# schematic.net
KiCad netlist of a schematic drawn in EAGLE
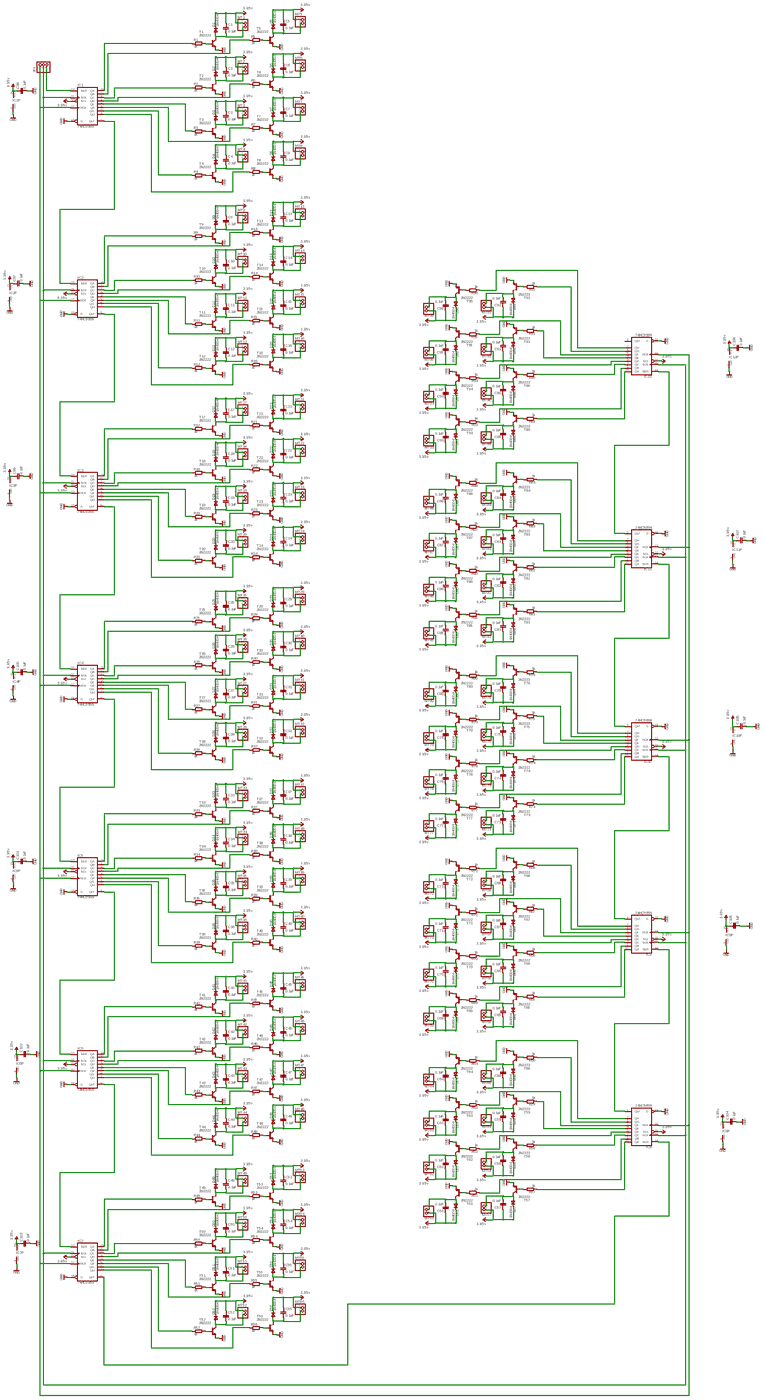
[diagram p0: schematic, sheet 1, overview]
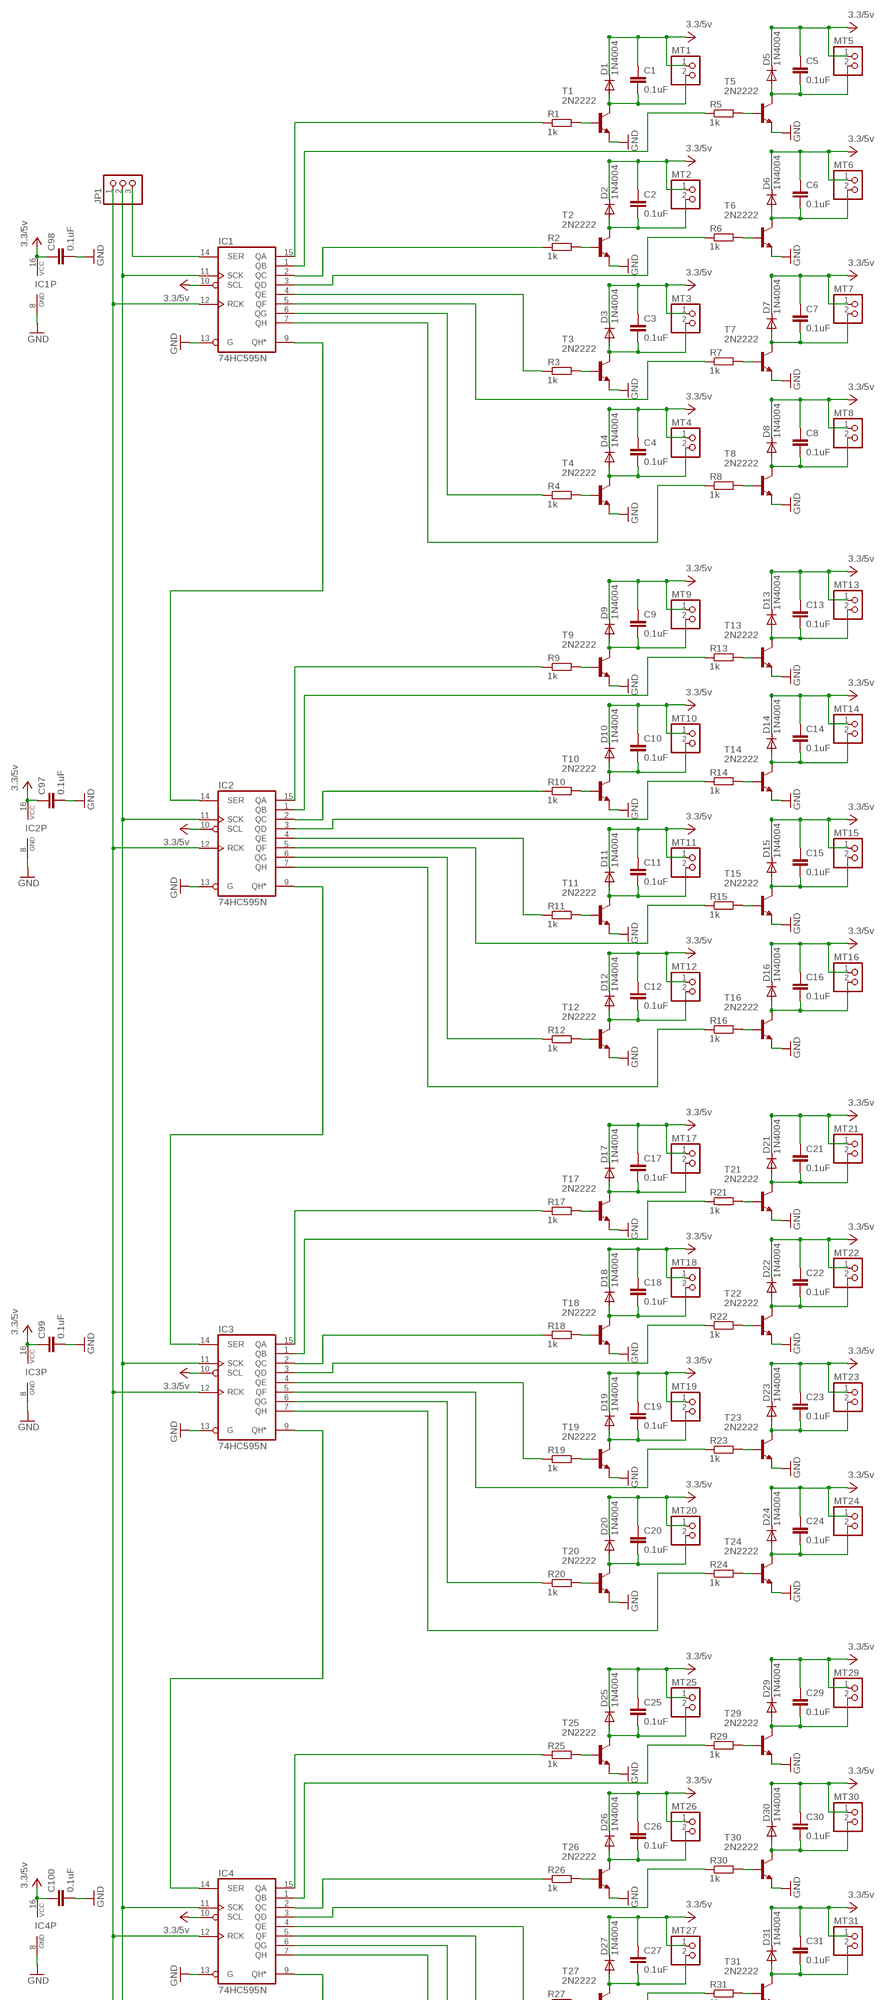
[diagram p1: schematic, sheet 1, part 1 of 4]
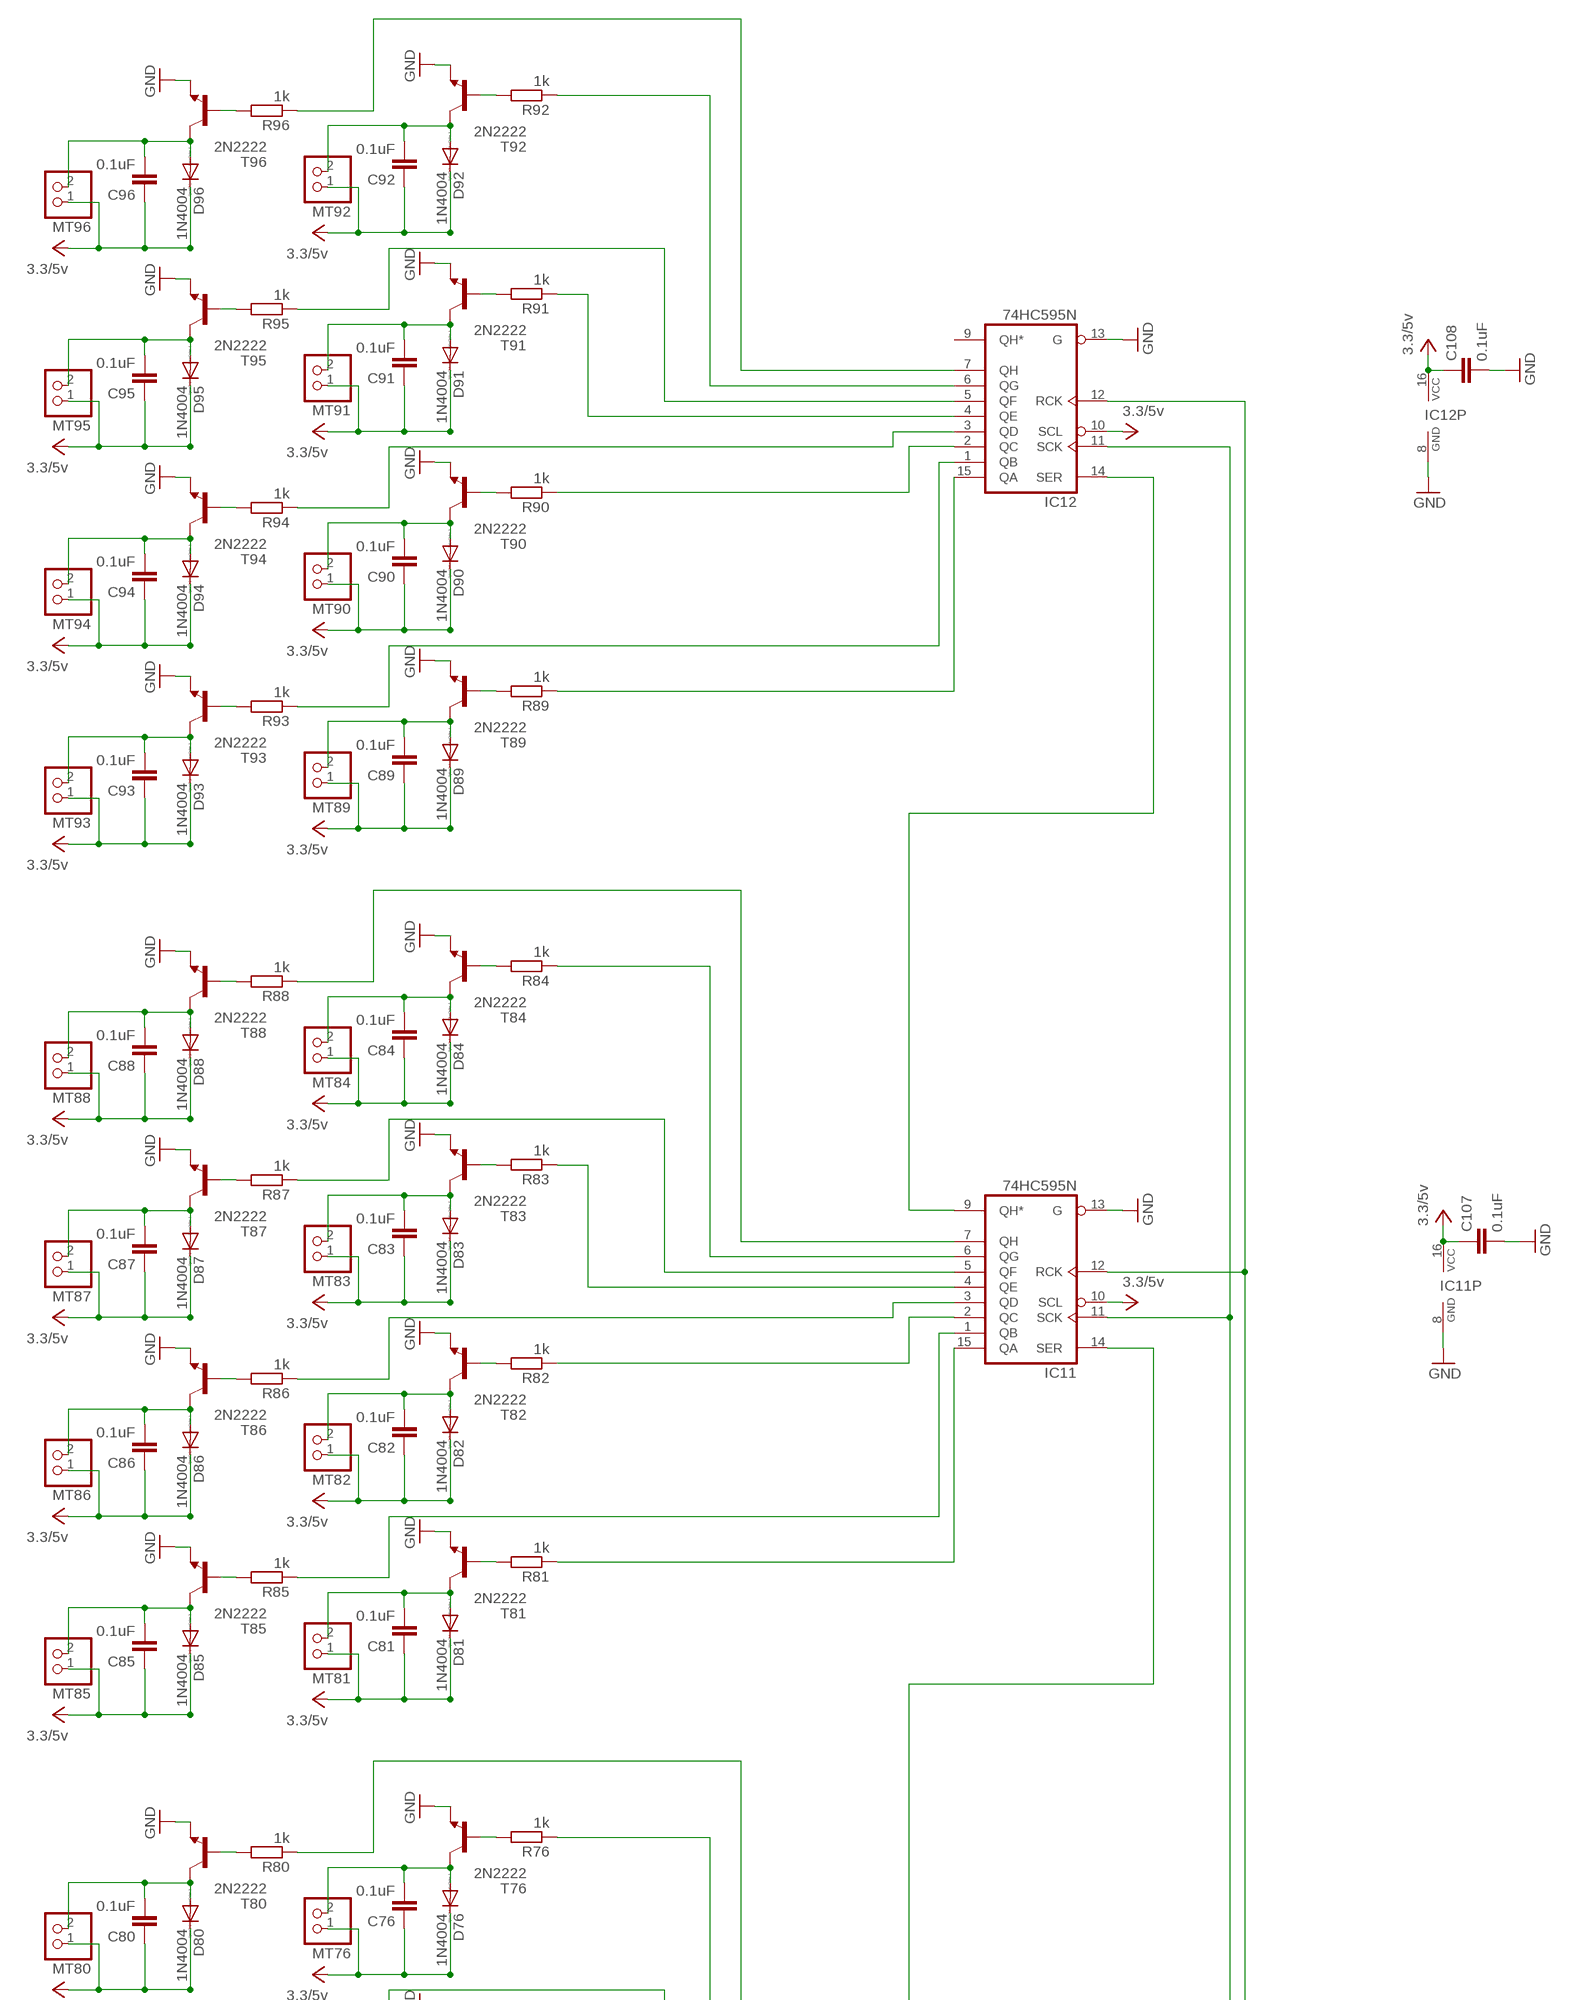
[diagram p2: schematic, sheet 1, part 2 of 4]
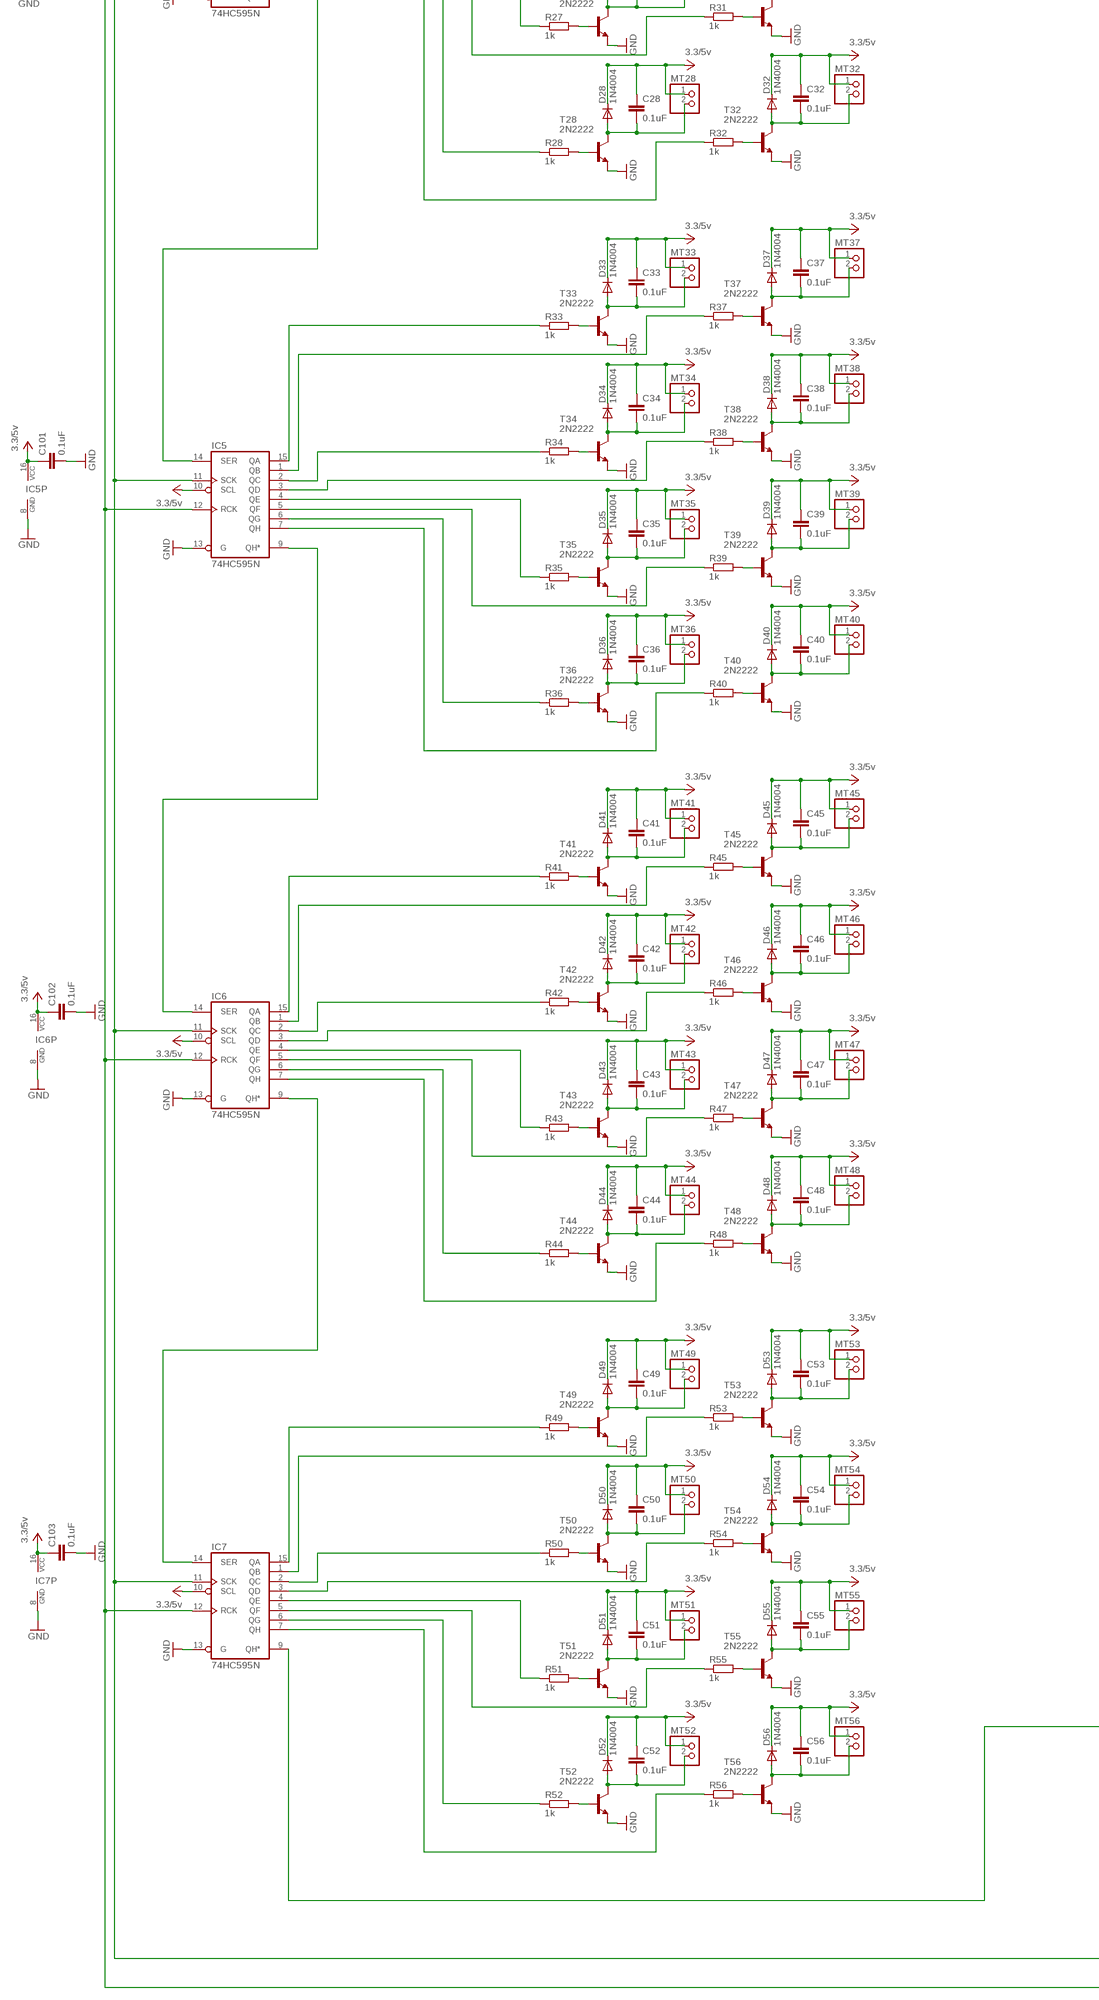
[diagram p3: schematic, sheet 1, part 3 of 4]
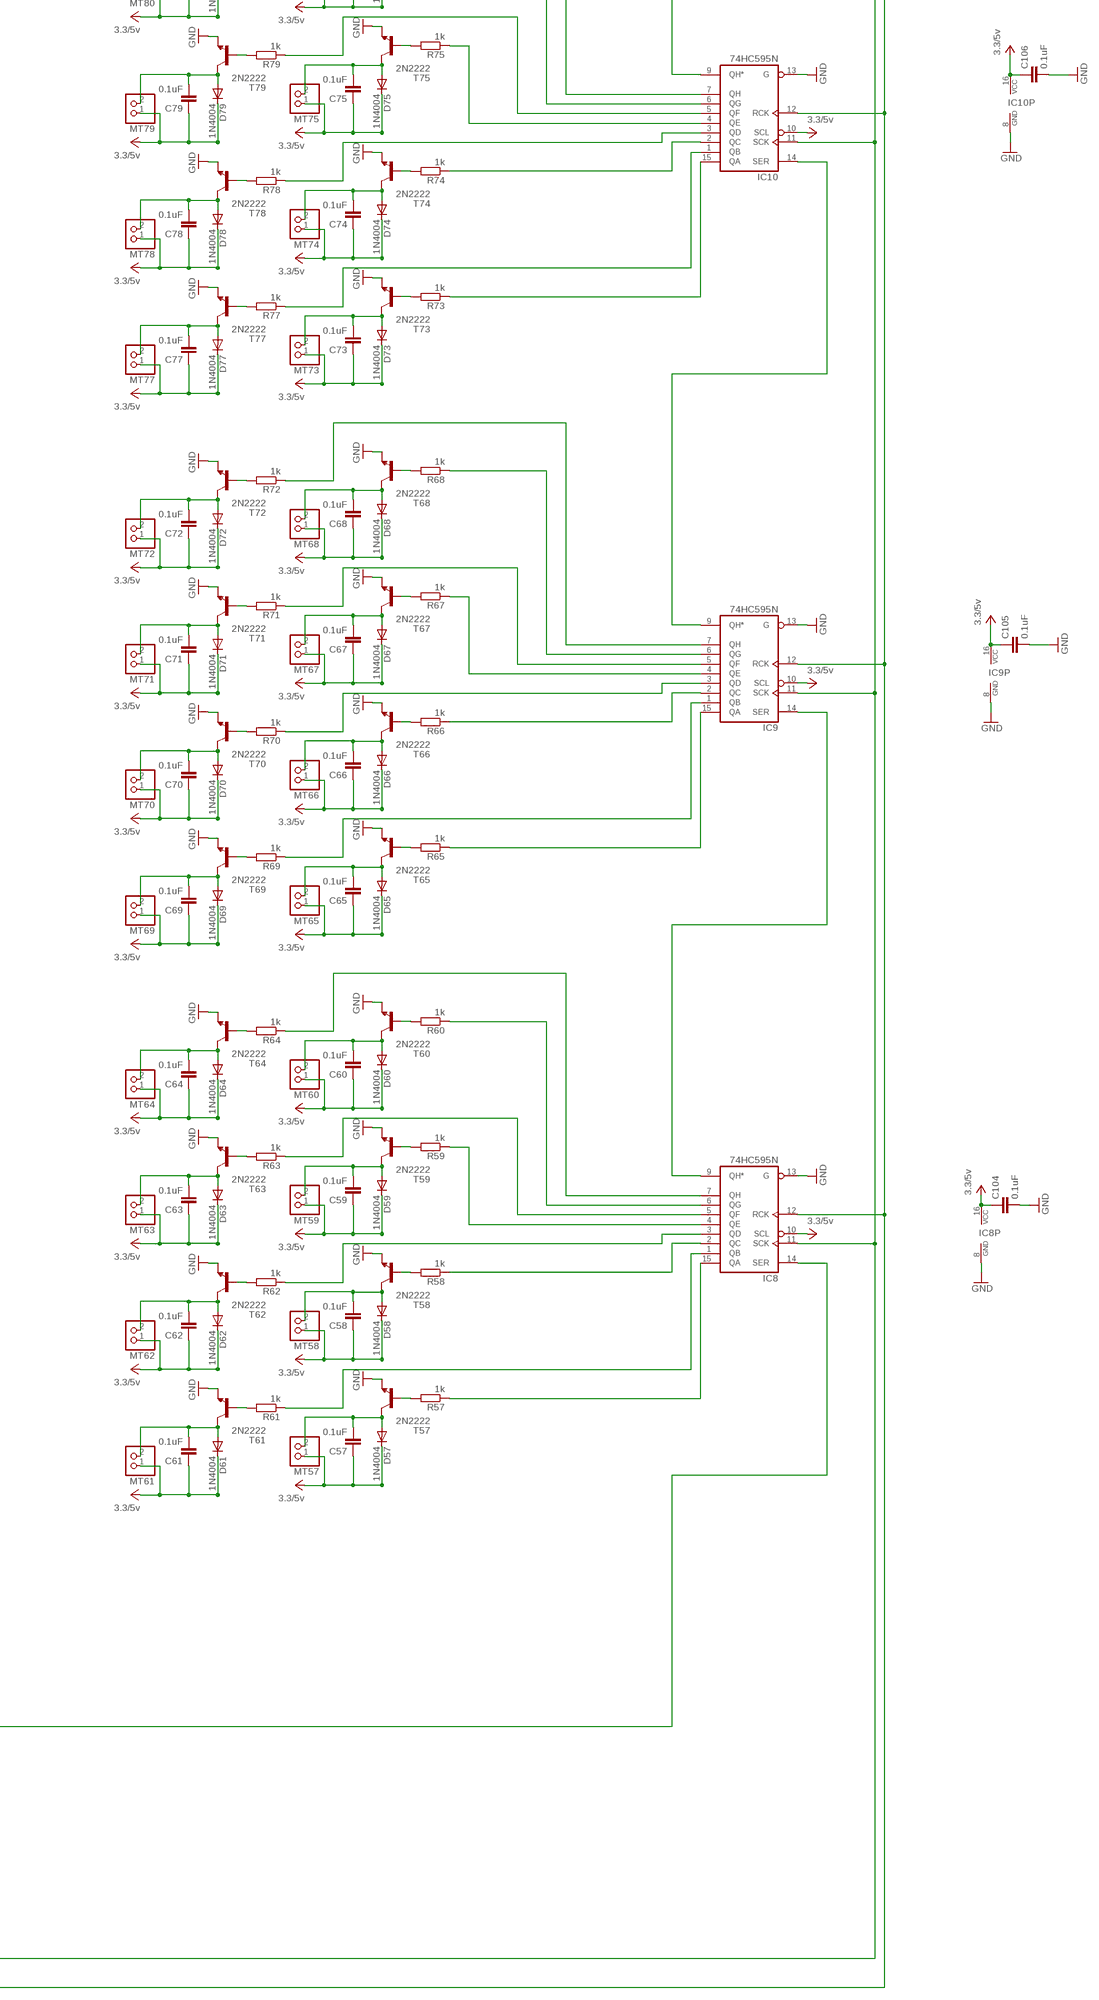
[diagram p4: schematic, sheet 1, part 4 of 4]

(export (version "E")
  (design (tool "Eeschema 10.0.6"))
  (components
    (comp (ref "C1")
      (value "0.1uF")
      (footprint "eagle-import:C025-024X044")
      (libsource (lib "eagle-import") (part "C-EU025-024X044"))
    )
    (comp (ref "C2")
      (value "0.1uF")
      (footprint "eagle-import:C025-024X044")
      (libsource (lib "eagle-import") (part "C-EU025-024X044"))
    )
    (comp (ref "C3")
      (value "0.1uF")
      (footprint "eagle-import:C025-024X044")
      (libsource (lib "eagle-import") (part "C-EU025-024X044"))
    )
    (comp (ref "C4")
      (value "0.1uF")
      (footprint "eagle-import:C025-024X044")
      (libsource (lib "eagle-import") (part "C-EU025-024X044"))
    )
    (comp (ref "C5")
      (value "0.1uF")
      (footprint "eagle-import:C025-024X044")
      (libsource (lib "eagle-import") (part "C-EU025-024X044"))
    )
    (comp (ref "C6")
      (value "0.1uF")
      (footprint "eagle-import:C025-024X044")
      (libsource (lib "eagle-import") (part "C-EU025-024X044"))
    )
    (comp (ref "C7")
      (value "0.1uF")
      (footprint "eagle-import:C025-024X044")
      (libsource (lib "eagle-import") (part "C-EU025-024X044"))
    )
    (comp (ref "C8")
      (value "0.1uF")
      (footprint "eagle-import:C025-024X044")
      (libsource (lib "eagle-import") (part "C-EU025-024X044"))
    )
    (comp (ref "C9")
      (value "0.1uF")
      (footprint "eagle-import:C025-024X044")
      (libsource (lib "eagle-import") (part "C-EU025-024X044"))
    )
    (comp (ref "C10")
      (value "0.1uF")
      (footprint "eagle-import:C025-024X044")
      (libsource (lib "eagle-import") (part "C-EU025-024X044"))
    )
    (comp (ref "C11")
      (value "0.1uF")
      (footprint "eagle-import:C025-024X044")
      (libsource (lib "eagle-import") (part "C-EU025-024X044"))
    )
    (comp (ref "C12")
      (value "0.1uF")
      (footprint "eagle-import:C025-024X044")
      (libsource (lib "eagle-import") (part "C-EU025-024X044"))
    )
    (comp (ref "C13")
      (value "0.1uF")
      (footprint "eagle-import:C025-024X044")
      (libsource (lib "eagle-import") (part "C-EU025-024X044"))
    )
    (comp (ref "C14")
      (value "0.1uF")
      (footprint "eagle-import:C025-024X044")
      (libsource (lib "eagle-import") (part "C-EU025-024X044"))
    )
    (comp (ref "C15")
      (value "0.1uF")
      (footprint "eagle-import:C025-024X044")
      (libsource (lib "eagle-import") (part "C-EU025-024X044"))
    )
    (comp (ref "C16")
      (value "0.1uF")
      (footprint "eagle-import:C025-024X044")
      (libsource (lib "eagle-import") (part "C-EU025-024X044"))
    )
    (comp (ref "C17")
      (value "0.1uF")
      (footprint "eagle-import:C025-024X044")
      (libsource (lib "eagle-import") (part "C-EU025-024X044"))
    )
    (comp (ref "C18")
      (value "0.1uF")
      (footprint "eagle-import:C025-024X044")
      (libsource (lib "eagle-import") (part "C-EU025-024X044"))
    )
    (comp (ref "C19")
      (value "0.1uF")
      (footprint "eagle-import:C025-024X044")
      (libsource (lib "eagle-import") (part "C-EU025-024X044"))
    )
    (comp (ref "C20")
      (value "0.1uF")
      (footprint "eagle-import:C025-024X044")
      (libsource (lib "eagle-import") (part "C-EU025-024X044"))
    )
    (comp (ref "C21")
      (value "0.1uF")
      (footprint "eagle-import:C025-024X044")
      (libsource (lib "eagle-import") (part "C-EU025-024X044"))
    )
    (comp (ref "C22")
      (value "0.1uF")
      (footprint "eagle-import:C025-024X044")
      (libsource (lib "eagle-import") (part "C-EU025-024X044"))
    )
    (comp (ref "C23")
      (value "0.1uF")
      (footprint "eagle-import:C025-024X044")
      (libsource (lib "eagle-import") (part "C-EU025-024X044"))
    )
    (comp (ref "C24")
      (value "0.1uF")
      (footprint "eagle-import:C025-024X044")
      (libsource (lib "eagle-import") (part "C-EU025-024X044"))
    )
    (comp (ref "C25")
      (value "0.1uF")
      (footprint "eagle-import:C025-024X044")
      (libsource (lib "eagle-import") (part "C-EU025-024X044"))
    )
    (comp (ref "C26")
      (value "0.1uF")
      (footprint "eagle-import:C025-024X044")
      (libsource (lib "eagle-import") (part "C-EU025-024X044"))
    )
    (comp (ref "C27")
      (value "0.1uF")
      (footprint "eagle-import:C025-024X044")
      (libsource (lib "eagle-import") (part "C-EU025-024X044"))
    )
    (comp (ref "C28")
      (value "0.1uF")
      (footprint "eagle-import:C025-024X044")
      (libsource (lib "eagle-import") (part "C-EU025-024X044"))
    )
    (comp (ref "C29")
      (value "0.1uF")
      (footprint "eagle-import:C025-024X044")
      (libsource (lib "eagle-import") (part "C-EU025-024X044"))
    )
    (comp (ref "C30")
      (value "0.1uF")
      (footprint "eagle-import:C025-024X044")
      (libsource (lib "eagle-import") (part "C-EU025-024X044"))
    )
    (comp (ref "C31")
      (value "0.1uF")
      (footprint "eagle-import:C025-024X044")
      (libsource (lib "eagle-import") (part "C-EU025-024X044"))
    )
    (comp (ref "C32")
      (value "0.1uF")
      (footprint "eagle-import:C025-024X044")
      (libsource (lib "eagle-import") (part "C-EU025-024X044"))
    )
    (comp (ref "C33")
      (value "0.1uF")
      (footprint "eagle-import:C025-024X044")
      (libsource (lib "eagle-import") (part "C-EU025-024X044"))
    )
    (comp (ref "C34")
      (value "0.1uF")
      (footprint "eagle-import:C025-024X044")
      (libsource (lib "eagle-import") (part "C-EU025-024X044"))
    )
    (comp (ref "C35")
      (value "0.1uF")
      (footprint "eagle-import:C025-024X044")
      (libsource (lib "eagle-import") (part "C-EU025-024X044"))
    )
    (comp (ref "C36")
      (value "0.1uF")
      (footprint "eagle-import:C025-024X044")
      (libsource (lib "eagle-import") (part "C-EU025-024X044"))
    )
    (comp (ref "C37")
      (value "0.1uF")
      (footprint "eagle-import:C025-024X044")
      (libsource (lib "eagle-import") (part "C-EU025-024X044"))
    )
    (comp (ref "C38")
      (value "0.1uF")
      (footprint "eagle-import:C025-024X044")
      (libsource (lib "eagle-import") (part "C-EU025-024X044"))
    )
    (comp (ref "C39")
      (value "0.1uF")
      (footprint "eagle-import:C025-024X044")
      (libsource (lib "eagle-import") (part "C-EU025-024X044"))
    )
    (comp (ref "C40")
      (value "0.1uF")
      (footprint "eagle-import:C025-024X044")
      (libsource (lib "eagle-import") (part "C-EU025-024X044"))
    )
    (comp (ref "C41")
      (value "0.1uF")
      (footprint "eagle-import:C025-024X044")
      (libsource (lib "eagle-import") (part "C-EU025-024X044"))
    )
    (comp (ref "C42")
      (value "0.1uF")
      (footprint "eagle-import:C025-024X044")
      (libsource (lib "eagle-import") (part "C-EU025-024X044"))
    )
    (comp (ref "C43")
      (value "0.1uF")
      (footprint "eagle-import:C025-024X044")
      (libsource (lib "eagle-import") (part "C-EU025-024X044"))
    )
    (comp (ref "C44")
      (value "0.1uF")
      (footprint "eagle-import:C025-024X044")
      (libsource (lib "eagle-import") (part "C-EU025-024X044"))
    )
    (comp (ref "C45")
      (value "0.1uF")
      (footprint "eagle-import:C025-024X044")
      (libsource (lib "eagle-import") (part "C-EU025-024X044"))
    )
    (comp (ref "C46")
      (value "0.1uF")
      (footprint "eagle-import:C025-024X044")
      (libsource (lib "eagle-import") (part "C-EU025-024X044"))
    )
    (comp (ref "C47")
      (value "0.1uF")
      (footprint "eagle-import:C025-024X044")
      (libsource (lib "eagle-import") (part "C-EU025-024X044"))
    )
    (comp (ref "C48")
      (value "0.1uF")
      (footprint "eagle-import:C025-024X044")
      (libsource (lib "eagle-import") (part "C-EU025-024X044"))
    )
    (comp (ref "C49")
      (value "0.1uF")
      (footprint "eagle-import:C025-024X044")
      (libsource (lib "eagle-import") (part "C-EU025-024X044"))
    )
    (comp (ref "C50")
      (value "0.1uF")
      (footprint "eagle-import:C025-024X044")
      (libsource (lib "eagle-import") (part "C-EU025-024X044"))
    )
    (comp (ref "C51")
      (value "0.1uF")
      (footprint "eagle-import:C025-024X044")
      (libsource (lib "eagle-import") (part "C-EU025-024X044"))
    )
    (comp (ref "C52")
      (value "0.1uF")
      (footprint "eagle-import:C025-024X044")
      (libsource (lib "eagle-import") (part "C-EU025-024X044"))
    )
    (comp (ref "C53")
      (value "0.1uF")
      (footprint "eagle-import:C025-024X044")
      (libsource (lib "eagle-import") (part "C-EU025-024X044"))
    )
    (comp (ref "C54")
      (value "0.1uF")
      (footprint "eagle-import:C025-024X044")
      (libsource (lib "eagle-import") (part "C-EU025-024X044"))
    )
    (comp (ref "C55")
      (value "0.1uF")
      (footprint "eagle-import:C025-024X044")
      (libsource (lib "eagle-import") (part "C-EU025-024X044"))
    )
    (comp (ref "C56")
      (value "0.1uF")
      (footprint "eagle-import:C025-024X044")
      (libsource (lib "eagle-import") (part "C-EU025-024X044"))
    )
    (comp (ref "C57")
      (value "0.1uF")
      (footprint "eagle-import:C025-024X044")
      (libsource (lib "eagle-import") (part "C-EU025-024X044"))
    )
    (comp (ref "C58")
      (value "0.1uF")
      (footprint "eagle-import:C025-024X044")
      (libsource (lib "eagle-import") (part "C-EU025-024X044"))
    )
    (comp (ref "C59")
      (value "0.1uF")
      (footprint "eagle-import:C025-024X044")
      (libsource (lib "eagle-import") (part "C-EU025-024X044"))
    )
    (comp (ref "C60")
      (value "0.1uF")
      (footprint "eagle-import:C025-024X044")
      (libsource (lib "eagle-import") (part "C-EU025-024X044"))
    )
    (comp (ref "C61")
      (value "0.1uF")
      (footprint "eagle-import:C025-024X044")
      (libsource (lib "eagle-import") (part "C-EU025-024X044"))
    )
    (comp (ref "C62")
      (value "0.1uF")
      (footprint "eagle-import:C025-024X044")
      (libsource (lib "eagle-import") (part "C-EU025-024X044"))
    )
    (comp (ref "C63")
      (value "0.1uF")
      (footprint "eagle-import:C025-024X044")
      (libsource (lib "eagle-import") (part "C-EU025-024X044"))
    )
    (comp (ref "C64")
      (value "0.1uF")
      (footprint "eagle-import:C025-024X044")
      (libsource (lib "eagle-import") (part "C-EU025-024X044"))
    )
    (comp (ref "C65")
      (value "0.1uF")
      (footprint "eagle-import:C025-024X044")
      (libsource (lib "eagle-import") (part "C-EU025-024X044"))
    )
    (comp (ref "C66")
      (value "0.1uF")
      (footprint "eagle-import:C025-024X044")
      (libsource (lib "eagle-import") (part "C-EU025-024X044"))
    )
    (comp (ref "C67")
      (value "0.1uF")
      (footprint "eagle-import:C025-024X044")
      (libsource (lib "eagle-import") (part "C-EU025-024X044"))
    )
    (comp (ref "C68")
      (value "0.1uF")
      (footprint "eagle-import:C025-024X044")
      (libsource (lib "eagle-import") (part "C-EU025-024X044"))
    )
    (comp (ref "C69")
      (value "0.1uF")
      (footprint "eagle-import:C025-024X044")
      (libsource (lib "eagle-import") (part "C-EU025-024X044"))
    )
    (comp (ref "C70")
      (value "0.1uF")
      (footprint "eagle-import:C025-024X044")
      (libsource (lib "eagle-import") (part "C-EU025-024X044"))
    )
    (comp (ref "C71")
      (value "0.1uF")
      (footprint "eagle-import:C025-024X044")
      (libsource (lib "eagle-import") (part "C-EU025-024X044"))
    )
    (comp (ref "C72")
      (value "0.1uF")
      (footprint "eagle-import:C025-024X044")
      (libsource (lib "eagle-import") (part "C-EU025-024X044"))
    )
    (comp (ref "C73")
      (value "0.1uF")
      (footprint "eagle-import:C025-024X044")
      (libsource (lib "eagle-import") (part "C-EU025-024X044"))
    )
    (comp (ref "C74")
      (value "0.1uF")
      (footprint "eagle-import:C025-024X044")
      (libsource (lib "eagle-import") (part "C-EU025-024X044"))
    )
    (comp (ref "C75")
      (value "0.1uF")
      (footprint "eagle-import:C025-024X044")
      (libsource (lib "eagle-import") (part "C-EU025-024X044"))
    )
    (comp (ref "C76")
      (value "0.1uF")
      (footprint "eagle-import:C025-024X044")
      (libsource (lib "eagle-import") (part "C-EU025-024X044"))
    )
    (comp (ref "C77")
      (value "0.1uF")
      (footprint "eagle-import:C025-024X044")
      (libsource (lib "eagle-import") (part "C-EU025-024X044"))
    )
    (comp (ref "C78")
      (value "0.1uF")
      (footprint "eagle-import:C025-024X044")
      (libsource (lib "eagle-import") (part "C-EU025-024X044"))
    )
    (comp (ref "C79")
      (value "0.1uF")
      (footprint "eagle-import:C025-024X044")
      (libsource (lib "eagle-import") (part "C-EU025-024X044"))
    )
    (comp (ref "C80")
      (value "0.1uF")
      (footprint "eagle-import:C025-024X044")
      (libsource (lib "eagle-import") (part "C-EU025-024X044"))
    )
    (comp (ref "C81")
      (value "0.1uF")
      (footprint "eagle-import:C025-024X044")
      (libsource (lib "eagle-import") (part "C-EU025-024X044"))
    )
    (comp (ref "C82")
      (value "0.1uF")
      (footprint "eagle-import:C025-024X044")
      (libsource (lib "eagle-import") (part "C-EU025-024X044"))
    )
    (comp (ref "C83")
      (value "0.1uF")
      (footprint "eagle-import:C025-024X044")
      (libsource (lib "eagle-import") (part "C-EU025-024X044"))
    )
    (comp (ref "C84")
      (value "0.1uF")
      (footprint "eagle-import:C025-024X044")
      (libsource (lib "eagle-import") (part "C-EU025-024X044"))
    )
    (comp (ref "C85")
      (value "0.1uF")
      (footprint "eagle-import:C025-024X044")
      (libsource (lib "eagle-import") (part "C-EU025-024X044"))
    )
    (comp (ref "C86")
      (value "0.1uF")
      (footprint "eagle-import:C025-024X044")
      (libsource (lib "eagle-import") (part "C-EU025-024X044"))
    )
    (comp (ref "C87")
      (value "0.1uF")
      (footprint "eagle-import:C025-024X044")
      (libsource (lib "eagle-import") (part "C-EU025-024X044"))
    )
    (comp (ref "C88")
      (value "0.1uF")
      (footprint "eagle-import:C025-024X044")
      (libsource (lib "eagle-import") (part "C-EU025-024X044"))
    )
    (comp (ref "C89")
      (value "0.1uF")
      (footprint "eagle-import:C025-024X044")
      (libsource (lib "eagle-import") (part "C-EU025-024X044"))
    )
    (comp (ref "C90")
      (value "0.1uF")
      (footprint "eagle-import:C025-024X044")
      (libsource (lib "eagle-import") (part "C-EU025-024X044"))
    )
    (comp (ref "C91")
      (value "0.1uF")
      (footprint "eagle-import:C025-024X044")
      (libsource (lib "eagle-import") (part "C-EU025-024X044"))
    )
    (comp (ref "C92")
      (value "0.1uF")
      (footprint "eagle-import:C025-024X044")
      (libsource (lib "eagle-import") (part "C-EU025-024X044"))
    )
    (comp (ref "C93")
      (value "0.1uF")
      (footprint "eagle-import:C025-024X044")
      (libsource (lib "eagle-import") (part "C-EU025-024X044"))
    )
    (comp (ref "C94")
      (value "0.1uF")
      (footprint "eagle-import:C025-024X044")
      (libsource (lib "eagle-import") (part "C-EU025-024X044"))
    )
    (comp (ref "C95")
      (value "0.1uF")
      (footprint "eagle-import:C025-024X044")
      (libsource (lib "eagle-import") (part "C-EU025-024X044"))
    )
    (comp (ref "C96")
      (value "0.1uF")
      (footprint "eagle-import:C025-024X044")
      (libsource (lib "eagle-import") (part "C-EU025-024X044"))
    )
    (comp (ref "C97")
      (value "0.1uF")
      (footprint "eagle-import:C025-024X044")
      (libsource (lib "eagle-import") (part "C-EU025-024X044"))
    )
    (comp (ref "C98")
      (value "0.1uF")
      (footprint "eagle-import:C025-024X044")
      (libsource (lib "eagle-import") (part "C-EU025-024X044"))
    )
    (comp (ref "C99")
      (value "0.1uF")
      (footprint "eagle-import:C025-024X044")
      (libsource (lib "eagle-import") (part "C-EU025-024X044"))
    )
    (comp (ref "C100")
      (value "0.1uF")
      (footprint "eagle-import:C025-024X044")
      (libsource (lib "eagle-import") (part "C-EU025-024X044"))
    )
    (comp (ref "C101")
      (value "0.1uF")
      (footprint "eagle-import:C025-024X044")
      (libsource (lib "eagle-import") (part "C-EU025-024X044"))
    )
    (comp (ref "C102")
      (value "0.1uF")
      (footprint "eagle-import:C025-024X044")
      (libsource (lib "eagle-import") (part "C-EU025-024X044"))
    )
    (comp (ref "C103")
      (value "0.1uF")
      (footprint "eagle-import:C025-024X044")
      (libsource (lib "eagle-import") (part "C-EU025-024X044"))
    )
    (comp (ref "C104")
      (value "0.1uF")
      (footprint "eagle-import:C025-024X044")
      (libsource (lib "eagle-import") (part "C-EU025-024X044"))
    )
    (comp (ref "C105")
      (value "0.1uF")
      (footprint "eagle-import:C025-024X044")
      (libsource (lib "eagle-import") (part "C-EU025-024X044"))
    )
    (comp (ref "C106")
      (value "0.1uF")
      (footprint "eagle-import:C025-024X044")
      (libsource (lib "eagle-import") (part "C-EU025-024X044"))
    )
    (comp (ref "C107")
      (value "0.1uF")
      (footprint "eagle-import:C025-024X044")
      (libsource (lib "eagle-import") (part "C-EU025-024X044"))
    )
    (comp (ref "C108")
      (value "0.1uF")
      (footprint "eagle-import:C025-024X044")
      (libsource (lib "eagle-import") (part "C-EU025-024X044"))
    )
    (comp (ref "D1")
      (value "1N4004")
      (footprint "eagle-import:DO41-10")
      (libsource (lib "eagle-import") (part "1N4004"))
    )
    (comp (ref "D2")
      (value "1N4004")
      (footprint "eagle-import:DO41-10")
      (libsource (lib "eagle-import") (part "1N4004"))
    )
    (comp (ref "D3")
      (value "1N4004")
      (footprint "eagle-import:DO41-10")
      (libsource (lib "eagle-import") (part "1N4004"))
    )
    (comp (ref "D4")
      (value "1N4004")
      (footprint "eagle-import:DO41-10")
      (libsource (lib "eagle-import") (part "1N4004"))
    )
    (comp (ref "D5")
      (value "1N4004")
      (footprint "eagle-import:DO41-10")
      (libsource (lib "eagle-import") (part "1N4004"))
    )
    (comp (ref "D6")
      (value "1N4004")
      (footprint "eagle-import:DO41-10")
      (libsource (lib "eagle-import") (part "1N4004"))
    )
    (comp (ref "D7")
      (value "1N4004")
      (footprint "eagle-import:DO41-10")
      (libsource (lib "eagle-import") (part "1N4004"))
    )
    (comp (ref "D8")
      (value "1N4004")
      (footprint "eagle-import:DO41-10")
      (libsource (lib "eagle-import") (part "1N4004"))
    )
    (comp (ref "D9")
      (value "1N4004")
      (footprint "eagle-import:DO41-10")
      (libsource (lib "eagle-import") (part "1N4004"))
    )
    (comp (ref "D10")
      (value "1N4004")
      (footprint "eagle-import:DO41-10")
      (libsource (lib "eagle-import") (part "1N4004"))
    )
    (comp (ref "D11")
      (value "1N4004")
      (footprint "eagle-import:DO41-10")
      (libsource (lib "eagle-import") (part "1N4004"))
    )
    (comp (ref "D12")
      (value "1N4004")
      (footprint "eagle-import:DO41-10")
      (libsource (lib "eagle-import") (part "1N4004"))
    )
    (comp (ref "D13")
      (value "1N4004")
      (footprint "eagle-import:DO41-10")
      (libsource (lib "eagle-import") (part "1N4004"))
    )
    (comp (ref "D14")
      (value "1N4004")
      (footprint "eagle-import:DO41-10")
      (libsource (lib "eagle-import") (part "1N4004"))
    )
    (comp (ref "D15")
      (value "1N4004")
      (footprint "eagle-import:DO41-10")
      (libsource (lib "eagle-import") (part "1N4004"))
    )
    (comp (ref "D16")
      (value "1N4004")
      (footprint "eagle-import:DO41-10")
      (libsource (lib "eagle-import") (part "1N4004"))
    )
    (comp (ref "D17")
      (value "1N4004")
      (footprint "eagle-import:DO41-10")
      (libsource (lib "eagle-import") (part "1N4004"))
    )
    (comp (ref "D18")
      (value "1N4004")
      (footprint "eagle-import:DO41-10")
      (libsource (lib "eagle-import") (part "1N4004"))
    )
    (comp (ref "D19")
      (value "1N4004")
      (footprint "eagle-import:DO41-10")
      (libsource (lib "eagle-import") (part "1N4004"))
    )
    (comp (ref "D20")
      (value "1N4004")
      (footprint "eagle-import:DO41-10")
      (libsource (lib "eagle-import") (part "1N4004"))
    )
    (comp (ref "D21")
      (value "1N4004")
      (footprint "eagle-import:DO41-10")
      (libsource (lib "eagle-import") (part "1N4004"))
    )
    (comp (ref "D22")
      (value "1N4004")
      (footprint "eagle-import:DO41-10")
      (libsource (lib "eagle-import") (part "1N4004"))
    )
    (comp (ref "D23")
      (value "1N4004")
      (footprint "eagle-import:DO41-10")
      (libsource (lib "eagle-import") (part "1N4004"))
    )
    (comp (ref "D24")
      (value "1N4004")
      (footprint "eagle-import:DO41-10")
      (libsource (lib "eagle-import") (part "1N4004"))
    )
    (comp (ref "D25")
      (value "1N4004")
      (footprint "eagle-import:DO41-10")
      (libsource (lib "eagle-import") (part "1N4004"))
    )
    (comp (ref "D26")
      (value "1N4004")
      (footprint "eagle-import:DO41-10")
      (libsource (lib "eagle-import") (part "1N4004"))
    )
    (comp (ref "D27")
      (value "1N4004")
      (footprint "eagle-import:DO41-10")
      (libsource (lib "eagle-import") (part "1N4004"))
    )
    (comp (ref "D28")
      (value "1N4004")
      (footprint "eagle-import:DO41-10")
      (libsource (lib "eagle-import") (part "1N4004"))
    )
    (comp (ref "D29")
      (value "1N4004")
      (footprint "eagle-import:DO41-10")
      (libsource (lib "eagle-import") (part "1N4004"))
    )
    (comp (ref "D30")
      (value "1N4004")
      (footprint "eagle-import:DO41-10")
      (libsource (lib "eagle-import") (part "1N4004"))
    )
    (comp (ref "D31")
      (value "1N4004")
      (footprint "eagle-import:DO41-10")
      (libsource (lib "eagle-import") (part "1N4004"))
    )
    (comp (ref "D32")
      (value "1N4004")
      (footprint "eagle-import:DO41-10")
      (libsource (lib "eagle-import") (part "1N4004"))
    )
    (comp (ref "D33")
      (value "1N4004")
      (footprint "eagle-import:DO41-10")
      (libsource (lib "eagle-import") (part "1N4004"))
    )
    (comp (ref "D34")
      (value "1N4004")
      (footprint "eagle-import:DO41-10")
      (libsource (lib "eagle-import") (part "1N4004"))
    )
    (comp (ref "D35")
      (value "1N4004")
      (footprint "eagle-import:DO41-10")
      (libsource (lib "eagle-import") (part "1N4004"))
    )
    (comp (ref "D36")
      (value "1N4004")
      (footprint "eagle-import:DO41-10")
      (libsource (lib "eagle-import") (part "1N4004"))
    )
    (comp (ref "D37")
      (value "1N4004")
      (footprint "eagle-import:DO41-10")
      (libsource (lib "eagle-import") (part "1N4004"))
    )
    (comp (ref "D38")
      (value "1N4004")
      (footprint "eagle-import:DO41-10")
      (libsource (lib "eagle-import") (part "1N4004"))
    )
    (comp (ref "D39")
      (value "1N4004")
      (footprint "eagle-import:DO41-10")
      (libsource (lib "eagle-import") (part "1N4004"))
    )
    (comp (ref "D40")
      (value "1N4004")
      (footprint "eagle-import:DO41-10")
      (libsource (lib "eagle-import") (part "1N4004"))
    )
    (comp (ref "D41")
      (value "1N4004")
      (footprint "eagle-import:DO41-10")
      (libsource (lib "eagle-import") (part "1N4004"))
    )
    (comp (ref "D42")
      (value "1N4004")
      (footprint "eagle-import:DO41-10")
      (libsource (lib "eagle-import") (part "1N4004"))
    )
    (comp (ref "D43")
      (value "1N4004")
      (footprint "eagle-import:DO41-10")
      (libsource (lib "eagle-import") (part "1N4004"))
    )
    (comp (ref "D44")
      (value "1N4004")
      (footprint "eagle-import:DO41-10")
      (libsource (lib "eagle-import") (part "1N4004"))
    )
    (comp (ref "D45")
      (value "1N4004")
      (footprint "eagle-import:DO41-10")
      (libsource (lib "eagle-import") (part "1N4004"))
    )
    (comp (ref "D46")
      (value "1N4004")
      (footprint "eagle-import:DO41-10")
      (libsource (lib "eagle-import") (part "1N4004"))
    )
    (comp (ref "D47")
      (value "1N4004")
      (footprint "eagle-import:DO41-10")
      (libsource (lib "eagle-import") (part "1N4004"))
    )
    (comp (ref "D48")
      (value "1N4004")
      (footprint "eagle-import:DO41-10")
      (libsource (lib "eagle-import") (part "1N4004"))
    )
    (comp (ref "D49")
      (value "1N4004")
      (footprint "eagle-import:DO41-10")
      (libsource (lib "eagle-import") (part "1N4004"))
    )
    (comp (ref "D50")
      (value "1N4004")
      (footprint "eagle-import:DO41-10")
      (libsource (lib "eagle-import") (part "1N4004"))
    )
    (comp (ref "D51")
      (value "1N4004")
      (footprint "eagle-import:DO41-10")
      (libsource (lib "eagle-import") (part "1N4004"))
    )
    (comp (ref "D52")
      (value "1N4004")
      (footprint "eagle-import:DO41-10")
      (libsource (lib "eagle-import") (part "1N4004"))
    )
    (comp (ref "D53")
      (value "1N4004")
      (footprint "eagle-import:DO41-10")
      (libsource (lib "eagle-import") (part "1N4004"))
    )
    (comp (ref "D54")
      (value "1N4004")
      (footprint "eagle-import:DO41-10")
      (libsource (lib "eagle-import") (part "1N4004"))
    )
    (comp (ref "D55")
      (value "1N4004")
      (footprint "eagle-import:DO41-10")
      (libsource (lib "eagle-import") (part "1N4004"))
    )
    (comp (ref "D56")
      (value "1N4004")
      (footprint "eagle-import:DO41-10")
      (libsource (lib "eagle-import") (part "1N4004"))
    )
    (comp (ref "D57")
      (value "1N4004")
      (footprint "eagle-import:DO41-10")
      (libsource (lib "eagle-import") (part "1N4004"))
    )
    (comp (ref "D58")
      (value "1N4004")
      (footprint "eagle-import:DO41-10")
      (libsource (lib "eagle-import") (part "1N4004"))
    )
    (comp (ref "D59")
      (value "1N4004")
      (footprint "eagle-import:DO41-10")
      (libsource (lib "eagle-import") (part "1N4004"))
    )
    (comp (ref "D60")
      (value "1N4004")
      (footprint "eagle-import:DO41-10")
      (libsource (lib "eagle-import") (part "1N4004"))
    )
    (comp (ref "D61")
      (value "1N4004")
      (footprint "eagle-import:DO41-10")
      (libsource (lib "eagle-import") (part "1N4004"))
    )
    (comp (ref "D62")
      (value "1N4004")
      (footprint "eagle-import:DO41-10")
      (libsource (lib "eagle-import") (part "1N4004"))
    )
    (comp (ref "D63")
      (value "1N4004")
      (footprint "eagle-import:DO41-10")
      (libsource (lib "eagle-import") (part "1N4004"))
    )
    (comp (ref "D64")
      (value "1N4004")
      (footprint "eagle-import:DO41-10")
      (libsource (lib "eagle-import") (part "1N4004"))
    )
    (comp (ref "D65")
      (value "1N4004")
      (footprint "eagle-import:DO41-10")
      (libsource (lib "eagle-import") (part "1N4004"))
    )
    (comp (ref "D66")
      (value "1N4004")
      (footprint "eagle-import:DO41-10")
      (libsource (lib "eagle-import") (part "1N4004"))
    )
    (comp (ref "D67")
      (value "1N4004")
      (footprint "eagle-import:DO41-10")
      (libsource (lib "eagle-import") (part "1N4004"))
    )
    (comp (ref "D68")
      (value "1N4004")
      (footprint "eagle-import:DO41-10")
      (libsource (lib "eagle-import") (part "1N4004"))
    )
    (comp (ref "D69")
      (value "1N4004")
      (footprint "eagle-import:DO41-10")
      (libsource (lib "eagle-import") (part "1N4004"))
    )
    (comp (ref "D70")
      (value "1N4004")
      (footprint "eagle-import:DO41-10")
      (libsource (lib "eagle-import") (part "1N4004"))
    )
    (comp (ref "D71")
      (value "1N4004")
      (footprint "eagle-import:DO41-10")
      (libsource (lib "eagle-import") (part "1N4004"))
    )
    (comp (ref "D72")
      (value "1N4004")
      (footprint "eagle-import:DO41-10")
      (libsource (lib "eagle-import") (part "1N4004"))
    )
    (comp (ref "D73")
      (value "1N4004")
      (footprint "eagle-import:DO41-10")
      (libsource (lib "eagle-import") (part "1N4004"))
    )
    (comp (ref "D74")
      (value "1N4004")
      (footprint "eagle-import:DO41-10")
      (libsource (lib "eagle-import") (part "1N4004"))
    )
    (comp (ref "D75")
      (value "1N4004")
      (footprint "eagle-import:DO41-10")
      (libsource (lib "eagle-import") (part "1N4004"))
    )
    (comp (ref "D76")
      (value "1N4004")
      (footprint "eagle-import:DO41-10")
      (libsource (lib "eagle-import") (part "1N4004"))
    )
    (comp (ref "D77")
      (value "1N4004")
      (footprint "eagle-import:DO41-10")
      (libsource (lib "eagle-import") (part "1N4004"))
    )
    (comp (ref "D78")
      (value "1N4004")
      (footprint "eagle-import:DO41-10")
      (libsource (lib "eagle-import") (part "1N4004"))
    )
    (comp (ref "D79")
      (value "1N4004")
      (footprint "eagle-import:DO41-10")
      (libsource (lib "eagle-import") (part "1N4004"))
    )
    (comp (ref "D80")
      (value "1N4004")
      (footprint "eagle-import:DO41-10")
      (libsource (lib "eagle-import") (part "1N4004"))
    )
    (comp (ref "D81")
      (value "1N4004")
      (footprint "eagle-import:DO41-10")
      (libsource (lib "eagle-import") (part "1N4004"))
    )
    (comp (ref "D82")
      (value "1N4004")
      (footprint "eagle-import:DO41-10")
      (libsource (lib "eagle-import") (part "1N4004"))
    )
    (comp (ref "D83")
      (value "1N4004")
      (footprint "eagle-import:DO41-10")
      (libsource (lib "eagle-import") (part "1N4004"))
    )
    (comp (ref "D84")
      (value "1N4004")
      (footprint "eagle-import:DO41-10")
      (libsource (lib "eagle-import") (part "1N4004"))
    )
    (comp (ref "D85")
      (value "1N4004")
      (footprint "eagle-import:DO41-10")
      (libsource (lib "eagle-import") (part "1N4004"))
    )
    (comp (ref "D86")
      (value "1N4004")
      (footprint "eagle-import:DO41-10")
      (libsource (lib "eagle-import") (part "1N4004"))
    )
    (comp (ref "D87")
      (value "1N4004")
      (footprint "eagle-import:DO41-10")
      (libsource (lib "eagle-import") (part "1N4004"))
    )
    (comp (ref "D88")
      (value "1N4004")
      (footprint "eagle-import:DO41-10")
      (libsource (lib "eagle-import") (part "1N4004"))
    )
    (comp (ref "D89")
      (value "1N4004")
      (footprint "eagle-import:DO41-10")
      (libsource (lib "eagle-import") (part "1N4004"))
    )
    (comp (ref "D90")
      (value "1N4004")
      (footprint "eagle-import:DO41-10")
      (libsource (lib "eagle-import") (part "1N4004"))
    )
    (comp (ref "D91")
      (value "1N4004")
      (footprint "eagle-import:DO41-10")
      (libsource (lib "eagle-import") (part "1N4004"))
    )
    (comp (ref "D92")
      (value "1N4004")
      (footprint "eagle-import:DO41-10")
      (libsource (lib "eagle-import") (part "1N4004"))
    )
    (comp (ref "D93")
      (value "1N4004")
      (footprint "eagle-import:DO41-10")
      (libsource (lib "eagle-import") (part "1N4004"))
    )
    (comp (ref "D94")
      (value "1N4004")
      (footprint "eagle-import:DO41-10")
      (libsource (lib "eagle-import") (part "1N4004"))
    )
    (comp (ref "D95")
      (value "1N4004")
      (footprint "eagle-import:DO41-10")
      (libsource (lib "eagle-import") (part "1N4004"))
    )
    (comp (ref "D96")
      (value "1N4004")
      (footprint "eagle-import:DO41-10")
      (libsource (lib "eagle-import") (part "1N4004"))
    )
    (comp (ref "IC1")
      (value "74HC595N")
      (footprint "eagle-import:DIL16")
      (libsource (lib "eagle-import") (part "74595NHC"))
    )
    (comp (ref "IC2")
      (value "74HC595N")
      (footprint "eagle-import:DIL16")
      (libsource (lib "eagle-import") (part "74595NHC"))
    )
    (comp (ref "IC3")
      (value "74HC595N")
      (footprint "eagle-import:DIL16")
      (libsource (lib "eagle-import") (part "74595NHC"))
    )
    (comp (ref "IC4")
      (value "74HC595N")
      (footprint "eagle-import:DIL16")
      (libsource (lib "eagle-import") (part "74595NHC"))
    )
    (comp (ref "IC5")
      (value "74HC595N")
      (footprint "eagle-import:DIL16")
      (libsource (lib "eagle-import") (part "74595NHC"))
    )
    (comp (ref "IC6")
      (value "74HC595N")
      (footprint "eagle-import:DIL16")
      (libsource (lib "eagle-import") (part "74595NHC"))
    )
    (comp (ref "IC7")
      (value "74HC595N")
      (footprint "eagle-import:DIL16")
      (libsource (lib "eagle-import") (part "74595NHC"))
    )
    (comp (ref "IC8")
      (value "74HC595N")
      (footprint "eagle-import:DIL16")
      (libsource (lib "eagle-import") (part "74595NHC"))
    )
    (comp (ref "IC9")
      (value "74HC595N")
      (footprint "eagle-import:DIL16")
      (libsource (lib "eagle-import") (part "74595NHC"))
    )
    (comp (ref "IC10")
      (value "74HC595N")
      (footprint "eagle-import:DIL16")
      (libsource (lib "eagle-import") (part "74595NHC"))
    )
    (comp (ref "IC11")
      (value "74HC595N")
      (footprint "eagle-import:DIL16")
      (libsource (lib "eagle-import") (part "74595NHC"))
    )
    (comp (ref "IC12")
      (value "74HC595N")
      (footprint "eagle-import:DIL16")
      (libsource (lib "eagle-import") (part "74595NHC"))
    )
    (comp (ref "JP1")
      (value "PINHD-1X3")
      (footprint "eagle-import:1X03")
      (libsource (lib "eagle-import") (part "PINHD-1X3"))
    )
    (comp (ref "MT1")
      (value "PINHD-1X2")
      (footprint "eagle-import:1X02")
      (libsource (lib "eagle-import") (part "PINHD-1X2"))
    )
    (comp (ref "MT2")
      (value "PINHD-1X2")
      (footprint "eagle-import:1X02")
      (libsource (lib "eagle-import") (part "PINHD-1X2"))
    )
    (comp (ref "MT3")
      (value "PINHD-1X2")
      (footprint "eagle-import:1X02")
      (libsource (lib "eagle-import") (part "PINHD-1X2"))
    )
    (comp (ref "MT4")
      (value "PINHD-1X2")
      (footprint "eagle-import:1X02")
      (libsource (lib "eagle-import") (part "PINHD-1X2"))
    )
    (comp (ref "MT5")
      (value "PINHD-1X2")
      (footprint "eagle-import:1X02")
      (libsource (lib "eagle-import") (part "PINHD-1X2"))
    )
    (comp (ref "MT6")
      (value "PINHD-1X2")
      (footprint "eagle-import:1X02")
      (libsource (lib "eagle-import") (part "PINHD-1X2"))
    )
    (comp (ref "MT7")
      (value "PINHD-1X2")
      (footprint "eagle-import:1X02")
      (libsource (lib "eagle-import") (part "PINHD-1X2"))
    )
    (comp (ref "MT8")
      (value "PINHD-1X2")
      (footprint "eagle-import:1X02")
      (libsource (lib "eagle-import") (part "PINHD-1X2"))
    )
    (comp (ref "MT9")
      (value "PINHD-1X2")
      (footprint "eagle-import:1X02")
      (libsource (lib "eagle-import") (part "PINHD-1X2"))
    )
    (comp (ref "MT10")
      (value "PINHD-1X2")
      (footprint "eagle-import:1X02")
      (libsource (lib "eagle-import") (part "PINHD-1X2"))
    )
    (comp (ref "MT11")
      (value "PINHD-1X2")
      (footprint "eagle-import:1X02")
      (libsource (lib "eagle-import") (part "PINHD-1X2"))
    )
    (comp (ref "MT12")
      (value "PINHD-1X2")
      (footprint "eagle-import:1X02")
      (libsource (lib "eagle-import") (part "PINHD-1X2"))
    )
    (comp (ref "MT13")
      (value "PINHD-1X2")
      (footprint "eagle-import:1X02")
      (libsource (lib "eagle-import") (part "PINHD-1X2"))
    )
    (comp (ref "MT14")
      (value "PINHD-1X2")
      (footprint "eagle-import:1X02")
      (libsource (lib "eagle-import") (part "PINHD-1X2"))
    )
    (comp (ref "MT15")
      (value "PINHD-1X2")
      (footprint "eagle-import:1X02")
      (libsource (lib "eagle-import") (part "PINHD-1X2"))
    )
    (comp (ref "MT16")
      (value "PINHD-1X2")
      (footprint "eagle-import:1X02")
      (libsource (lib "eagle-import") (part "PINHD-1X2"))
    )
    (comp (ref "MT17")
      (value "PINHD-1X2")
      (footprint "eagle-import:1X02")
      (libsource (lib "eagle-import") (part "PINHD-1X2"))
    )
    (comp (ref "MT18")
      (value "PINHD-1X2")
      (footprint "eagle-import:1X02")
      (libsource (lib "eagle-import") (part "PINHD-1X2"))
    )
    (comp (ref "MT19")
      (value "PINHD-1X2")
      (footprint "eagle-import:1X02")
      (libsource (lib "eagle-import") (part "PINHD-1X2"))
    )
    (comp (ref "MT20")
      (value "PINHD-1X2")
      (footprint "eagle-import:1X02")
      (libsource (lib "eagle-import") (part "PINHD-1X2"))
    )
    (comp (ref "MT21")
      (value "PINHD-1X2")
      (footprint "eagle-import:1X02")
      (libsource (lib "eagle-import") (part "PINHD-1X2"))
    )
    (comp (ref "MT22")
      (value "PINHD-1X2")
      (footprint "eagle-import:1X02")
      (libsource (lib "eagle-import") (part "PINHD-1X2"))
    )
    (comp (ref "MT23")
      (value "PINHD-1X2")
      (footprint "eagle-import:1X02")
      (libsource (lib "eagle-import") (part "PINHD-1X2"))
    )
    (comp (ref "MT24")
      (value "PINHD-1X2")
      (footprint "eagle-import:1X02")
      (libsource (lib "eagle-import") (part "PINHD-1X2"))
    )
    (comp (ref "MT25")
      (value "PINHD-1X2")
      (footprint "eagle-import:1X02")
      (libsource (lib "eagle-import") (part "PINHD-1X2"))
    )
    (comp (ref "MT26")
      (value "PINHD-1X2")
      (footprint "eagle-import:1X02")
      (libsource (lib "eagle-import") (part "PINHD-1X2"))
    )
    (comp (ref "MT27")
      (value "PINHD-1X2")
      (footprint "eagle-import:1X02")
      (libsource (lib "eagle-import") (part "PINHD-1X2"))
    )
    (comp (ref "MT28")
      (value "PINHD-1X2")
      (footprint "eagle-import:1X02")
      (libsource (lib "eagle-import") (part "PINHD-1X2"))
    )
    (comp (ref "MT29")
      (value "PINHD-1X2")
      (footprint "eagle-import:1X02")
      (libsource (lib "eagle-import") (part "PINHD-1X2"))
    )
    (comp (ref "MT30")
      (value "PINHD-1X2")
      (footprint "eagle-import:1X02")
      (libsource (lib "eagle-import") (part "PINHD-1X2"))
    )
    (comp (ref "MT31")
      (value "PINHD-1X2")
      (footprint "eagle-import:1X02")
      (libsource (lib "eagle-import") (part "PINHD-1X2"))
    )
    (comp (ref "MT32")
      (value "PINHD-1X2")
      (footprint "eagle-import:1X02")
      (libsource (lib "eagle-import") (part "PINHD-1X2"))
    )
    (comp (ref "MT33")
      (value "PINHD-1X2")
      (footprint "eagle-import:1X02")
      (libsource (lib "eagle-import") (part "PINHD-1X2"))
    )
    (comp (ref "MT34")
      (value "PINHD-1X2")
      (footprint "eagle-import:1X02")
      (libsource (lib "eagle-import") (part "PINHD-1X2"))
    )
    (comp (ref "MT35")
      (value "PINHD-1X2")
      (footprint "eagle-import:1X02")
      (libsource (lib "eagle-import") (part "PINHD-1X2"))
    )
    (comp (ref "MT36")
      (value "PINHD-1X2")
      (footprint "eagle-import:1X02")
      (libsource (lib "eagle-import") (part "PINHD-1X2"))
    )
    (comp (ref "MT37")
      (value "PINHD-1X2")
      (footprint "eagle-import:1X02")
      (libsource (lib "eagle-import") (part "PINHD-1X2"))
    )
    (comp (ref "MT38")
      (value "PINHD-1X2")
      (footprint "eagle-import:1X02")
      (libsource (lib "eagle-import") (part "PINHD-1X2"))
    )
    (comp (ref "MT39")
      (value "PINHD-1X2")
      (footprint "eagle-import:1X02")
      (libsource (lib "eagle-import") (part "PINHD-1X2"))
    )
    (comp (ref "MT40")
      (value "PINHD-1X2")
      (footprint "eagle-import:1X02")
      (libsource (lib "eagle-import") (part "PINHD-1X2"))
    )
    (comp (ref "MT41")
      (value "PINHD-1X2")
      (footprint "eagle-import:1X02")
      (libsource (lib "eagle-import") (part "PINHD-1X2"))
    )
    (comp (ref "MT42")
      (value "PINHD-1X2")
      (footprint "eagle-import:1X02")
      (libsource (lib "eagle-import") (part "PINHD-1X2"))
    )
    (comp (ref "MT43")
      (value "PINHD-1X2")
      (footprint "eagle-import:1X02")
      (libsource (lib "eagle-import") (part "PINHD-1X2"))
    )
    (comp (ref "MT44")
      (value "PINHD-1X2")
      (footprint "eagle-import:1X02")
      (libsource (lib "eagle-import") (part "PINHD-1X2"))
    )
    (comp (ref "MT45")
      (value "PINHD-1X2")
      (footprint "eagle-import:1X02")
      (libsource (lib "eagle-import") (part "PINHD-1X2"))
    )
    (comp (ref "MT46")
      (value "PINHD-1X2")
      (footprint "eagle-import:1X02")
      (libsource (lib "eagle-import") (part "PINHD-1X2"))
    )
    (comp (ref "MT47")
      (value "PINHD-1X2")
      (footprint "eagle-import:1X02")
      (libsource (lib "eagle-import") (part "PINHD-1X2"))
    )
    (comp (ref "MT48")
      (value "PINHD-1X2")
      (footprint "eagle-import:1X02")
      (libsource (lib "eagle-import") (part "PINHD-1X2"))
    )
    (comp (ref "MT49")
      (value "PINHD-1X2")
      (footprint "eagle-import:1X02")
      (libsource (lib "eagle-import") (part "PINHD-1X2"))
    )
    (comp (ref "MT50")
      (value "PINHD-1X2")
      (footprint "eagle-import:1X02")
      (libsource (lib "eagle-import") (part "PINHD-1X2"))
    )
    (comp (ref "MT51")
      (value "PINHD-1X2")
      (footprint "eagle-import:1X02")
      (libsource (lib "eagle-import") (part "PINHD-1X2"))
    )
    (comp (ref "MT52")
      (value "PINHD-1X2")
      (footprint "eagle-import:1X02")
      (libsource (lib "eagle-import") (part "PINHD-1X2"))
    )
    (comp (ref "MT53")
      (value "PINHD-1X2")
      (footprint "eagle-import:1X02")
      (libsource (lib "eagle-import") (part "PINHD-1X2"))
    )
    (comp (ref "MT54")
      (value "PINHD-1X2")
      (footprint "eagle-import:1X02")
      (libsource (lib "eagle-import") (part "PINHD-1X2"))
    )
    (comp (ref "MT55")
      (value "PINHD-1X2")
      (footprint "eagle-import:1X02")
      (libsource (lib "eagle-import") (part "PINHD-1X2"))
    )
    (comp (ref "MT56")
      (value "PINHD-1X2")
      (footprint "eagle-import:1X02")
      (libsource (lib "eagle-import") (part "PINHD-1X2"))
    )
    (comp (ref "MT57")
      (value "PINHD-1X2")
      (footprint "eagle-import:1X02")
      (libsource (lib "eagle-import") (part "PINHD-1X2"))
    )
    (comp (ref "MT58")
      (value "PINHD-1X2")
      (footprint "eagle-import:1X02")
      (libsource (lib "eagle-import") (part "PINHD-1X2"))
    )
    (comp (ref "MT59")
      (value "PINHD-1X2")
      (footprint "eagle-import:1X02")
      (libsource (lib "eagle-import") (part "PINHD-1X2"))
    )
    (comp (ref "MT60")
      (value "PINHD-1X2")
      (footprint "eagle-import:1X02")
      (libsource (lib "eagle-import") (part "PINHD-1X2"))
    )
    (comp (ref "MT61")
      (value "PINHD-1X2")
      (footprint "eagle-import:1X02")
      (libsource (lib "eagle-import") (part "PINHD-1X2"))
    )
    (comp (ref "MT62")
      (value "PINHD-1X2")
      (footprint "eagle-import:1X02")
      (libsource (lib "eagle-import") (part "PINHD-1X2"))
    )
    (comp (ref "MT63")
      (value "PINHD-1X2")
      (footprint "eagle-import:1X02")
      (libsource (lib "eagle-import") (part "PINHD-1X2"))
    )
    (comp (ref "MT64")
      (value "PINHD-1X2")
      (footprint "eagle-import:1X02")
      (libsource (lib "eagle-import") (part "PINHD-1X2"))
    )
    (comp (ref "MT65")
      (value "PINHD-1X2")
      (footprint "eagle-import:1X02")
      (libsource (lib "eagle-import") (part "PINHD-1X2"))
    )
    (comp (ref "MT66")
      (value "PINHD-1X2")
      (footprint "eagle-import:1X02")
      (libsource (lib "eagle-import") (part "PINHD-1X2"))
    )
    (comp (ref "MT67")
      (value "PINHD-1X2")
      (footprint "eagle-import:1X02")
      (libsource (lib "eagle-import") (part "PINHD-1X2"))
    )
    (comp (ref "MT68")
      (value "PINHD-1X2")
      (footprint "eagle-import:1X02")
      (libsource (lib "eagle-import") (part "PINHD-1X2"))
    )
    (comp (ref "MT69")
      (value "PINHD-1X2")
      (footprint "eagle-import:1X02")
      (libsource (lib "eagle-import") (part "PINHD-1X2"))
    )
    (comp (ref "MT70")
      (value "PINHD-1X2")
      (footprint "eagle-import:1X02")
      (libsource (lib "eagle-import") (part "PINHD-1X2"))
    )
    (comp (ref "MT71")
      (value "PINHD-1X2")
      (footprint "eagle-import:1X02")
      (libsource (lib "eagle-import") (part "PINHD-1X2"))
    )
    (comp (ref "MT72")
      (value "PINHD-1X2")
      (footprint "eagle-import:1X02")
      (libsource (lib "eagle-import") (part "PINHD-1X2"))
    )
    (comp (ref "MT73")
      (value "PINHD-1X2")
      (footprint "eagle-import:1X02")
      (libsource (lib "eagle-import") (part "PINHD-1X2"))
    )
    (comp (ref "MT74")
      (value "PINHD-1X2")
      (footprint "eagle-import:1X02")
      (libsource (lib "eagle-import") (part "PINHD-1X2"))
    )
    (comp (ref "MT75")
      (value "PINHD-1X2")
      (footprint "eagle-import:1X02")
      (libsource (lib "eagle-import") (part "PINHD-1X2"))
    )
    (comp (ref "MT76")
      (value "PINHD-1X2")
      (footprint "eagle-import:1X02")
      (libsource (lib "eagle-import") (part "PINHD-1X2"))
    )
    (comp (ref "MT77")
      (value "PINHD-1X2")
      (footprint "eagle-import:1X02")
      (libsource (lib "eagle-import") (part "PINHD-1X2"))
    )
    (comp (ref "MT78")
      (value "PINHD-1X2")
      (footprint "eagle-import:1X02")
      (libsource (lib "eagle-import") (part "PINHD-1X2"))
    )
    (comp (ref "MT79")
      (value "PINHD-1X2")
      (footprint "eagle-import:1X02")
      (libsource (lib "eagle-import") (part "PINHD-1X2"))
    )
    (comp (ref "MT80")
      (value "PINHD-1X2")
      (footprint "eagle-import:1X02")
      (libsource (lib "eagle-import") (part "PINHD-1X2"))
    )
    (comp (ref "MT81")
      (value "PINHD-1X2")
      (footprint "eagle-import:1X02")
      (libsource (lib "eagle-import") (part "PINHD-1X2"))
    )
    (comp (ref "MT82")
      (value "PINHD-1X2")
      (footprint "eagle-import:1X02")
      (libsource (lib "eagle-import") (part "PINHD-1X2"))
    )
    (comp (ref "MT83")
      (value "PINHD-1X2")
      (footprint "eagle-import:1X02")
      (libsource (lib "eagle-import") (part "PINHD-1X2"))
    )
    (comp (ref "MT84")
      (value "PINHD-1X2")
      (footprint "eagle-import:1X02")
      (libsource (lib "eagle-import") (part "PINHD-1X2"))
    )
    (comp (ref "MT85")
      (value "PINHD-1X2")
      (footprint "eagle-import:1X02")
      (libsource (lib "eagle-import") (part "PINHD-1X2"))
    )
    (comp (ref "MT86")
      (value "PINHD-1X2")
      (footprint "eagle-import:1X02")
      (libsource (lib "eagle-import") (part "PINHD-1X2"))
    )
    (comp (ref "MT87")
      (value "PINHD-1X2")
      (footprint "eagle-import:1X02")
      (libsource (lib "eagle-import") (part "PINHD-1X2"))
    )
    (comp (ref "MT88")
      (value "PINHD-1X2")
      (footprint "eagle-import:1X02")
      (libsource (lib "eagle-import") (part "PINHD-1X2"))
    )
    (comp (ref "MT89")
      (value "PINHD-1X2")
      (footprint "eagle-import:1X02")
      (libsource (lib "eagle-import") (part "PINHD-1X2"))
    )
    (comp (ref "MT90")
      (value "PINHD-1X2")
      (footprint "eagle-import:1X02")
      (libsource (lib "eagle-import") (part "PINHD-1X2"))
    )
    (comp (ref "MT91")
      (value "PINHD-1X2")
      (footprint "eagle-import:1X02")
      (libsource (lib "eagle-import") (part "PINHD-1X2"))
    )
    (comp (ref "MT92")
      (value "PINHD-1X2")
      (footprint "eagle-import:1X02")
      (libsource (lib "eagle-import") (part "PINHD-1X2"))
    )
    (comp (ref "MT93")
      (value "PINHD-1X2")
      (footprint "eagle-import:1X02")
      (libsource (lib "eagle-import") (part "PINHD-1X2"))
    )
    (comp (ref "MT94")
      (value "PINHD-1X2")
      (footprint "eagle-import:1X02")
      (libsource (lib "eagle-import") (part "PINHD-1X2"))
    )
    (comp (ref "MT95")
      (value "PINHD-1X2")
      (footprint "eagle-import:1X02")
      (libsource (lib "eagle-import") (part "PINHD-1X2"))
    )
    (comp (ref "MT96")
      (value "PINHD-1X2")
      (footprint "eagle-import:1X02")
      (libsource (lib "eagle-import") (part "PINHD-1X2"))
    )
    (comp (ref "R1")
      (value "1k")
      (footprint "eagle-import:0411_15")
      (libsource (lib "eagle-import") (part "R-EU_0411/15"))
    )
    (comp (ref "R2")
      (value "1k")
      (footprint "eagle-import:0411_15")
      (libsource (lib "eagle-import") (part "R-EU_0411/15"))
    )
    (comp (ref "R3")
      (value "1k")
      (footprint "eagle-import:0411_15")
      (libsource (lib "eagle-import") (part "R-EU_0411/15"))
    )
    (comp (ref "R4")
      (value "1k")
      (footprint "eagle-import:0411_15")
      (libsource (lib "eagle-import") (part "R-EU_0411/15"))
    )
    (comp (ref "R5")
      (value "1k")
      (footprint "eagle-import:0411_15")
      (libsource (lib "eagle-import") (part "R-EU_0411/15"))
    )
    (comp (ref "R6")
      (value "1k")
      (footprint "eagle-import:0411_15")
      (libsource (lib "eagle-import") (part "R-EU_0411/15"))
    )
    (comp (ref "R7")
      (value "1k")
      (footprint "eagle-import:0411_15")
      (libsource (lib "eagle-import") (part "R-EU_0411/15"))
    )
    (comp (ref "R8")
      (value "1k")
      (footprint "eagle-import:0411_15")
      (libsource (lib "eagle-import") (part "R-EU_0411/15"))
    )
    (comp (ref "R9")
      (value "1k")
      (footprint "eagle-import:0411_15")
      (libsource (lib "eagle-import") (part "R-EU_0411/15"))
    )
    (comp (ref "R10")
      (value "1k")
      (footprint "eagle-import:0411_15")
      (libsource (lib "eagle-import") (part "R-EU_0411/15"))
    )
    (comp (ref "R11")
      (value "1k")
      (footprint "eagle-import:0411_15")
      (libsource (lib "eagle-import") (part "R-EU_0411/15"))
    )
    (comp (ref "R12")
      (value "1k")
      (footprint "eagle-import:0411_15")
      (libsource (lib "eagle-import") (part "R-EU_0411/15"))
    )
    (comp (ref "R13")
      (value "1k")
      (footprint "eagle-import:0411_15")
      (libsource (lib "eagle-import") (part "R-EU_0411/15"))
    )
    (comp (ref "R14")
      (value "1k")
      (footprint "eagle-import:0411_15")
      (libsource (lib "eagle-import") (part "R-EU_0411/15"))
    )
    (comp (ref "R15")
      (value "1k")
      (footprint "eagle-import:0411_15")
      (libsource (lib "eagle-import") (part "R-EU_0411/15"))
    )
    (comp (ref "R16")
      (value "1k")
      (footprint "eagle-import:0411_15")
      (libsource (lib "eagle-import") (part "R-EU_0411/15"))
    )
    (comp (ref "R17")
      (value "1k")
      (footprint "eagle-import:0411_15")
      (libsource (lib "eagle-import") (part "R-EU_0411/15"))
    )
    (comp (ref "R18")
      (value "1k")
      (footprint "eagle-import:0411_15")
      (libsource (lib "eagle-import") (part "R-EU_0411/15"))
    )
    (comp (ref "R19")
      (value "1k")
      (footprint "eagle-import:0411_15")
      (libsource (lib "eagle-import") (part "R-EU_0411/15"))
    )
    (comp (ref "R20")
      (value "1k")
      (footprint "eagle-import:0411_15")
      (libsource (lib "eagle-import") (part "R-EU_0411/15"))
    )
    (comp (ref "R21")
      (value "1k")
      (footprint "eagle-import:0411_15")
      (libsource (lib "eagle-import") (part "R-EU_0411/15"))
    )
    (comp (ref "R22")
      (value "1k")
      (footprint "eagle-import:0411_15")
      (libsource (lib "eagle-import") (part "R-EU_0411/15"))
    )
    (comp (ref "R23")
      (value "1k")
      (footprint "eagle-import:0411_15")
      (libsource (lib "eagle-import") (part "R-EU_0411/15"))
    )
    (comp (ref "R24")
      (value "1k")
      (footprint "eagle-import:0411_15")
      (libsource (lib "eagle-import") (part "R-EU_0411/15"))
    )
    (comp (ref "R25")
      (value "1k")
      (footprint "eagle-import:0411_15")
      (libsource (lib "eagle-import") (part "R-EU_0411/15"))
    )
    (comp (ref "R26")
      (value "1k")
      (footprint "eagle-import:0411_15")
      (libsource (lib "eagle-import") (part "R-EU_0411/15"))
    )
    (comp (ref "R27")
      (value "1k")
      (footprint "eagle-import:0411_15")
      (libsource (lib "eagle-import") (part "R-EU_0411/15"))
    )
    (comp (ref "R28")
      (value "1k")
      (footprint "eagle-import:0411_15")
      (libsource (lib "eagle-import") (part "R-EU_0411/15"))
    )
    (comp (ref "R29")
      (value "1k")
      (footprint "eagle-import:0411_15")
      (libsource (lib "eagle-import") (part "R-EU_0411/15"))
    )
    (comp (ref "R30")
      (value "1k")
      (footprint "eagle-import:0411_15")
      (libsource (lib "eagle-import") (part "R-EU_0411/15"))
    )
    (comp (ref "R31")
      (value "1k")
      (footprint "eagle-import:0411_15")
      (libsource (lib "eagle-import") (part "R-EU_0411/15"))
    )
    (comp (ref "R32")
      (value "1k")
      (footprint "eagle-import:0411_15")
      (libsource (lib "eagle-import") (part "R-EU_0411/15"))
    )
    (comp (ref "R33")
      (value "1k")
      (footprint "eagle-import:0411_15")
      (libsource (lib "eagle-import") (part "R-EU_0411/15"))
    )
    (comp (ref "R34")
      (value "1k")
      (footprint "eagle-import:0411_15")
      (libsource (lib "eagle-import") (part "R-EU_0411/15"))
    )
    (comp (ref "R35")
      (value "1k")
      (footprint "eagle-import:0411_15")
      (libsource (lib "eagle-import") (part "R-EU_0411/15"))
    )
    (comp (ref "R36")
      (value "1k")
      (footprint "eagle-import:0411_15")
      (libsource (lib "eagle-import") (part "R-EU_0411/15"))
    )
    (comp (ref "R37")
      (value "1k")
      (footprint "eagle-import:0411_15")
      (libsource (lib "eagle-import") (part "R-EU_0411/15"))
    )
    (comp (ref "R38")
      (value "1k")
      (footprint "eagle-import:0411_15")
      (libsource (lib "eagle-import") (part "R-EU_0411/15"))
    )
    (comp (ref "R39")
      (value "1k")
      (footprint "eagle-import:0411_15")
      (libsource (lib "eagle-import") (part "R-EU_0411/15"))
    )
    (comp (ref "R40")
      (value "1k")
      (footprint "eagle-import:0411_15")
      (libsource (lib "eagle-import") (part "R-EU_0411/15"))
    )
    (comp (ref "R41")
      (value "1k")
      (footprint "eagle-import:0411_15")
      (libsource (lib "eagle-import") (part "R-EU_0411/15"))
    )
    (comp (ref "R42")
      (value "1k")
      (footprint "eagle-import:0411_15")
      (libsource (lib "eagle-import") (part "R-EU_0411/15"))
    )
    (comp (ref "R43")
      (value "1k")
      (footprint "eagle-import:0411_15")
      (libsource (lib "eagle-import") (part "R-EU_0411/15"))
    )
    (comp (ref "R44")
      (value "1k")
      (footprint "eagle-import:0411_15")
      (libsource (lib "eagle-import") (part "R-EU_0411/15"))
    )
    (comp (ref "R45")
      (value "1k")
      (footprint "eagle-import:0411_15")
      (libsource (lib "eagle-import") (part "R-EU_0411/15"))
    )
    (comp (ref "R46")
      (value "1k")
      (footprint "eagle-import:0411_15")
      (libsource (lib "eagle-import") (part "R-EU_0411/15"))
    )
    (comp (ref "R47")
      (value "1k")
      (footprint "eagle-import:0411_15")
      (libsource (lib "eagle-import") (part "R-EU_0411/15"))
    )
    (comp (ref "R48")
      (value "1k")
      (footprint "eagle-import:0411_15")
      (libsource (lib "eagle-import") (part "R-EU_0411/15"))
    )
    (comp (ref "R49")
      (value "1k")
      (footprint "eagle-import:0411_15")
      (libsource (lib "eagle-import") (part "R-EU_0411/15"))
    )
    (comp (ref "R50")
      (value "1k")
      (footprint "eagle-import:0411_15")
      (libsource (lib "eagle-import") (part "R-EU_0411/15"))
    )
    (comp (ref "R51")
      (value "1k")
      (footprint "eagle-import:0411_15")
      (libsource (lib "eagle-import") (part "R-EU_0411/15"))
    )
    (comp (ref "R52")
      (value "1k")
      (footprint "eagle-import:0411_15")
      (libsource (lib "eagle-import") (part "R-EU_0411/15"))
    )
    (comp (ref "R53")
      (value "1k")
      (footprint "eagle-import:0411_15")
      (libsource (lib "eagle-import") (part "R-EU_0411/15"))
    )
    (comp (ref "R54")
      (value "1k")
      (footprint "eagle-import:0411_15")
      (libsource (lib "eagle-import") (part "R-EU_0411/15"))
    )
    (comp (ref "R55")
      (value "1k")
      (footprint "eagle-import:0411_15")
      (libsource (lib "eagle-import") (part "R-EU_0411/15"))
    )
    (comp (ref "R56")
      (value "1k")
      (footprint "eagle-import:0411_15")
      (libsource (lib "eagle-import") (part "R-EU_0411/15"))
    )
    (comp (ref "R57")
      (value "1k")
      (footprint "eagle-import:0411_15")
      (libsource (lib "eagle-import") (part "R-EU_0411/15"))
    )
    (comp (ref "R58")
      (value "1k")
      (footprint "eagle-import:0411_15")
      (libsource (lib "eagle-import") (part "R-EU_0411/15"))
    )
    (comp (ref "R59")
      (value "1k")
      (footprint "eagle-import:0411_15")
      (libsource (lib "eagle-import") (part "R-EU_0411/15"))
    )
    (comp (ref "R60")
      (value "1k")
      (footprint "eagle-import:0411_15")
      (libsource (lib "eagle-import") (part "R-EU_0411/15"))
    )
    (comp (ref "R61")
      (value "1k")
      (footprint "eagle-import:0411_15")
      (libsource (lib "eagle-import") (part "R-EU_0411/15"))
    )
    (comp (ref "R62")
      (value "1k")
      (footprint "eagle-import:0411_15")
      (libsource (lib "eagle-import") (part "R-EU_0411/15"))
    )
    (comp (ref "R63")
      (value "1k")
      (footprint "eagle-import:0411_15")
      (libsource (lib "eagle-import") (part "R-EU_0411/15"))
    )
    (comp (ref "R64")
      (value "1k")
      (footprint "eagle-import:0411_15")
      (libsource (lib "eagle-import") (part "R-EU_0411/15"))
    )
    (comp (ref "R65")
      (value "1k")
      (footprint "eagle-import:0411_15")
      (libsource (lib "eagle-import") (part "R-EU_0411/15"))
    )
    (comp (ref "R66")
      (value "1k")
      (footprint "eagle-import:0411_15")
      (libsource (lib "eagle-import") (part "R-EU_0411/15"))
    )
    (comp (ref "R67")
      (value "1k")
      (footprint "eagle-import:0411_15")
      (libsource (lib "eagle-import") (part "R-EU_0411/15"))
    )
    (comp (ref "R68")
      (value "1k")
      (footprint "eagle-import:0411_15")
      (libsource (lib "eagle-import") (part "R-EU_0411/15"))
    )
    (comp (ref "R69")
      (value "1k")
      (footprint "eagle-import:0411_15")
      (libsource (lib "eagle-import") (part "R-EU_0411/15"))
    )
    (comp (ref "R70")
      (value "1k")
      (footprint "eagle-import:0411_15")
      (libsource (lib "eagle-import") (part "R-EU_0411/15"))
    )
    (comp (ref "R71")
      (value "1k")
      (footprint "eagle-import:0411_15")
      (libsource (lib "eagle-import") (part "R-EU_0411/15"))
    )
    (comp (ref "R72")
      (value "1k")
      (footprint "eagle-import:0411_15")
      (libsource (lib "eagle-import") (part "R-EU_0411/15"))
    )
    (comp (ref "R73")
      (value "1k")
      (footprint "eagle-import:0411_15")
      (libsource (lib "eagle-import") (part "R-EU_0411/15"))
    )
    (comp (ref "R74")
      (value "1k")
      (footprint "eagle-import:0411_15")
      (libsource (lib "eagle-import") (part "R-EU_0411/15"))
    )
    (comp (ref "R75")
      (value "1k")
      (footprint "eagle-import:0411_15")
      (libsource (lib "eagle-import") (part "R-EU_0411/15"))
    )
    (comp (ref "R76")
      (value "1k")
      (footprint "eagle-import:0411_15")
      (libsource (lib "eagle-import") (part "R-EU_0411/15"))
    )
    (comp (ref "R77")
      (value "1k")
      (footprint "eagle-import:0411_15")
      (libsource (lib "eagle-import") (part "R-EU_0411/15"))
    )
    (comp (ref "R78")
      (value "1k")
      (footprint "eagle-import:0411_15")
      (libsource (lib "eagle-import") (part "R-EU_0411/15"))
    )
    (comp (ref "R79")
      (value "1k")
      (footprint "eagle-import:0411_15")
      (libsource (lib "eagle-import") (part "R-EU_0411/15"))
    )
    (comp (ref "R80")
      (value "1k")
      (footprint "eagle-import:0411_15")
      (libsource (lib "eagle-import") (part "R-EU_0411/15"))
    )
    (comp (ref "R81")
      (value "1k")
      (footprint "eagle-import:0411_15")
      (libsource (lib "eagle-import") (part "R-EU_0411/15"))
    )
    (comp (ref "R82")
      (value "1k")
      (footprint "eagle-import:0411_15")
      (libsource (lib "eagle-import") (part "R-EU_0411/15"))
    )
    (comp (ref "R83")
      (value "1k")
      (footprint "eagle-import:0411_15")
      (libsource (lib "eagle-import") (part "R-EU_0411/15"))
    )
    (comp (ref "R84")
      (value "1k")
      (footprint "eagle-import:0411_15")
      (libsource (lib "eagle-import") (part "R-EU_0411/15"))
    )
    (comp (ref "R85")
      (value "1k")
      (footprint "eagle-import:0411_15")
      (libsource (lib "eagle-import") (part "R-EU_0411/15"))
    )
    (comp (ref "R86")
      (value "1k")
      (footprint "eagle-import:0411_15")
      (libsource (lib "eagle-import") (part "R-EU_0411/15"))
    )
    (comp (ref "R87")
      (value "1k")
      (footprint "eagle-import:0411_15")
      (libsource (lib "eagle-import") (part "R-EU_0411/15"))
    )
    (comp (ref "R88")
      (value "1k")
      (footprint "eagle-import:0411_15")
      (libsource (lib "eagle-import") (part "R-EU_0411/15"))
    )
    (comp (ref "R89")
      (value "1k")
      (footprint "eagle-import:0411_15")
      (libsource (lib "eagle-import") (part "R-EU_0411/15"))
    )
    (comp (ref "R90")
      (value "1k")
      (footprint "eagle-import:0411_15")
      (libsource (lib "eagle-import") (part "R-EU_0411/15"))
    )
    (comp (ref "R91")
      (value "1k")
      (footprint "eagle-import:0411_15")
      (libsource (lib "eagle-import") (part "R-EU_0411/15"))
    )
    (comp (ref "R92")
      (value "1k")
      (footprint "eagle-import:0411_15")
      (libsource (lib "eagle-import") (part "R-EU_0411/15"))
    )
    (comp (ref "R93")
      (value "1k")
      (footprint "eagle-import:0411_15")
      (libsource (lib "eagle-import") (part "R-EU_0411/15"))
    )
    (comp (ref "R94")
      (value "1k")
      (footprint "eagle-import:0411_15")
      (libsource (lib "eagle-import") (part "R-EU_0411/15"))
    )
    (comp (ref "R95")
      (value "1k")
      (footprint "eagle-import:0411_15")
      (libsource (lib "eagle-import") (part "R-EU_0411/15"))
    )
    (comp (ref "R96")
      (value "1k")
      (footprint "eagle-import:0411_15")
      (libsource (lib "eagle-import") (part "R-EU_0411/15"))
    )
    (comp (ref "T1")
      (value "2N2222")
      (footprint "eagle-import:TO18")
      (libsource (lib "eagle-import") (part "2N2222"))
    )
    (comp (ref "T2")
      (value "2N2222")
      (footprint "eagle-import:TO18")
      (libsource (lib "eagle-import") (part "2N2222"))
    )
    (comp (ref "T3")
      (value "2N2222")
      (footprint "eagle-import:TO18")
      (libsource (lib "eagle-import") (part "2N2222"))
    )
    (comp (ref "T4")
      (value "2N2222")
      (footprint "eagle-import:TO18")
      (libsource (lib "eagle-import") (part "2N2222"))
    )
    (comp (ref "T5")
      (value "2N2222")
      (footprint "eagle-import:TO18")
      (libsource (lib "eagle-import") (part "2N2222"))
    )
    (comp (ref "T6")
      (value "2N2222")
      (footprint "eagle-import:TO18")
      (libsource (lib "eagle-import") (part "2N2222"))
    )
    (comp (ref "T7")
      (value "2N2222")
      (footprint "eagle-import:TO18")
      (libsource (lib "eagle-import") (part "2N2222"))
    )
    (comp (ref "T8")
      (value "2N2222")
      (footprint "eagle-import:TO18")
      (libsource (lib "eagle-import") (part "2N2222"))
    )
    (comp (ref "T9")
      (value "2N2222")
      (footprint "eagle-import:TO18")
      (libsource (lib "eagle-import") (part "2N2222"))
    )
    (comp (ref "T10")
      (value "2N2222")
      (footprint "eagle-import:TO18")
      (libsource (lib "eagle-import") (part "2N2222"))
    )
    (comp (ref "T11")
      (value "2N2222")
      (footprint "eagle-import:TO18")
      (libsource (lib "eagle-import") (part "2N2222"))
    )
    (comp (ref "T12")
      (value "2N2222")
      (footprint "eagle-import:TO18")
      (libsource (lib "eagle-import") (part "2N2222"))
    )
    (comp (ref "T13")
      (value "2N2222")
      (footprint "eagle-import:TO18")
      (libsource (lib "eagle-import") (part "2N2222"))
    )
    (comp (ref "T14")
      (value "2N2222")
      (footprint "eagle-import:TO18")
      (libsource (lib "eagle-import") (part "2N2222"))
    )
    (comp (ref "T15")
      (value "2N2222")
      (footprint "eagle-import:TO18")
      (libsource (lib "eagle-import") (part "2N2222"))
    )
    (comp (ref "T16")
      (value "2N2222")
      (footprint "eagle-import:TO18")
      (libsource (lib "eagle-import") (part "2N2222"))
    )
    (comp (ref "T17")
      (value "2N2222")
      (footprint "eagle-import:TO18")
      (libsource (lib "eagle-import") (part "2N2222"))
    )
    (comp (ref "T18")
      (value "2N2222")
      (footprint "eagle-import:TO18")
      (libsource (lib "eagle-import") (part "2N2222"))
    )
    (comp (ref "T19")
      (value "2N2222")
      (footprint "eagle-import:TO18")
      (libsource (lib "eagle-import") (part "2N2222"))
    )
    (comp (ref "T20")
      (value "2N2222")
      (footprint "eagle-import:TO18")
      (libsource (lib "eagle-import") (part "2N2222"))
    )
    (comp (ref "T21")
      (value "2N2222")
      (footprint "eagle-import:TO18")
      (libsource (lib "eagle-import") (part "2N2222"))
    )
    (comp (ref "T22")
      (value "2N2222")
      (footprint "eagle-import:TO18")
      (libsource (lib "eagle-import") (part "2N2222"))
    )
    (comp (ref "T23")
      (value "2N2222")
      (footprint "eagle-import:TO18")
      (libsource (lib "eagle-import") (part "2N2222"))
    )
    (comp (ref "T24")
      (value "2N2222")
      (footprint "eagle-import:TO18")
      (libsource (lib "eagle-import") (part "2N2222"))
    )
    (comp (ref "T25")
      (value "2N2222")
      (footprint "eagle-import:TO18")
      (libsource (lib "eagle-import") (part "2N2222"))
    )
    (comp (ref "T26")
      (value "2N2222")
      (footprint "eagle-import:TO18")
      (libsource (lib "eagle-import") (part "2N2222"))
    )
    (comp (ref "T27")
      (value "2N2222")
      (footprint "eagle-import:TO18")
      (libsource (lib "eagle-import") (part "2N2222"))
    )
    (comp (ref "T28")
      (value "2N2222")
      (footprint "eagle-import:TO18")
      (libsource (lib "eagle-import") (part "2N2222"))
    )
    (comp (ref "T29")
      (value "2N2222")
      (footprint "eagle-import:TO18")
      (libsource (lib "eagle-import") (part "2N2222"))
    )
    (comp (ref "T30")
      (value "2N2222")
      (footprint "eagle-import:TO18")
      (libsource (lib "eagle-import") (part "2N2222"))
    )
    (comp (ref "T31")
      (value "2N2222")
      (footprint "eagle-import:TO18")
      (libsource (lib "eagle-import") (part "2N2222"))
    )
    (comp (ref "T32")
      (value "2N2222")
      (footprint "eagle-import:TO18")
      (libsource (lib "eagle-import") (part "2N2222"))
    )
    (comp (ref "T33")
      (value "2N2222")
      (footprint "eagle-import:TO18")
      (libsource (lib "eagle-import") (part "2N2222"))
    )
    (comp (ref "T34")
      (value "2N2222")
      (footprint "eagle-import:TO18")
      (libsource (lib "eagle-import") (part "2N2222"))
    )
    (comp (ref "T35")
      (value "2N2222")
      (footprint "eagle-import:TO18")
      (libsource (lib "eagle-import") (part "2N2222"))
    )
    (comp (ref "T36")
      (value "2N2222")
      (footprint "eagle-import:TO18")
      (libsource (lib "eagle-import") (part "2N2222"))
    )
    (comp (ref "T37")
      (value "2N2222")
      (footprint "eagle-import:TO18")
      (libsource (lib "eagle-import") (part "2N2222"))
    )
    (comp (ref "T38")
      (value "2N2222")
      (footprint "eagle-import:TO18")
      (libsource (lib "eagle-import") (part "2N2222"))
    )
    (comp (ref "T39")
      (value "2N2222")
      (footprint "eagle-import:TO18")
      (libsource (lib "eagle-import") (part "2N2222"))
    )
    (comp (ref "T40")
      (value "2N2222")
      (footprint "eagle-import:TO18")
      (libsource (lib "eagle-import") (part "2N2222"))
    )
    (comp (ref "T41")
      (value "2N2222")
      (footprint "eagle-import:TO18")
      (libsource (lib "eagle-import") (part "2N2222"))
    )
    (comp (ref "T42")
      (value "2N2222")
      (footprint "eagle-import:TO18")
      (libsource (lib "eagle-import") (part "2N2222"))
    )
    (comp (ref "T43")
      (value "2N2222")
      (footprint "eagle-import:TO18")
      (libsource (lib "eagle-import") (part "2N2222"))
    )
    (comp (ref "T44")
      (value "2N2222")
      (footprint "eagle-import:TO18")
      (libsource (lib "eagle-import") (part "2N2222"))
    )
    (comp (ref "T45")
      (value "2N2222")
      (footprint "eagle-import:TO18")
      (libsource (lib "eagle-import") (part "2N2222"))
    )
    (comp (ref "T46")
      (value "2N2222")
      (footprint "eagle-import:TO18")
      (libsource (lib "eagle-import") (part "2N2222"))
    )
    (comp (ref "T47")
      (value "2N2222")
      (footprint "eagle-import:TO18")
      (libsource (lib "eagle-import") (part "2N2222"))
    )
    (comp (ref "T48")
      (value "2N2222")
      (footprint "eagle-import:TO18")
      (libsource (lib "eagle-import") (part "2N2222"))
    )
    (comp (ref "T49")
      (value "2N2222")
      (footprint "eagle-import:TO18")
      (libsource (lib "eagle-import") (part "2N2222"))
    )
    (comp (ref "T50")
      (value "2N2222")
      (footprint "eagle-import:TO18")
      (libsource (lib "eagle-import") (part "2N2222"))
    )
    (comp (ref "T51")
      (value "2N2222")
      (footprint "eagle-import:TO18")
      (libsource (lib "eagle-import") (part "2N2222"))
    )
    (comp (ref "T52")
      (value "2N2222")
      (footprint "eagle-import:TO18")
      (libsource (lib "eagle-import") (part "2N2222"))
    )
    (comp (ref "T53")
      (value "2N2222")
      (footprint "eagle-import:TO18")
      (libsource (lib "eagle-import") (part "2N2222"))
    )
    (comp (ref "T54")
      (value "2N2222")
      (footprint "eagle-import:TO18")
      (libsource (lib "eagle-import") (part "2N2222"))
    )
    (comp (ref "T55")
      (value "2N2222")
      (footprint "eagle-import:TO18")
      (libsource (lib "eagle-import") (part "2N2222"))
    )
    (comp (ref "T56")
      (value "2N2222")
      (footprint "eagle-import:TO18")
      (libsource (lib "eagle-import") (part "2N2222"))
    )
    (comp (ref "T57")
      (value "2N2222")
      (footprint "eagle-import:TO18")
      (libsource (lib "eagle-import") (part "2N2222"))
    )
    (comp (ref "T58")
      (value "2N2222")
      (footprint "eagle-import:TO18")
      (libsource (lib "eagle-import") (part "2N2222"))
    )
    (comp (ref "T59")
      (value "2N2222")
      (footprint "eagle-import:TO18")
      (libsource (lib "eagle-import") (part "2N2222"))
    )
    (comp (ref "T60")
      (value "2N2222")
      (footprint "eagle-import:TO18")
      (libsource (lib "eagle-import") (part "2N2222"))
    )
    (comp (ref "T61")
      (value "2N2222")
      (footprint "eagle-import:TO18")
      (libsource (lib "eagle-import") (part "2N2222"))
    )
    (comp (ref "T62")
      (value "2N2222")
      (footprint "eagle-import:TO18")
      (libsource (lib "eagle-import") (part "2N2222"))
    )
    (comp (ref "T63")
      (value "2N2222")
      (footprint "eagle-import:TO18")
      (libsource (lib "eagle-import") (part "2N2222"))
    )
    (comp (ref "T64")
      (value "2N2222")
      (footprint "eagle-import:TO18")
      (libsource (lib "eagle-import") (part "2N2222"))
    )
    (comp (ref "T65")
      (value "2N2222")
      (footprint "eagle-import:TO18")
      (libsource (lib "eagle-import") (part "2N2222"))
    )
    (comp (ref "T66")
      (value "2N2222")
      (footprint "eagle-import:TO18")
      (libsource (lib "eagle-import") (part "2N2222"))
    )
    (comp (ref "T67")
      (value "2N2222")
      (footprint "eagle-import:TO18")
      (libsource (lib "eagle-import") (part "2N2222"))
    )
    (comp (ref "T68")
      (value "2N2222")
      (footprint "eagle-import:TO18")
      (libsource (lib "eagle-import") (part "2N2222"))
    )
    (comp (ref "T69")
      (value "2N2222")
      (footprint "eagle-import:TO18")
      (libsource (lib "eagle-import") (part "2N2222"))
    )
    (comp (ref "T70")
      (value "2N2222")
      (footprint "eagle-import:TO18")
      (libsource (lib "eagle-import") (part "2N2222"))
    )
    (comp (ref "T71")
      (value "2N2222")
      (footprint "eagle-import:TO18")
      (libsource (lib "eagle-import") (part "2N2222"))
    )
    (comp (ref "T72")
      (value "2N2222")
      (footprint "eagle-import:TO18")
      (libsource (lib "eagle-import") (part "2N2222"))
    )
    (comp (ref "T73")
      (value "2N2222")
      (footprint "eagle-import:TO18")
      (libsource (lib "eagle-import") (part "2N2222"))
    )
    (comp (ref "T74")
      (value "2N2222")
      (footprint "eagle-import:TO18")
      (libsource (lib "eagle-import") (part "2N2222"))
    )
    (comp (ref "T75")
      (value "2N2222")
      (footprint "eagle-import:TO18")
      (libsource (lib "eagle-import") (part "2N2222"))
    )
    (comp (ref "T76")
      (value "2N2222")
      (footprint "eagle-import:TO18")
      (libsource (lib "eagle-import") (part "2N2222"))
    )
    (comp (ref "T77")
      (value "2N2222")
      (footprint "eagle-import:TO18")
      (libsource (lib "eagle-import") (part "2N2222"))
    )
    (comp (ref "T78")
      (value "2N2222")
      (footprint "eagle-import:TO18")
      (libsource (lib "eagle-import") (part "2N2222"))
    )
    (comp (ref "T79")
      (value "2N2222")
      (footprint "eagle-import:TO18")
      (libsource (lib "eagle-import") (part "2N2222"))
    )
    (comp (ref "T80")
      (value "2N2222")
      (footprint "eagle-import:TO18")
      (libsource (lib "eagle-import") (part "2N2222"))
    )
    (comp (ref "T81")
      (value "2N2222")
      (footprint "eagle-import:TO18")
      (libsource (lib "eagle-import") (part "2N2222"))
    )
    (comp (ref "T82")
      (value "2N2222")
      (footprint "eagle-import:TO18")
      (libsource (lib "eagle-import") (part "2N2222"))
    )
    (comp (ref "T83")
      (value "2N2222")
      (footprint "eagle-import:TO18")
      (libsource (lib "eagle-import") (part "2N2222"))
    )
    (comp (ref "T84")
      (value "2N2222")
      (footprint "eagle-import:TO18")
      (libsource (lib "eagle-import") (part "2N2222"))
    )
    (comp (ref "T85")
      (value "2N2222")
      (footprint "eagle-import:TO18")
      (libsource (lib "eagle-import") (part "2N2222"))
    )
    (comp (ref "T86")
      (value "2N2222")
      (footprint "eagle-import:TO18")
      (libsource (lib "eagle-import") (part "2N2222"))
    )
    (comp (ref "T87")
      (value "2N2222")
      (footprint "eagle-import:TO18")
      (libsource (lib "eagle-import") (part "2N2222"))
    )
    (comp (ref "T88")
      (value "2N2222")
      (footprint "eagle-import:TO18")
      (libsource (lib "eagle-import") (part "2N2222"))
    )
    (comp (ref "T89")
      (value "2N2222")
      (footprint "eagle-import:TO18")
      (libsource (lib "eagle-import") (part "2N2222"))
    )
    (comp (ref "T90")
      (value "2N2222")
      (footprint "eagle-import:TO18")
      (libsource (lib "eagle-import") (part "2N2222"))
    )
    (comp (ref "T91")
      (value "2N2222")
      (footprint "eagle-import:TO18")
      (libsource (lib "eagle-import") (part "2N2222"))
    )
    (comp (ref "T92")
      (value "2N2222")
      (footprint "eagle-import:TO18")
      (libsource (lib "eagle-import") (part "2N2222"))
    )
    (comp (ref "T93")
      (value "2N2222")
      (footprint "eagle-import:TO18")
      (libsource (lib "eagle-import") (part "2N2222"))
    )
    (comp (ref "T94")
      (value "2N2222")
      (footprint "eagle-import:TO18")
      (libsource (lib "eagle-import") (part "2N2222"))
    )
    (comp (ref "T95")
      (value "2N2222")
      (footprint "eagle-import:TO18")
      (libsource (lib "eagle-import") (part "2N2222"))
    )
    (comp (ref "T96")
      (value "2N2222")
      (footprint "eagle-import:TO18")
      (libsource (lib "eagle-import") (part "2N2222"))
    )
  )
  (nets
    (net (code "1") (name "3.3{slash}5v") (class "Default")
      (node (ref "C1") (pin "1") (pinfunction "1_1") (pintype "passive"))
      (node (ref "C10") (pin "1") (pinfunction "1_1") (pintype "passive"))
      (node (ref "C100") (pin "1") (pinfunction "1_1") (pintype "passive"))
      (node (ref "C101") (pin "1") (pinfunction "1_1") (pintype "passive"))
      (node (ref "C102") (pin "1") (pinfunction "1_1") (pintype "passive"))
      (node (ref "C103") (pin "1") (pinfunction "1_1") (pintype "passive"))
      (node (ref "C104") (pin "1") (pinfunction "1_1") (pintype "passive"))
      (node (ref "C105") (pin "1") (pinfunction "1_1") (pintype "passive"))
      (node (ref "C106") (pin "1") (pinfunction "1_1") (pintype "passive"))
      (node (ref "C107") (pin "1") (pinfunction "1_1") (pintype "passive"))
      (node (ref "C108") (pin "1") (pinfunction "1_1") (pintype "passive"))
      (node (ref "C11") (pin "1") (pinfunction "1_1") (pintype "passive"))
      (node (ref "C12") (pin "1") (pinfunction "1_1") (pintype "passive"))
      (node (ref "C13") (pin "1") (pinfunction "1_1") (pintype "passive"))
      (node (ref "C14") (pin "1") (pinfunction "1_1") (pintype "passive"))
      (node (ref "C15") (pin "1") (pinfunction "1_1") (pintype "passive"))
      (node (ref "C16") (pin "1") (pinfunction "1_1") (pintype "passive"))
      (node (ref "C17") (pin "1") (pinfunction "1_1") (pintype "passive"))
      (node (ref "C18") (pin "1") (pinfunction "1_1") (pintype "passive"))
      (node (ref "C19") (pin "1") (pinfunction "1_1") (pintype "passive"))
      (node (ref "C2") (pin "1") (pinfunction "1_1") (pintype "passive"))
      (node (ref "C20") (pin "1") (pinfunction "1_1") (pintype "passive"))
      (node (ref "C21") (pin "1") (pinfunction "1_1") (pintype "passive"))
      (node (ref "C22") (pin "1") (pinfunction "1_1") (pintype "passive"))
      (node (ref "C23") (pin "1") (pinfunction "1_1") (pintype "passive"))
      (node (ref "C24") (pin "1") (pinfunction "1_1") (pintype "passive"))
      (node (ref "C25") (pin "1") (pinfunction "1_1") (pintype "passive"))
      (node (ref "C26") (pin "1") (pinfunction "1_1") (pintype "passive"))
      (node (ref "C27") (pin "1") (pinfunction "1_1") (pintype "passive"))
      (node (ref "C28") (pin "1") (pinfunction "1_1") (pintype "passive"))
      (node (ref "C29") (pin "1") (pinfunction "1_1") (pintype "passive"))
      (node (ref "C3") (pin "1") (pinfunction "1_1") (pintype "passive"))
      (node (ref "C30") (pin "1") (pinfunction "1_1") (pintype "passive"))
      (node (ref "C31") (pin "1") (pinfunction "1_1") (pintype "passive"))
      (node (ref "C32") (pin "1") (pinfunction "1_1") (pintype "passive"))
      (node (ref "C33") (pin "1") (pinfunction "1_1") (pintype "passive"))
      (node (ref "C34") (pin "1") (pinfunction "1_1") (pintype "passive"))
      (node (ref "C35") (pin "1") (pinfunction "1_1") (pintype "passive"))
      (node (ref "C36") (pin "1") (pinfunction "1_1") (pintype "passive"))
      (node (ref "C37") (pin "1") (pinfunction "1_1") (pintype "passive"))
      (node (ref "C38") (pin "1") (pinfunction "1_1") (pintype "passive"))
      (node (ref "C39") (pin "1") (pinfunction "1_1") (pintype "passive"))
      (node (ref "C4") (pin "1") (pinfunction "1_1") (pintype "passive"))
      (node (ref "C40") (pin "1") (pinfunction "1_1") (pintype "passive"))
      (node (ref "C41") (pin "1") (pinfunction "1_1") (pintype "passive"))
      (node (ref "C42") (pin "1") (pinfunction "1_1") (pintype "passive"))
      (node (ref "C43") (pin "1") (pinfunction "1_1") (pintype "passive"))
      (node (ref "C44") (pin "1") (pinfunction "1_1") (pintype "passive"))
      (node (ref "C45") (pin "1") (pinfunction "1_1") (pintype "passive"))
      (node (ref "C46") (pin "1") (pinfunction "1_1") (pintype "passive"))
      (node (ref "C47") (pin "1") (pinfunction "1_1") (pintype "passive"))
      (node (ref "C48") (pin "1") (pinfunction "1_1") (pintype "passive"))
      (node (ref "C49") (pin "1") (pinfunction "1_1") (pintype "passive"))
      (node (ref "C5") (pin "1") (pinfunction "1_1") (pintype "passive"))
      (node (ref "C50") (pin "1") (pinfunction "1_1") (pintype "passive"))
      (node (ref "C51") (pin "1") (pinfunction "1_1") (pintype "passive"))
      (node (ref "C52") (pin "1") (pinfunction "1_1") (pintype "passive"))
      (node (ref "C53") (pin "1") (pinfunction "1_1") (pintype "passive"))
      (node (ref "C54") (pin "1") (pinfunction "1_1") (pintype "passive"))
      (node (ref "C55") (pin "1") (pinfunction "1_1") (pintype "passive"))
      (node (ref "C56") (pin "1") (pinfunction "1_1") (pintype "passive"))
      (node (ref "C57") (pin "1") (pinfunction "1_1") (pintype "passive"))
      (node (ref "C58") (pin "1") (pinfunction "1_1") (pintype "passive"))
      (node (ref "C59") (pin "1") (pinfunction "1_1") (pintype "passive"))
      (node (ref "C6") (pin "1") (pinfunction "1_1") (pintype "passive"))
      (node (ref "C60") (pin "1") (pinfunction "1_1") (pintype "passive"))
      (node (ref "C61") (pin "1") (pinfunction "1_1") (pintype "passive"))
      (node (ref "C62") (pin "1") (pinfunction "1_1") (pintype "passive"))
      (node (ref "C63") (pin "1") (pinfunction "1_1") (pintype "passive"))
      (node (ref "C64") (pin "1") (pinfunction "1_1") (pintype "passive"))
      (node (ref "C65") (pin "1") (pinfunction "1_1") (pintype "passive"))
      (node (ref "C66") (pin "1") (pinfunction "1_1") (pintype "passive"))
      (node (ref "C67") (pin "1") (pinfunction "1_1") (pintype "passive"))
      (node (ref "C68") (pin "1") (pinfunction "1_1") (pintype "passive"))
      (node (ref "C69") (pin "1") (pinfunction "1_1") (pintype "passive"))
      (node (ref "C7") (pin "1") (pinfunction "1_1") (pintype "passive"))
      (node (ref "C70") (pin "1") (pinfunction "1_1") (pintype "passive"))
      (node (ref "C71") (pin "1") (pinfunction "1_1") (pintype "passive"))
      (node (ref "C72") (pin "1") (pinfunction "1_1") (pintype "passive"))
      (node (ref "C73") (pin "1") (pinfunction "1_1") (pintype "passive"))
      (node (ref "C74") (pin "1") (pinfunction "1_1") (pintype "passive"))
      (node (ref "C75") (pin "1") (pinfunction "1_1") (pintype "passive"))
      (node (ref "C76") (pin "1") (pinfunction "1_1") (pintype "passive"))
      (node (ref "C77") (pin "1") (pinfunction "1_1") (pintype "passive"))
      (node (ref "C78") (pin "1") (pinfunction "1_1") (pintype "passive"))
      (node (ref "C79") (pin "1") (pinfunction "1_1") (pintype "passive"))
      (node (ref "C8") (pin "1") (pinfunction "1_1") (pintype "passive"))
      (node (ref "C80") (pin "1") (pinfunction "1_1") (pintype "passive"))
      (node (ref "C81") (pin "1") (pinfunction "1_1") (pintype "passive"))
      (node (ref "C82") (pin "1") (pinfunction "1_1") (pintype "passive"))
      (node (ref "C83") (pin "1") (pinfunction "1_1") (pintype "passive"))
      (node (ref "C84") (pin "1") (pinfunction "1_1") (pintype "passive"))
      (node (ref "C85") (pin "1") (pinfunction "1_1") (pintype "passive"))
      (node (ref "C86") (pin "1") (pinfunction "1_1") (pintype "passive"))
      (node (ref "C87") (pin "1") (pinfunction "1_1") (pintype "passive"))
      (node (ref "C88") (pin "1") (pinfunction "1_1") (pintype "passive"))
      (node (ref "C89") (pin "1") (pinfunction "1_1") (pintype "passive"))
      (node (ref "C9") (pin "1") (pinfunction "1_1") (pintype "passive"))
      (node (ref "C90") (pin "1") (pinfunction "1_1") (pintype "passive"))
      (node (ref "C91") (pin "1") (pinfunction "1_1") (pintype "passive"))
      (node (ref "C92") (pin "1") (pinfunction "1_1") (pintype "passive"))
      (node (ref "C93") (pin "1") (pinfunction "1_1") (pintype "passive"))
      (node (ref "C94") (pin "1") (pinfunction "1_1") (pintype "passive"))
      (node (ref "C95") (pin "1") (pinfunction "1_1") (pintype "passive"))
      (node (ref "C96") (pin "1") (pinfunction "1_1") (pintype "passive"))
      (node (ref "C97") (pin "1") (pinfunction "1_1") (pintype "passive"))
      (node (ref "C98") (pin "1") (pinfunction "1_1") (pintype "passive"))
      (node (ref "C99") (pin "1") (pinfunction "1_1") (pintype "passive"))
      (node (ref "D1") (pin "C") (pinfunction "C_C") (pintype "passive"))
      (node (ref "D10") (pin "C") (pinfunction "C_C") (pintype "passive"))
      (node (ref "D11") (pin "C") (pinfunction "C_C") (pintype "passive"))
      (node (ref "D12") (pin "C") (pinfunction "C_C") (pintype "passive"))
      (node (ref "D13") (pin "C") (pinfunction "C_C") (pintype "passive"))
      (node (ref "D14") (pin "C") (pinfunction "C_C") (pintype "passive"))
      (node (ref "D15") (pin "C") (pinfunction "C_C") (pintype "passive"))
      (node (ref "D16") (pin "C") (pinfunction "C_C") (pintype "passive"))
      (node (ref "D17") (pin "C") (pinfunction "C_C") (pintype "passive"))
      (node (ref "D18") (pin "C") (pinfunction "C_C") (pintype "passive"))
      (node (ref "D19") (pin "C") (pinfunction "C_C") (pintype "passive"))
      (node (ref "D2") (pin "C") (pinfunction "C_C") (pintype "passive"))
      (node (ref "D20") (pin "C") (pinfunction "C_C") (pintype "passive"))
      (node (ref "D21") (pin "C") (pinfunction "C_C") (pintype "passive"))
      (node (ref "D22") (pin "C") (pinfunction "C_C") (pintype "passive"))
      (node (ref "D23") (pin "C") (pinfunction "C_C") (pintype "passive"))
      (node (ref "D24") (pin "C") (pinfunction "C_C") (pintype "passive"))
      (node (ref "D25") (pin "C") (pinfunction "C_C") (pintype "passive"))
      (node (ref "D26") (pin "C") (pinfunction "C_C") (pintype "passive"))
      (node (ref "D27") (pin "C") (pinfunction "C_C") (pintype "passive"))
      (node (ref "D28") (pin "C") (pinfunction "C_C") (pintype "passive"))
      (node (ref "D29") (pin "C") (pinfunction "C_C") (pintype "passive"))
      (node (ref "D3") (pin "C") (pinfunction "C_C") (pintype "passive"))
      (node (ref "D30") (pin "C") (pinfunction "C_C") (pintype "passive"))
      (node (ref "D31") (pin "C") (pinfunction "C_C") (pintype "passive"))
      (node (ref "D32") (pin "C") (pinfunction "C_C") (pintype "passive"))
      (node (ref "D33") (pin "C") (pinfunction "C_C") (pintype "passive"))
      (node (ref "D34") (pin "C") (pinfunction "C_C") (pintype "passive"))
      (node (ref "D35") (pin "C") (pinfunction "C_C") (pintype "passive"))
      (node (ref "D36") (pin "C") (pinfunction "C_C") (pintype "passive"))
      (node (ref "D37") (pin "C") (pinfunction "C_C") (pintype "passive"))
      (node (ref "D38") (pin "C") (pinfunction "C_C") (pintype "passive"))
      (node (ref "D39") (pin "C") (pinfunction "C_C") (pintype "passive"))
      (node (ref "D4") (pin "C") (pinfunction "C_C") (pintype "passive"))
      (node (ref "D40") (pin "C") (pinfunction "C_C") (pintype "passive"))
      (node (ref "D41") (pin "C") (pinfunction "C_C") (pintype "passive"))
      (node (ref "D42") (pin "C") (pinfunction "C_C") (pintype "passive"))
      (node (ref "D43") (pin "C") (pinfunction "C_C") (pintype "passive"))
      (node (ref "D44") (pin "C") (pinfunction "C_C") (pintype "passive"))
      (node (ref "D45") (pin "C") (pinfunction "C_C") (pintype "passive"))
      (node (ref "D46") (pin "C") (pinfunction "C_C") (pintype "passive"))
      (node (ref "D47") (pin "C") (pinfunction "C_C") (pintype "passive"))
      (node (ref "D48") (pin "C") (pinfunction "C_C") (pintype "passive"))
      (node (ref "D49") (pin "C") (pinfunction "C_C") (pintype "passive"))
      (node (ref "D5") (pin "C") (pinfunction "C_C") (pintype "passive"))
      (node (ref "D50") (pin "C") (pinfunction "C_C") (pintype "passive"))
      (node (ref "D51") (pin "C") (pinfunction "C_C") (pintype "passive"))
      (node (ref "D52") (pin "C") (pinfunction "C_C") (pintype "passive"))
      (node (ref "D53") (pin "C") (pinfunction "C_C") (pintype "passive"))
      (node (ref "D54") (pin "C") (pinfunction "C_C") (pintype "passive"))
      (node (ref "D55") (pin "C") (pinfunction "C_C") (pintype "passive"))
      (node (ref "D56") (pin "C") (pinfunction "C_C") (pintype "passive"))
      (node (ref "D57") (pin "C") (pinfunction "C_C") (pintype "passive"))
      (node (ref "D58") (pin "C") (pinfunction "C_C") (pintype "passive"))
      (node (ref "D59") (pin "C") (pinfunction "C_C") (pintype "passive"))
      (node (ref "D6") (pin "C") (pinfunction "C_C") (pintype "passive"))
      (node (ref "D60") (pin "C") (pinfunction "C_C") (pintype "passive"))
      (node (ref "D61") (pin "C") (pinfunction "C_C") (pintype "passive"))
      (node (ref "D62") (pin "C") (pinfunction "C_C") (pintype "passive"))
      (node (ref "D63") (pin "C") (pinfunction "C_C") (pintype "passive"))
      (node (ref "D64") (pin "C") (pinfunction "C_C") (pintype "passive"))
      (node (ref "D65") (pin "C") (pinfunction "C_C") (pintype "passive"))
      (node (ref "D66") (pin "C") (pinfunction "C_C") (pintype "passive"))
      (node (ref "D67") (pin "C") (pinfunction "C_C") (pintype "passive"))
      (node (ref "D68") (pin "C") (pinfunction "C_C") (pintype "passive"))
      (node (ref "D69") (pin "C") (pinfunction "C_C") (pintype "passive"))
      (node (ref "D7") (pin "C") (pinfunction "C_C") (pintype "passive"))
      (node (ref "D70") (pin "C") (pinfunction "C_C") (pintype "passive"))
      (node (ref "D71") (pin "C") (pinfunction "C_C") (pintype "passive"))
      (node (ref "D72") (pin "C") (pinfunction "C_C") (pintype "passive"))
      (node (ref "D73") (pin "C") (pinfunction "C_C") (pintype "passive"))
      (node (ref "D74") (pin "C") (pinfunction "C_C") (pintype "passive"))
      (node (ref "D75") (pin "C") (pinfunction "C_C") (pintype "passive"))
      (node (ref "D76") (pin "C") (pinfunction "C_C") (pintype "passive"))
      (node (ref "D77") (pin "C") (pinfunction "C_C") (pintype "passive"))
      (node (ref "D78") (pin "C") (pinfunction "C_C") (pintype "passive"))
      (node (ref "D79") (pin "C") (pinfunction "C_C") (pintype "passive"))
      (node (ref "D8") (pin "C") (pinfunction "C_C") (pintype "passive"))
      (node (ref "D80") (pin "C") (pinfunction "C_C") (pintype "passive"))
      (node (ref "D81") (pin "C") (pinfunction "C_C") (pintype "passive"))
      (node (ref "D82") (pin "C") (pinfunction "C_C") (pintype "passive"))
      (node (ref "D83") (pin "C") (pinfunction "C_C") (pintype "passive"))
      (node (ref "D84") (pin "C") (pinfunction "C_C") (pintype "passive"))
      (node (ref "D85") (pin "C") (pinfunction "C_C") (pintype "passive"))
      (node (ref "D86") (pin "C") (pinfunction "C_C") (pintype "passive"))
      (node (ref "D87") (pin "C") (pinfunction "C_C") (pintype "passive"))
      (node (ref "D88") (pin "C") (pinfunction "C_C") (pintype "passive"))
      (node (ref "D89") (pin "C") (pinfunction "C_C") (pintype "passive"))
      (node (ref "D9") (pin "C") (pinfunction "C_C") (pintype "passive"))
      (node (ref "D90") (pin "C") (pinfunction "C_C") (pintype "passive"))
      (node (ref "D91") (pin "C") (pinfunction "C_C") (pintype "passive"))
      (node (ref "D92") (pin "C") (pinfunction "C_C") (pintype "passive"))
      (node (ref "D93") (pin "C") (pinfunction "C_C") (pintype "passive"))
      (node (ref "D94") (pin "C") (pinfunction "C_C") (pintype "passive"))
      (node (ref "D95") (pin "C") (pinfunction "C_C") (pintype "passive"))
      (node (ref "D96") (pin "C") (pinfunction "C_C") (pintype "passive"))
      (node (ref "IC1") (pin "10") (pinfunction "SCL_10") (pintype "input"))
      (node (ref "IC1") (pin "16") (pinfunction "VCC_16") (pintype "power_in"))
      (node (ref "IC10") (pin "10") (pinfunction "SCL_10") (pintype "input"))
      (node (ref "IC10") (pin "16") (pinfunction "VCC_16") (pintype "power_in"))
      (node (ref "IC11") (pin "10") (pinfunction "SCL_10") (pintype "input"))
      (node (ref "IC11") (pin "16") (pinfunction "VCC_16") (pintype "power_in"))
      (node (ref "IC12") (pin "10") (pinfunction "SCL_10") (pintype "input"))
      (node (ref "IC12") (pin "16") (pinfunction "VCC_16") (pintype "power_in"))
      (node (ref "IC2") (pin "10") (pinfunction "SCL_10") (pintype "input"))
      (node (ref "IC2") (pin "16") (pinfunction "VCC_16") (pintype "power_in"))
      (node (ref "IC3") (pin "10") (pinfunction "SCL_10") (pintype "input"))
      (node (ref "IC3") (pin "16") (pinfunction "VCC_16") (pintype "power_in"))
      (node (ref "IC4") (pin "10") (pinfunction "SCL_10") (pintype "input"))
      (node (ref "IC4") (pin "16") (pinfunction "VCC_16") (pintype "power_in"))
      (node (ref "IC5") (pin "10") (pinfunction "SCL_10") (pintype "input"))
      (node (ref "IC5") (pin "16") (pinfunction "VCC_16") (pintype "power_in"))
      (node (ref "IC6") (pin "10") (pinfunction "SCL_10") (pintype "input"))
      (node (ref "IC6") (pin "16") (pinfunction "VCC_16") (pintype "power_in"))
      (node (ref "IC7") (pin "10") (pinfunction "SCL_10") (pintype "input"))
      (node (ref "IC7") (pin "16") (pinfunction "VCC_16") (pintype "power_in"))
      (node (ref "IC8") (pin "10") (pinfunction "SCL_10") (pintype "input"))
      (node (ref "IC8") (pin "16") (pinfunction "VCC_16") (pintype "power_in"))
      (node (ref "IC9") (pin "10") (pinfunction "SCL_10") (pintype "input"))
      (node (ref "IC9") (pin "16") (pinfunction "VCC_16") (pintype "power_in"))
      (node (ref "MT1") (pin "1") (pinfunction "1_1") (pintype "passive"))
      (node (ref "MT10") (pin "1") (pinfunction "1_1") (pintype "passive"))
      (node (ref "MT11") (pin "1") (pinfunction "1_1") (pintype "passive"))
      (node (ref "MT12") (pin "1") (pinfunction "1_1") (pintype "passive"))
      (node (ref "MT13") (pin "1") (pinfunction "1_1") (pintype "passive"))
      (node (ref "MT14") (pin "1") (pinfunction "1_1") (pintype "passive"))
      (node (ref "MT15") (pin "1") (pinfunction "1_1") (pintype "passive"))
      (node (ref "MT16") (pin "1") (pinfunction "1_1") (pintype "passive"))
      (node (ref "MT17") (pin "1") (pinfunction "1_1") (pintype "passive"))
      (node (ref "MT18") (pin "1") (pinfunction "1_1") (pintype "passive"))
      (node (ref "MT19") (pin "1") (pinfunction "1_1") (pintype "passive"))
      (node (ref "MT2") (pin "1") (pinfunction "1_1") (pintype "passive"))
      (node (ref "MT20") (pin "1") (pinfunction "1_1") (pintype "passive"))
      (node (ref "MT21") (pin "1") (pinfunction "1_1") (pintype "passive"))
      (node (ref "MT22") (pin "1") (pinfunction "1_1") (pintype "passive"))
      (node (ref "MT23") (pin "1") (pinfunction "1_1") (pintype "passive"))
      (node (ref "MT24") (pin "1") (pinfunction "1_1") (pintype "passive"))
      (node (ref "MT25") (pin "1") (pinfunction "1_1") (pintype "passive"))
      (node (ref "MT26") (pin "1") (pinfunction "1_1") (pintype "passive"))
      (node (ref "MT27") (pin "1") (pinfunction "1_1") (pintype "passive"))
      (node (ref "MT28") (pin "1") (pinfunction "1_1") (pintype "passive"))
      (node (ref "MT29") (pin "1") (pinfunction "1_1") (pintype "passive"))
      (node (ref "MT3") (pin "1") (pinfunction "1_1") (pintype "passive"))
      (node (ref "MT30") (pin "1") (pinfunction "1_1") (pintype "passive"))
      (node (ref "MT31") (pin "1") (pinfunction "1_1") (pintype "passive"))
      (node (ref "MT32") (pin "1") (pinfunction "1_1") (pintype "passive"))
      (node (ref "MT33") (pin "1") (pinfunction "1_1") (pintype "passive"))
      (node (ref "MT34") (pin "1") (pinfunction "1_1") (pintype "passive"))
      (node (ref "MT35") (pin "1") (pinfunction "1_1") (pintype "passive"))
      (node (ref "MT36") (pin "1") (pinfunction "1_1") (pintype "passive"))
      (node (ref "MT37") (pin "1") (pinfunction "1_1") (pintype "passive"))
      (node (ref "MT38") (pin "1") (pinfunction "1_1") (pintype "passive"))
      (node (ref "MT39") (pin "1") (pinfunction "1_1") (pintype "passive"))
      (node (ref "MT4") (pin "1") (pinfunction "1_1") (pintype "passive"))
      (node (ref "MT40") (pin "1") (pinfunction "1_1") (pintype "passive"))
      (node (ref "MT41") (pin "1") (pinfunction "1_1") (pintype "passive"))
      (node (ref "MT42") (pin "1") (pinfunction "1_1") (pintype "passive"))
      (node (ref "MT43") (pin "1") (pinfunction "1_1") (pintype "passive"))
      (node (ref "MT44") (pin "1") (pinfunction "1_1") (pintype "passive"))
      (node (ref "MT45") (pin "1") (pinfunction "1_1") (pintype "passive"))
      (node (ref "MT46") (pin "1") (pinfunction "1_1") (pintype "passive"))
      (node (ref "MT47") (pin "1") (pinfunction "1_1") (pintype "passive"))
      (node (ref "MT48") (pin "1") (pinfunction "1_1") (pintype "passive"))
      (node (ref "MT49") (pin "1") (pinfunction "1_1") (pintype "passive"))
      (node (ref "MT5") (pin "1") (pinfunction "1_1") (pintype "passive"))
      (node (ref "MT50") (pin "1") (pinfunction "1_1") (pintype "passive"))
      (node (ref "MT51") (pin "1") (pinfunction "1_1") (pintype "passive"))
      (node (ref "MT52") (pin "1") (pinfunction "1_1") (pintype "passive"))
      (node (ref "MT53") (pin "1") (pinfunction "1_1") (pintype "passive"))
      (node (ref "MT54") (pin "1") (pinfunction "1_1") (pintype "passive"))
      (node (ref "MT55") (pin "1") (pinfunction "1_1") (pintype "passive"))
      (node (ref "MT56") (pin "1") (pinfunction "1_1") (pintype "passive"))
      (node (ref "MT57") (pin "1") (pinfunction "1_1") (pintype "passive"))
      (node (ref "MT58") (pin "1") (pinfunction "1_1") (pintype "passive"))
      (node (ref "MT59") (pin "1") (pinfunction "1_1") (pintype "passive"))
      (node (ref "MT6") (pin "1") (pinfunction "1_1") (pintype "passive"))
      (node (ref "MT60") (pin "1") (pinfunction "1_1") (pintype "passive"))
      (node (ref "MT61") (pin "1") (pinfunction "1_1") (pintype "passive"))
      (node (ref "MT62") (pin "1") (pinfunction "1_1") (pintype "passive"))
      (node (ref "MT63") (pin "1") (pinfunction "1_1") (pintype "passive"))
      (node (ref "MT64") (pin "1") (pinfunction "1_1") (pintype "passive"))
      (node (ref "MT65") (pin "1") (pinfunction "1_1") (pintype "passive"))
      (node (ref "MT66") (pin "1") (pinfunction "1_1") (pintype "passive"))
      (node (ref "MT67") (pin "1") (pinfunction "1_1") (pintype "passive"))
      (node (ref "MT68") (pin "1") (pinfunction "1_1") (pintype "passive"))
      (node (ref "MT69") (pin "1") (pinfunction "1_1") (pintype "passive"))
      (node (ref "MT7") (pin "1") (pinfunction "1_1") (pintype "passive"))
      (node (ref "MT70") (pin "1") (pinfunction "1_1") (pintype "passive"))
      (node (ref "MT71") (pin "1") (pinfunction "1_1") (pintype "passive"))
      (node (ref "MT72") (pin "1") (pinfunction "1_1") (pintype "passive"))
      (node (ref "MT73") (pin "1") (pinfunction "1_1") (pintype "passive"))
      (node (ref "MT74") (pin "1") (pinfunction "1_1") (pintype "passive"))
      (node (ref "MT75") (pin "1") (pinfunction "1_1") (pintype "passive"))
      (node (ref "MT76") (pin "1") (pinfunction "1_1") (pintype "passive"))
      (node (ref "MT77") (pin "1") (pinfunction "1_1") (pintype "passive"))
      (node (ref "MT78") (pin "1") (pinfunction "1_1") (pintype "passive"))
      (node (ref "MT79") (pin "1") (pinfunction "1_1") (pintype "passive"))
      (node (ref "MT8") (pin "1") (pinfunction "1_1") (pintype "passive"))
      (node (ref "MT80") (pin "1") (pinfunction "1_1") (pintype "passive"))
      (node (ref "MT81") (pin "1") (pinfunction "1_1") (pintype "passive"))
      (node (ref "MT82") (pin "1") (pinfunction "1_1") (pintype "passive"))
      (node (ref "MT83") (pin "1") (pinfunction "1_1") (pintype "passive"))
      (node (ref "MT84") (pin "1") (pinfunction "1_1") (pintype "passive"))
      (node (ref "MT85") (pin "1") (pinfunction "1_1") (pintype "passive"))
      (node (ref "MT86") (pin "1") (pinfunction "1_1") (pintype "passive"))
      (node (ref "MT87") (pin "1") (pinfunction "1_1") (pintype "passive"))
      (node (ref "MT88") (pin "1") (pinfunction "1_1") (pintype "passive"))
      (node (ref "MT89") (pin "1") (pinfunction "1_1") (pintype "passive"))
      (node (ref "MT9") (pin "1") (pinfunction "1_1") (pintype "passive"))
      (node (ref "MT90") (pin "1") (pinfunction "1_1") (pintype "passive"))
      (node (ref "MT91") (pin "1") (pinfunction "1_1") (pintype "passive"))
      (node (ref "MT92") (pin "1") (pinfunction "1_1") (pintype "passive"))
      (node (ref "MT93") (pin "1") (pinfunction "1_1") (pintype "passive"))
      (node (ref "MT94") (pin "1") (pinfunction "1_1") (pintype "passive"))
      (node (ref "MT95") (pin "1") (pinfunction "1_1") (pintype "passive"))
      (node (ref "MT96") (pin "1") (pinfunction "1_1") (pintype "passive"))
    )
    (net (code "2") (name "GND") (class "Default")
      (node (ref "C100") (pin "2") (pinfunction "2_2") (pintype "passive"))
      (node (ref "C101") (pin "2") (pinfunction "2_2") (pintype "passive"))
      (node (ref "C102") (pin "2") (pinfunction "2_2") (pintype "passive"))
      (node (ref "C103") (pin "2") (pinfunction "2_2") (pintype "passive"))
      (node (ref "C104") (pin "2") (pinfunction "2_2") (pintype "passive"))
      (node (ref "C105") (pin "2") (pinfunction "2_2") (pintype "passive"))
      (node (ref "C106") (pin "2") (pinfunction "2_2") (pintype "passive"))
      (node (ref "C107") (pin "2") (pinfunction "2_2") (pintype "passive"))
      (node (ref "C108") (pin "2") (pinfunction "2_2") (pintype "passive"))
      (node (ref "C97") (pin "2") (pinfunction "2_2") (pintype "passive"))
      (node (ref "C98") (pin "2") (pinfunction "2_2") (pintype "passive"))
      (node (ref "C99") (pin "2") (pinfunction "2_2") (pintype "passive"))
      (node (ref "IC1") (pin "13") (pinfunction "G_13") (pintype "input"))
      (node (ref "IC1") (pin "8") (pinfunction "GND_8") (pintype "power_in"))
      (node (ref "IC10") (pin "13") (pinfunction "G_13") (pintype "input"))
      (node (ref "IC10") (pin "8") (pinfunction "GND_8") (pintype "power_in"))
      (node (ref "IC11") (pin "13") (pinfunction "G_13") (pintype "input"))
      (node (ref "IC11") (pin "8") (pinfunction "GND_8") (pintype "power_in"))
      (node (ref "IC12") (pin "13") (pinfunction "G_13") (pintype "input"))
      (node (ref "IC12") (pin "8") (pinfunction "GND_8") (pintype "power_in"))
      (node (ref "IC2") (pin "13") (pinfunction "G_13") (pintype "input"))
      (node (ref "IC2") (pin "8") (pinfunction "GND_8") (pintype "power_in"))
      (node (ref "IC3") (pin "13") (pinfunction "G_13") (pintype "input"))
      (node (ref "IC3") (pin "8") (pinfunction "GND_8") (pintype "power_in"))
      (node (ref "IC4") (pin "13") (pinfunction "G_13") (pintype "input"))
      (node (ref "IC4") (pin "8") (pinfunction "GND_8") (pintype "power_in"))
      (node (ref "IC5") (pin "13") (pinfunction "G_13") (pintype "input"))
      (node (ref "IC5") (pin "8") (pinfunction "GND_8") (pintype "power_in"))
      (node (ref "IC6") (pin "13") (pinfunction "G_13") (pintype "input"))
      (node (ref "IC6") (pin "8") (pinfunction "GND_8") (pintype "power_in"))
      (node (ref "IC7") (pin "13") (pinfunction "G_13") (pintype "input"))
      (node (ref "IC7") (pin "8") (pinfunction "GND_8") (pintype "power_in"))
      (node (ref "IC8") (pin "13") (pinfunction "G_13") (pintype "input"))
      (node (ref "IC8") (pin "8") (pinfunction "GND_8") (pintype "power_in"))
      (node (ref "IC9") (pin "13") (pinfunction "G_13") (pintype "input"))
      (node (ref "IC9") (pin "8") (pinfunction "GND_8") (pintype "power_in"))
      (node (ref "T1") (pin "1") (pinfunction "E_1") (pintype "passive"))
      (node (ref "T10") (pin "1") (pinfunction "E_1") (pintype "passive"))
      (node (ref "T11") (pin "1") (pinfunction "E_1") (pintype "passive"))
      (node (ref "T12") (pin "1") (pinfunction "E_1") (pintype "passive"))
      (node (ref "T13") (pin "1") (pinfunction "E_1") (pintype "passive"))
      (node (ref "T14") (pin "1") (pinfunction "E_1") (pintype "passive"))
      (node (ref "T15") (pin "1") (pinfunction "E_1") (pintype "passive"))
      (node (ref "T16") (pin "1") (pinfunction "E_1") (pintype "passive"))
      (node (ref "T17") (pin "1") (pinfunction "E_1") (pintype "passive"))
      (node (ref "T18") (pin "1") (pinfunction "E_1") (pintype "passive"))
      (node (ref "T19") (pin "1") (pinfunction "E_1") (pintype "passive"))
      (node (ref "T2") (pin "1") (pinfunction "E_1") (pintype "passive"))
      (node (ref "T20") (pin "1") (pinfunction "E_1") (pintype "passive"))
      (node (ref "T21") (pin "1") (pinfunction "E_1") (pintype "passive"))
      (node (ref "T22") (pin "1") (pinfunction "E_1") (pintype "passive"))
      (node (ref "T23") (pin "1") (pinfunction "E_1") (pintype "passive"))
      (node (ref "T24") (pin "1") (pinfunction "E_1") (pintype "passive"))
      (node (ref "T25") (pin "1") (pinfunction "E_1") (pintype "passive"))
      (node (ref "T26") (pin "1") (pinfunction "E_1") (pintype "passive"))
      (node (ref "T27") (pin "1") (pinfunction "E_1") (pintype "passive"))
      (node (ref "T28") (pin "1") (pinfunction "E_1") (pintype "passive"))
      (node (ref "T29") (pin "1") (pinfunction "E_1") (pintype "passive"))
      (node (ref "T3") (pin "1") (pinfunction "E_1") (pintype "passive"))
      (node (ref "T30") (pin "1") (pinfunction "E_1") (pintype "passive"))
      (node (ref "T31") (pin "1") (pinfunction "E_1") (pintype "passive"))
      (node (ref "T32") (pin "1") (pinfunction "E_1") (pintype "passive"))
      (node (ref "T33") (pin "1") (pinfunction "E_1") (pintype "passive"))
      (node (ref "T34") (pin "1") (pinfunction "E_1") (pintype "passive"))
      (node (ref "T35") (pin "1") (pinfunction "E_1") (pintype "passive"))
      (node (ref "T36") (pin "1") (pinfunction "E_1") (pintype "passive"))
      (node (ref "T37") (pin "1") (pinfunction "E_1") (pintype "passive"))
      (node (ref "T38") (pin "1") (pinfunction "E_1") (pintype "passive"))
      (node (ref "T39") (pin "1") (pinfunction "E_1") (pintype "passive"))
      (node (ref "T4") (pin "1") (pinfunction "E_1") (pintype "passive"))
      (node (ref "T40") (pin "1") (pinfunction "E_1") (pintype "passive"))
      (node (ref "T41") (pin "1") (pinfunction "E_1") (pintype "passive"))
      (node (ref "T42") (pin "1") (pinfunction "E_1") (pintype "passive"))
      (node (ref "T43") (pin "1") (pinfunction "E_1") (pintype "passive"))
      (node (ref "T44") (pin "1") (pinfunction "E_1") (pintype "passive"))
      (node (ref "T45") (pin "1") (pinfunction "E_1") (pintype "passive"))
      (node (ref "T46") (pin "1") (pinfunction "E_1") (pintype "passive"))
      (node (ref "T47") (pin "1") (pinfunction "E_1") (pintype "passive"))
      (node (ref "T48") (pin "1") (pinfunction "E_1") (pintype "passive"))
      (node (ref "T49") (pin "1") (pinfunction "E_1") (pintype "passive"))
      (node (ref "T5") (pin "1") (pinfunction "E_1") (pintype "passive"))
      (node (ref "T50") (pin "1") (pinfunction "E_1") (pintype "passive"))
      (node (ref "T51") (pin "1") (pinfunction "E_1") (pintype "passive"))
      (node (ref "T52") (pin "1") (pinfunction "E_1") (pintype "passive"))
      (node (ref "T53") (pin "1") (pinfunction "E_1") (pintype "passive"))
      (node (ref "T54") (pin "1") (pinfunction "E_1") (pintype "passive"))
      (node (ref "T55") (pin "1") (pinfunction "E_1") (pintype "passive"))
      (node (ref "T56") (pin "1") (pinfunction "E_1") (pintype "passive"))
      (node (ref "T57") (pin "1") (pinfunction "E_1") (pintype "passive"))
      (node (ref "T58") (pin "1") (pinfunction "E_1") (pintype "passive"))
      (node (ref "T59") (pin "1") (pinfunction "E_1") (pintype "passive"))
      (node (ref "T6") (pin "1") (pinfunction "E_1") (pintype "passive"))
      (node (ref "T60") (pin "1") (pinfunction "E_1") (pintype "passive"))
      (node (ref "T61") (pin "1") (pinfunction "E_1") (pintype "passive"))
      (node (ref "T62") (pin "1") (pinfunction "E_1") (pintype "passive"))
      (node (ref "T63") (pin "1") (pinfunction "E_1") (pintype "passive"))
      (node (ref "T64") (pin "1") (pinfunction "E_1") (pintype "passive"))
      (node (ref "T65") (pin "1") (pinfunction "E_1") (pintype "passive"))
      (node (ref "T66") (pin "1") (pinfunction "E_1") (pintype "passive"))
      (node (ref "T67") (pin "1") (pinfunction "E_1") (pintype "passive"))
      (node (ref "T68") (pin "1") (pinfunction "E_1") (pintype "passive"))
      (node (ref "T69") (pin "1") (pinfunction "E_1") (pintype "passive"))
      (node (ref "T7") (pin "1") (pinfunction "E_1") (pintype "passive"))
      (node (ref "T70") (pin "1") (pinfunction "E_1") (pintype "passive"))
      (node (ref "T71") (pin "1") (pinfunction "E_1") (pintype "passive"))
      (node (ref "T72") (pin "1") (pinfunction "E_1") (pintype "passive"))
      (node (ref "T73") (pin "1") (pinfunction "E_1") (pintype "passive"))
      (node (ref "T74") (pin "1") (pinfunction "E_1") (pintype "passive"))
      (node (ref "T75") (pin "1") (pinfunction "E_1") (pintype "passive"))
      (node (ref "T76") (pin "1") (pinfunction "E_1") (pintype "passive"))
      (node (ref "T77") (pin "1") (pinfunction "E_1") (pintype "passive"))
      (node (ref "T78") (pin "1") (pinfunction "E_1") (pintype "passive"))
      (node (ref "T79") (pin "1") (pinfunction "E_1") (pintype "passive"))
      (node (ref "T8") (pin "1") (pinfunction "E_1") (pintype "passive"))
      (node (ref "T80") (pin "1") (pinfunction "E_1") (pintype "passive"))
      (node (ref "T81") (pin "1") (pinfunction "E_1") (pintype "passive"))
      (node (ref "T82") (pin "1") (pinfunction "E_1") (pintype "passive"))
      (node (ref "T83") (pin "1") (pinfunction "E_1") (pintype "passive"))
      (node (ref "T84") (pin "1") (pinfunction "E_1") (pintype "passive"))
      (node (ref "T85") (pin "1") (pinfunction "E_1") (pintype "passive"))
      (node (ref "T86") (pin "1") (pinfunction "E_1") (pintype "passive"))
      (node (ref "T87") (pin "1") (pinfunction "E_1") (pintype "passive"))
      (node (ref "T88") (pin "1") (pinfunction "E_1") (pintype "passive"))
      (node (ref "T89") (pin "1") (pinfunction "E_1") (pintype "passive"))
      (node (ref "T9") (pin "1") (pinfunction "E_1") (pintype "passive"))
      (node (ref "T90") (pin "1") (pinfunction "E_1") (pintype "passive"))
      (node (ref "T91") (pin "1") (pinfunction "E_1") (pintype "passive"))
      (node (ref "T92") (pin "1") (pinfunction "E_1") (pintype "passive"))
      (node (ref "T93") (pin "1") (pinfunction "E_1") (pintype "passive"))
      (node (ref "T94") (pin "1") (pinfunction "E_1") (pintype "passive"))
      (node (ref "T95") (pin "1") (pinfunction "E_1") (pintype "passive"))
      (node (ref "T96") (pin "1") (pinfunction "E_1") (pintype "passive"))
    )
    (net (code "3") (name "Net-(IC1A-QA)") (class "Default")
      (node (ref "IC1") (pin "15") (pinfunction "QA_15") (pintype "tri_state"))
      (node (ref "R1") (pin "1") (pinfunction "1_1") (pintype "passive"))
    )
    (net (code "4") (name "Net-(IC1A-QB)") (class "Default")
      (node (ref "IC1") (pin "1") (pinfunction "QB_1") (pintype "tri_state"))
      (node (ref "R5") (pin "1") (pinfunction "1_1") (pintype "passive"))
    )
    (net (code "5") (name "Net-(IC1A-QC)") (class "Default")
      (node (ref "IC1") (pin "2") (pinfunction "QC_2") (pintype "tri_state"))
      (node (ref "R2") (pin "1") (pinfunction "1_1") (pintype "passive"))
    )
    (net (code "6") (name "Net-(IC1A-QD)") (class "Default")
      (node (ref "IC1") (pin "3") (pinfunction "QD_3") (pintype "tri_state"))
      (node (ref "R6") (pin "1") (pinfunction "1_1") (pintype "passive"))
    )
    (net (code "7") (name "Net-(IC1A-QE)") (class "Default")
      (node (ref "IC1") (pin "4") (pinfunction "QE_4") (pintype "tri_state"))
      (node (ref "R3") (pin "1") (pinfunction "1_1") (pintype "passive"))
    )
    (net (code "8") (name "Net-(IC1A-QF)") (class "Default")
      (node (ref "IC1") (pin "5") (pinfunction "QF_5") (pintype "tri_state"))
      (node (ref "R7") (pin "1") (pinfunction "1_1") (pintype "passive"))
    )
    (net (code "9") (name "Net-(IC1A-QG)") (class "Default")
      (node (ref "IC1") (pin "6") (pinfunction "QG_6") (pintype "tri_state"))
      (node (ref "R4") (pin "1") (pinfunction "1_1") (pintype "passive"))
    )
    (net (code "10") (name "Net-(IC1A-QH)") (class "Default")
      (node (ref "IC1") (pin "7") (pinfunction "QH_7") (pintype "tri_state"))
      (node (ref "R8") (pin "1") (pinfunction "1_1") (pintype "passive"))
    )
    (net (code "11") (name "Net-(IC1A-QH*)") (class "Default")
      (node (ref "IC1") (pin "9") (pinfunction "QH*_9") (pintype "tri_state"))
      (node (ref "IC2") (pin "14") (pinfunction "SER_14") (pintype "input"))
    )
    (net (code "12") (name "Net-(IC1A-SER)") (class "Default")
      (node (ref "IC1") (pin "14") (pinfunction "SER_14") (pintype "input"))
      (node (ref "JP1") (pin "3") (pinfunction "3_3") (pintype "passive"))
    )
    (net (code "13") (name "Net-(IC2A-QA)") (class "Default")
      (node (ref "IC2") (pin "15") (pinfunction "QA_15") (pintype "tri_state"))
      (node (ref "R9") (pin "1") (pinfunction "1_1") (pintype "passive"))
    )
    (net (code "14") (name "Net-(IC2A-QB)") (class "Default")
      (node (ref "IC2") (pin "1") (pinfunction "QB_1") (pintype "tri_state"))
      (node (ref "R13") (pin "1") (pinfunction "1_1") (pintype "passive"))
    )
    (net (code "15") (name "Net-(IC2A-QC)") (class "Default")
      (node (ref "IC2") (pin "2") (pinfunction "QC_2") (pintype "tri_state"))
      (node (ref "R10") (pin "1") (pinfunction "1_1") (pintype "passive"))
    )
    (net (code "16") (name "Net-(IC2A-QD)") (class "Default")
      (node (ref "IC2") (pin "3") (pinfunction "QD_3") (pintype "tri_state"))
      (node (ref "R14") (pin "1") (pinfunction "1_1") (pintype "passive"))
    )
    (net (code "17") (name "Net-(IC2A-QE)") (class "Default")
      (node (ref "IC2") (pin "4") (pinfunction "QE_4") (pintype "tri_state"))
      (node (ref "R11") (pin "1") (pinfunction "1_1") (pintype "passive"))
    )
    (net (code "18") (name "Net-(IC2A-QF)") (class "Default")
      (node (ref "IC2") (pin "5") (pinfunction "QF_5") (pintype "tri_state"))
      (node (ref "R15") (pin "1") (pinfunction "1_1") (pintype "passive"))
    )
    (net (code "19") (name "Net-(IC2A-QG)") (class "Default")
      (node (ref "IC2") (pin "6") (pinfunction "QG_6") (pintype "tri_state"))
      (node (ref "R12") (pin "1") (pinfunction "1_1") (pintype "passive"))
    )
    (net (code "20") (name "Net-(IC2A-QH)") (class "Default")
      (node (ref "IC2") (pin "7") (pinfunction "QH_7") (pintype "tri_state"))
      (node (ref "R16") (pin "1") (pinfunction "1_1") (pintype "passive"))
    )
    (net (code "21") (name "Net-(IC2A-QH*)") (class "Default")
      (node (ref "IC2") (pin "9") (pinfunction "QH*_9") (pintype "tri_state"))
      (node (ref "IC3") (pin "14") (pinfunction "SER_14") (pintype "input"))
    )
    (net (code "22") (name "Net-(IC3A-QA)") (class "Default")
      (node (ref "IC3") (pin "15") (pinfunction "QA_15") (pintype "tri_state"))
      (node (ref "R17") (pin "1") (pinfunction "1_1") (pintype "passive"))
    )
    (net (code "23") (name "Net-(IC3A-QB)") (class "Default")
      (node (ref "IC3") (pin "1") (pinfunction "QB_1") (pintype "tri_state"))
      (node (ref "R21") (pin "1") (pinfunction "1_1") (pintype "passive"))
    )
    (net (code "24") (name "Net-(IC3A-QC)") (class "Default")
      (node (ref "IC3") (pin "2") (pinfunction "QC_2") (pintype "tri_state"))
      (node (ref "R18") (pin "1") (pinfunction "1_1") (pintype "passive"))
    )
    (net (code "25") (name "Net-(IC3A-QD)") (class "Default")
      (node (ref "IC3") (pin "3") (pinfunction "QD_3") (pintype "tri_state"))
      (node (ref "R22") (pin "1") (pinfunction "1_1") (pintype "passive"))
    )
    (net (code "26") (name "Net-(IC3A-QE)") (class "Default")
      (node (ref "IC3") (pin "4") (pinfunction "QE_4") (pintype "tri_state"))
      (node (ref "R19") (pin "1") (pinfunction "1_1") (pintype "passive"))
    )
    (net (code "27") (name "Net-(IC3A-QF)") (class "Default")
      (node (ref "IC3") (pin "5") (pinfunction "QF_5") (pintype "tri_state"))
      (node (ref "R23") (pin "1") (pinfunction "1_1") (pintype "passive"))
    )
    (net (code "28") (name "Net-(IC3A-QG)") (class "Default")
      (node (ref "IC3") (pin "6") (pinfunction "QG_6") (pintype "tri_state"))
      (node (ref "R20") (pin "1") (pinfunction "1_1") (pintype "passive"))
    )
    (net (code "29") (name "Net-(IC3A-QH)") (class "Default")
      (node (ref "IC3") (pin "7") (pinfunction "QH_7") (pintype "tri_state"))
      (node (ref "R24") (pin "1") (pinfunction "1_1") (pintype "passive"))
    )
    (net (code "30") (name "Net-(IC3A-QH*)") (class "Default")
      (node (ref "IC3") (pin "9") (pinfunction "QH*_9") (pintype "tri_state"))
      (node (ref "IC4") (pin "14") (pinfunction "SER_14") (pintype "input"))
    )
    (net (code "31") (name "Net-(IC4A-QA)") (class "Default")
      (node (ref "IC4") (pin "15") (pinfunction "QA_15") (pintype "tri_state"))
      (node (ref "R25") (pin "1") (pinfunction "1_1") (pintype "passive"))
    )
    (net (code "32") (name "Net-(IC4A-QB)") (class "Default")
      (node (ref "IC4") (pin "1") (pinfunction "QB_1") (pintype "tri_state"))
      (node (ref "R29") (pin "1") (pinfunction "1_1") (pintype "passive"))
    )
    (net (code "33") (name "Net-(IC4A-QC)") (class "Default")
      (node (ref "IC4") (pin "2") (pinfunction "QC_2") (pintype "tri_state"))
      (node (ref "R26") (pin "1") (pinfunction "1_1") (pintype "passive"))
    )
    (net (code "34") (name "Net-(IC4A-QD)") (class "Default")
      (node (ref "IC4") (pin "3") (pinfunction "QD_3") (pintype "tri_state"))
      (node (ref "R30") (pin "1") (pinfunction "1_1") (pintype "passive"))
    )
    (net (code "35") (name "Net-(IC4A-QE)") (class "Default")
      (node (ref "IC4") (pin "4") (pinfunction "QE_4") (pintype "tri_state"))
      (node (ref "R27") (pin "1") (pinfunction "1_1") (pintype "passive"))
    )
    (net (code "36") (name "Net-(IC4A-QF)") (class "Default")
      (node (ref "IC4") (pin "5") (pinfunction "QF_5") (pintype "tri_state"))
      (node (ref "R31") (pin "1") (pinfunction "1_1") (pintype "passive"))
    )
    (net (code "37") (name "Net-(IC4A-QG)") (class "Default")
      (node (ref "IC4") (pin "6") (pinfunction "QG_6") (pintype "tri_state"))
      (node (ref "R28") (pin "1") (pinfunction "1_1") (pintype "passive"))
    )
    (net (code "38") (name "Net-(IC4A-QH)") (class "Default")
      (node (ref "IC4") (pin "7") (pinfunction "QH_7") (pintype "tri_state"))
      (node (ref "R32") (pin "1") (pinfunction "1_1") (pintype "passive"))
    )
    (net (code "39") (name "Net-(IC4A-QH*)") (class "Default")
      (node (ref "IC4") (pin "9") (pinfunction "QH*_9") (pintype "tri_state"))
      (node (ref "IC5") (pin "14") (pinfunction "SER_14") (pintype "input"))
    )
    (net (code "40") (name "Net-(IC5A-QA)") (class "Default")
      (node (ref "IC5") (pin "15") (pinfunction "QA_15") (pintype "tri_state"))
      (node (ref "R33") (pin "1") (pinfunction "1_1") (pintype "passive"))
    )
    (net (code "41") (name "Net-(IC5A-QB)") (class "Default")
      (node (ref "IC5") (pin "1") (pinfunction "QB_1") (pintype "tri_state"))
      (node (ref "R37") (pin "1") (pinfunction "1_1") (pintype "passive"))
    )
    (net (code "42") (name "Net-(IC5A-QC)") (class "Default")
      (node (ref "IC5") (pin "2") (pinfunction "QC_2") (pintype "tri_state"))
      (node (ref "R34") (pin "1") (pinfunction "1_1") (pintype "passive"))
    )
    (net (code "43") (name "Net-(IC5A-QD)") (class "Default")
      (node (ref "IC5") (pin "3") (pinfunction "QD_3") (pintype "tri_state"))
      (node (ref "R38") (pin "1") (pinfunction "1_1") (pintype "passive"))
    )
    (net (code "44") (name "Net-(IC5A-QE)") (class "Default")
      (node (ref "IC5") (pin "4") (pinfunction "QE_4") (pintype "tri_state"))
      (node (ref "R35") (pin "1") (pinfunction "1_1") (pintype "passive"))
    )
    (net (code "45") (name "Net-(IC5A-QF)") (class "Default")
      (node (ref "IC5") (pin "5") (pinfunction "QF_5") (pintype "tri_state"))
      (node (ref "R39") (pin "1") (pinfunction "1_1") (pintype "passive"))
    )
    (net (code "46") (name "Net-(IC5A-QG)") (class "Default")
      (node (ref "IC5") (pin "6") (pinfunction "QG_6") (pintype "tri_state"))
      (node (ref "R36") (pin "1") (pinfunction "1_1") (pintype "passive"))
    )
    (net (code "47") (name "Net-(IC5A-QH)") (class "Default")
      (node (ref "IC5") (pin "7") (pinfunction "QH_7") (pintype "tri_state"))
      (node (ref "R40") (pin "1") (pinfunction "1_1") (pintype "passive"))
    )
    (net (code "48") (name "Net-(IC5A-QH*)") (class "Default")
      (node (ref "IC5") (pin "9") (pinfunction "QH*_9") (pintype "tri_state"))
      (node (ref "IC6") (pin "14") (pinfunction "SER_14") (pintype "input"))
    )
    (net (code "49") (name "Net-(IC6A-QA)") (class "Default")
      (node (ref "IC6") (pin "15") (pinfunction "QA_15") (pintype "tri_state"))
      (node (ref "R41") (pin "1") (pinfunction "1_1") (pintype "passive"))
    )
    (net (code "50") (name "Net-(IC6A-QB)") (class "Default")
      (node (ref "IC6") (pin "1") (pinfunction "QB_1") (pintype "tri_state"))
      (node (ref "R45") (pin "1") (pinfunction "1_1") (pintype "passive"))
    )
    (net (code "51") (name "Net-(IC6A-QC)") (class "Default")
      (node (ref "IC6") (pin "2") (pinfunction "QC_2") (pintype "tri_state"))
      (node (ref "R42") (pin "1") (pinfunction "1_1") (pintype "passive"))
    )
    (net (code "52") (name "Net-(IC6A-QD)") (class "Default")
      (node (ref "IC6") (pin "3") (pinfunction "QD_3") (pintype "tri_state"))
      (node (ref "R46") (pin "1") (pinfunction "1_1") (pintype "passive"))
    )
    (net (code "53") (name "Net-(IC6A-QE)") (class "Default")
      (node (ref "IC6") (pin "4") (pinfunction "QE_4") (pintype "tri_state"))
      (node (ref "R43") (pin "1") (pinfunction "1_1") (pintype "passive"))
    )
    (net (code "54") (name "Net-(IC6A-QF)") (class "Default")
      (node (ref "IC6") (pin "5") (pinfunction "QF_5") (pintype "tri_state"))
      (node (ref "R47") (pin "1") (pinfunction "1_1") (pintype "passive"))
    )
    (net (code "55") (name "Net-(IC6A-QG)") (class "Default")
      (node (ref "IC6") (pin "6") (pinfunction "QG_6") (pintype "tri_state"))
      (node (ref "R44") (pin "1") (pinfunction "1_1") (pintype "passive"))
    )
    (net (code "56") (name "Net-(IC6A-QH)") (class "Default")
      (node (ref "IC6") (pin "7") (pinfunction "QH_7") (pintype "tri_state"))
      (node (ref "R48") (pin "1") (pinfunction "1_1") (pintype "passive"))
    )
    (net (code "57") (name "Net-(IC6A-QH*)") (class "Default")
      (node (ref "IC6") (pin "9") (pinfunction "QH*_9") (pintype "tri_state"))
      (node (ref "IC7") (pin "14") (pinfunction "SER_14") (pintype "input"))
    )
    (net (code "58") (name "Net-(IC7A-QA)") (class "Default")
      (node (ref "IC7") (pin "15") (pinfunction "QA_15") (pintype "tri_state"))
      (node (ref "R49") (pin "1") (pinfunction "1_1") (pintype "passive"))
    )
    (net (code "59") (name "Net-(IC7A-QB)") (class "Default")
      (node (ref "IC7") (pin "1") (pinfunction "QB_1") (pintype "tri_state"))
      (node (ref "R53") (pin "1") (pinfunction "1_1") (pintype "passive"))
    )
    (net (code "60") (name "Net-(IC7A-QC)") (class "Default")
      (node (ref "IC7") (pin "2") (pinfunction "QC_2") (pintype "tri_state"))
      (node (ref "R50") (pin "1") (pinfunction "1_1") (pintype "passive"))
    )
    (net (code "61") (name "Net-(IC7A-QD)") (class "Default")
      (node (ref "IC7") (pin "3") (pinfunction "QD_3") (pintype "tri_state"))
      (node (ref "R54") (pin "1") (pinfunction "1_1") (pintype "passive"))
    )
    (net (code "62") (name "Net-(IC7A-QE)") (class "Default")
      (node (ref "IC7") (pin "4") (pinfunction "QE_4") (pintype "tri_state"))
      (node (ref "R51") (pin "1") (pinfunction "1_1") (pintype "passive"))
    )
    (net (code "63") (name "Net-(IC7A-QF)") (class "Default")
      (node (ref "IC7") (pin "5") (pinfunction "QF_5") (pintype "tri_state"))
      (node (ref "R55") (pin "1") (pinfunction "1_1") (pintype "passive"))
    )
    (net (code "64") (name "Net-(IC7A-QG)") (class "Default")
      (node (ref "IC7") (pin "6") (pinfunction "QG_6") (pintype "tri_state"))
      (node (ref "R52") (pin "1") (pinfunction "1_1") (pintype "passive"))
    )
    (net (code "65") (name "Net-(IC7A-QH)") (class "Default")
      (node (ref "IC7") (pin "7") (pinfunction "QH_7") (pintype "tri_state"))
      (node (ref "R56") (pin "1") (pinfunction "1_1") (pintype "passive"))
    )
    (net (code "66") (name "Net-(IC7A-QH*)") (class "Default")
      (node (ref "IC7") (pin "9") (pinfunction "QH*_9") (pintype "tri_state"))
      (node (ref "IC8") (pin "14") (pinfunction "SER_14") (pintype "input"))
    )
    (net (code "67") (name "Net-(IC8A-QA)") (class "Default")
      (node (ref "IC8") (pin "15") (pinfunction "QA_15") (pintype "tri_state"))
      (node (ref "R57") (pin "1") (pinfunction "1_1") (pintype "passive"))
    )
    (net (code "68") (name "Net-(IC8A-QB)") (class "Default")
      (node (ref "IC8") (pin "1") (pinfunction "QB_1") (pintype "tri_state"))
      (node (ref "R61") (pin "1") (pinfunction "1_1") (pintype "passive"))
    )
    (net (code "69") (name "Net-(IC8A-QC)") (class "Default")
      (node (ref "IC8") (pin "2") (pinfunction "QC_2") (pintype "tri_state"))
      (node (ref "R58") (pin "1") (pinfunction "1_1") (pintype "passive"))
    )
    (net (code "70") (name "Net-(IC8A-QD)") (class "Default")
      (node (ref "IC8") (pin "3") (pinfunction "QD_3") (pintype "tri_state"))
      (node (ref "R62") (pin "1") (pinfunction "1_1") (pintype "passive"))
    )
    (net (code "71") (name "Net-(IC8A-QE)") (class "Default")
      (node (ref "IC8") (pin "4") (pinfunction "QE_4") (pintype "tri_state"))
      (node (ref "R59") (pin "1") (pinfunction "1_1") (pintype "passive"))
    )
    (net (code "72") (name "Net-(IC8A-QF)") (class "Default")
      (node (ref "IC8") (pin "5") (pinfunction "QF_5") (pintype "tri_state"))
      (node (ref "R63") (pin "1") (pinfunction "1_1") (pintype "passive"))
    )
    (net (code "73") (name "Net-(IC8A-QG)") (class "Default")
      (node (ref "IC8") (pin "6") (pinfunction "QG_6") (pintype "tri_state"))
      (node (ref "R60") (pin "1") (pinfunction "1_1") (pintype "passive"))
    )
    (net (code "74") (name "Net-(IC8A-QH)") (class "Default")
      (node (ref "IC8") (pin "7") (pinfunction "QH_7") (pintype "tri_state"))
      (node (ref "R64") (pin "1") (pinfunction "1_1") (pintype "passive"))
    )
    (net (code "75") (name "Net-(IC8A-QH*)") (class "Default")
      (node (ref "IC8") (pin "9") (pinfunction "QH*_9") (pintype "tri_state"))
      (node (ref "IC9") (pin "14") (pinfunction "SER_14") (pintype "input"))
    )
    (net (code "76") (name "Net-(IC9A-QA)") (class "Default")
      (node (ref "IC9") (pin "15") (pinfunction "QA_15") (pintype "tri_state"))
      (node (ref "R65") (pin "1") (pinfunction "1_1") (pintype "passive"))
    )
    (net (code "77") (name "Net-(IC9A-QB)") (class "Default")
      (node (ref "IC9") (pin "1") (pinfunction "QB_1") (pintype "tri_state"))
      (node (ref "R69") (pin "1") (pinfunction "1_1") (pintype "passive"))
    )
    (net (code "78") (name "Net-(IC9A-QC)") (class "Default")
      (node (ref "IC9") (pin "2") (pinfunction "QC_2") (pintype "tri_state"))
      (node (ref "R66") (pin "1") (pinfunction "1_1") (pintype "passive"))
    )
    (net (code "79") (name "Net-(IC9A-QD)") (class "Default")
      (node (ref "IC9") (pin "3") (pinfunction "QD_3") (pintype "tri_state"))
      (node (ref "R70") (pin "1") (pinfunction "1_1") (pintype "passive"))
    )
    (net (code "80") (name "Net-(IC9A-QE)") (class "Default")
      (node (ref "IC9") (pin "4") (pinfunction "QE_4") (pintype "tri_state"))
      (node (ref "R67") (pin "1") (pinfunction "1_1") (pintype "passive"))
    )
    (net (code "81") (name "Net-(IC9A-QF)") (class "Default")
      (node (ref "IC9") (pin "5") (pinfunction "QF_5") (pintype "tri_state"))
      (node (ref "R71") (pin "1") (pinfunction "1_1") (pintype "passive"))
    )
    (net (code "82") (name "Net-(IC9A-QG)") (class "Default")
      (node (ref "IC9") (pin "6") (pinfunction "QG_6") (pintype "tri_state"))
      (node (ref "R68") (pin "1") (pinfunction "1_1") (pintype "passive"))
    )
    (net (code "83") (name "Net-(IC9A-QH)") (class "Default")
      (node (ref "IC9") (pin "7") (pinfunction "QH_7") (pintype "tri_state"))
      (node (ref "R72") (pin "1") (pinfunction "1_1") (pintype "passive"))
    )
    (net (code "84") (name "Net-(IC10A-QA)") (class "Default")
      (node (ref "IC10") (pin "15") (pinfunction "QA_15") (pintype "tri_state"))
      (node (ref "R73") (pin "1") (pinfunction "1_1") (pintype "passive"))
    )
    (net (code "85") (name "Net-(IC10A-QB)") (class "Default")
      (node (ref "IC10") (pin "1") (pinfunction "QB_1") (pintype "tri_state"))
      (node (ref "R77") (pin "1") (pinfunction "1_1") (pintype "passive"))
    )
    (net (code "86") (name "Net-(IC10A-QC)") (class "Default")
      (node (ref "IC10") (pin "2") (pinfunction "QC_2") (pintype "tri_state"))
      (node (ref "R74") (pin "1") (pinfunction "1_1") (pintype "passive"))
    )
    (net (code "87") (name "Net-(IC10A-QD)") (class "Default")
      (node (ref "IC10") (pin "3") (pinfunction "QD_3") (pintype "tri_state"))
      (node (ref "R78") (pin "1") (pinfunction "1_1") (pintype "passive"))
    )
    (net (code "88") (name "Net-(IC10A-QE)") (class "Default")
      (node (ref "IC10") (pin "4") (pinfunction "QE_4") (pintype "tri_state"))
      (node (ref "R75") (pin "1") (pinfunction "1_1") (pintype "passive"))
    )
    (net (code "89") (name "Net-(IC10A-QF)") (class "Default")
      (node (ref "IC10") (pin "5") (pinfunction "QF_5") (pintype "tri_state"))
      (node (ref "R79") (pin "1") (pinfunction "1_1") (pintype "passive"))
    )
    (net (code "90") (name "Net-(IC10A-QG)") (class "Default")
      (node (ref "IC10") (pin "6") (pinfunction "QG_6") (pintype "tri_state"))
      (node (ref "R76") (pin "1") (pinfunction "1_1") (pintype "passive"))
    )
    (net (code "91") (name "Net-(IC10A-QH)") (class "Default")
      (node (ref "IC10") (pin "7") (pinfunction "QH_7") (pintype "tri_state"))
      (node (ref "R80") (pin "1") (pinfunction "1_1") (pintype "passive"))
    )
    (net (code "92") (name "Net-(IC10A-QH*)") (class "Default")
      (node (ref "IC10") (pin "9") (pinfunction "QH*_9") (pintype "tri_state"))
      (node (ref "IC11") (pin "14") (pinfunction "SER_14") (pintype "input"))
    )
    (net (code "93") (name "Net-(IC10A-RCK)") (class "Default")
      (node (ref "IC1") (pin "12") (pinfunction "RCK_12") (pintype "input"))
      (node (ref "IC10") (pin "12") (pinfunction "RCK_12") (pintype "input"))
      (node (ref "IC11") (pin "12") (pinfunction "RCK_12") (pintype "input"))
      (node (ref "IC12") (pin "12") (pinfunction "RCK_12") (pintype "input"))
      (node (ref "IC2") (pin "12") (pinfunction "RCK_12") (pintype "input"))
      (node (ref "IC3") (pin "12") (pinfunction "RCK_12") (pintype "input"))
      (node (ref "IC4") (pin "12") (pinfunction "RCK_12") (pintype "input"))
      (node (ref "IC5") (pin "12") (pinfunction "RCK_12") (pintype "input"))
      (node (ref "IC6") (pin "12") (pinfunction "RCK_12") (pintype "input"))
      (node (ref "IC7") (pin "12") (pinfunction "RCK_12") (pintype "input"))
      (node (ref "IC8") (pin "12") (pinfunction "RCK_12") (pintype "input"))
      (node (ref "IC9") (pin "12") (pinfunction "RCK_12") (pintype "input"))
      (node (ref "JP1") (pin "1") (pinfunction "1_1") (pintype "passive"))
    )
    (net (code "94") (name "Net-(IC10A-SCK)") (class "Default")
      (node (ref "IC1") (pin "11") (pinfunction "SCK_11") (pintype "input"))
      (node (ref "IC10") (pin "11") (pinfunction "SCK_11") (pintype "input"))
      (node (ref "IC11") (pin "11") (pinfunction "SCK_11") (pintype "input"))
      (node (ref "IC12") (pin "11") (pinfunction "SCK_11") (pintype "input"))
      (node (ref "IC2") (pin "11") (pinfunction "SCK_11") (pintype "input"))
      (node (ref "IC3") (pin "11") (pinfunction "SCK_11") (pintype "input"))
      (node (ref "IC4") (pin "11") (pinfunction "SCK_11") (pintype "input"))
      (node (ref "IC5") (pin "11") (pinfunction "SCK_11") (pintype "input"))
      (node (ref "IC6") (pin "11") (pinfunction "SCK_11") (pintype "input"))
      (node (ref "IC7") (pin "11") (pinfunction "SCK_11") (pintype "input"))
      (node (ref "IC8") (pin "11") (pinfunction "SCK_11") (pintype "input"))
      (node (ref "IC9") (pin "11") (pinfunction "SCK_11") (pintype "input"))
      (node (ref "JP1") (pin "2") (pinfunction "2_2") (pintype "passive"))
    )
    (net (code "95") (name "Net-(IC10A-SER)") (class "Default")
      (node (ref "IC10") (pin "14") (pinfunction "SER_14") (pintype "input"))
      (node (ref "IC9") (pin "9") (pinfunction "QH*_9") (pintype "tri_state"))
    )
    (net (code "96") (name "Net-(IC11A-QA)") (class "Default")
      (node (ref "IC11") (pin "15") (pinfunction "QA_15") (pintype "tri_state"))
      (node (ref "R81") (pin "1") (pinfunction "1_1") (pintype "passive"))
    )
    (net (code "97") (name "Net-(IC11A-QB)") (class "Default")
      (node (ref "IC11") (pin "1") (pinfunction "QB_1") (pintype "tri_state"))
      (node (ref "R85") (pin "1") (pinfunction "1_1") (pintype "passive"))
    )
    (net (code "98") (name "Net-(IC11A-QC)") (class "Default")
      (node (ref "IC11") (pin "2") (pinfunction "QC_2") (pintype "tri_state"))
      (node (ref "R82") (pin "1") (pinfunction "1_1") (pintype "passive"))
    )
    (net (code "99") (name "Net-(IC11A-QD)") (class "Default")
      (node (ref "IC11") (pin "3") (pinfunction "QD_3") (pintype "tri_state"))
      (node (ref "R86") (pin "1") (pinfunction "1_1") (pintype "passive"))
    )
    (net (code "100") (name "Net-(IC11A-QE)") (class "Default")
      (node (ref "IC11") (pin "4") (pinfunction "QE_4") (pintype "tri_state"))
      (node (ref "R83") (pin "1") (pinfunction "1_1") (pintype "passive"))
    )
    (net (code "101") (name "Net-(IC11A-QF)") (class "Default")
      (node (ref "IC11") (pin "5") (pinfunction "QF_5") (pintype "tri_state"))
      (node (ref "R87") (pin "1") (pinfunction "1_1") (pintype "passive"))
    )
    (net (code "102") (name "Net-(IC11A-QG)") (class "Default")
      (node (ref "IC11") (pin "6") (pinfunction "QG_6") (pintype "tri_state"))
      (node (ref "R84") (pin "1") (pinfunction "1_1") (pintype "passive"))
    )
    (net (code "103") (name "Net-(IC11A-QH)") (class "Default")
      (node (ref "IC11") (pin "7") (pinfunction "QH_7") (pintype "tri_state"))
      (node (ref "R88") (pin "1") (pinfunction "1_1") (pintype "passive"))
    )
    (net (code "104") (name "Net-(IC11A-QH*)") (class "Default")
      (node (ref "IC11") (pin "9") (pinfunction "QH*_9") (pintype "tri_state"))
      (node (ref "IC12") (pin "14") (pinfunction "SER_14") (pintype "input"))
    )
    (net (code "105") (name "Net-(IC12A-QA)") (class "Default")
      (node (ref "IC12") (pin "15") (pinfunction "QA_15") (pintype "tri_state"))
      (node (ref "R89") (pin "1") (pinfunction "1_1") (pintype "passive"))
    )
    (net (code "106") (name "Net-(IC12A-QB)") (class "Default")
      (node (ref "IC12") (pin "1") (pinfunction "QB_1") (pintype "tri_state"))
      (node (ref "R93") (pin "1") (pinfunction "1_1") (pintype "passive"))
    )
    (net (code "107") (name "Net-(IC12A-QC)") (class "Default")
      (node (ref "IC12") (pin "2") (pinfunction "QC_2") (pintype "tri_state"))
      (node (ref "R90") (pin "1") (pinfunction "1_1") (pintype "passive"))
    )
    (net (code "108") (name "Net-(IC12A-QD)") (class "Default")
      (node (ref "IC12") (pin "3") (pinfunction "QD_3") (pintype "tri_state"))
      (node (ref "R94") (pin "1") (pinfunction "1_1") (pintype "passive"))
    )
    (net (code "109") (name "Net-(IC12A-QE)") (class "Default")
      (node (ref "IC12") (pin "4") (pinfunction "QE_4") (pintype "tri_state"))
      (node (ref "R91") (pin "1") (pinfunction "1_1") (pintype "passive"))
    )
    (net (code "110") (name "Net-(IC12A-QF)") (class "Default")
      (node (ref "IC12") (pin "5") (pinfunction "QF_5") (pintype "tri_state"))
      (node (ref "R95") (pin "1") (pinfunction "1_1") (pintype "passive"))
    )
    (net (code "111") (name "Net-(IC12A-QG)") (class "Default")
      (node (ref "IC12") (pin "6") (pinfunction "QG_6") (pintype "tri_state"))
      (node (ref "R92") (pin "1") (pinfunction "1_1") (pintype "passive"))
    )
    (net (code "112") (name "Net-(IC12A-QH)") (class "Default")
      (node (ref "IC12") (pin "7") (pinfunction "QH_7") (pintype "tri_state"))
      (node (ref "R96") (pin "1") (pinfunction "1_1") (pintype "passive"))
    )
    (net (code "113") (name "Net-(T1-B)") (class "Default")
      (node (ref "R1") (pin "2") (pinfunction "2_2") (pintype "passive"))
      (node (ref "T1") (pin "2") (pinfunction "B_2") (pintype "passive"))
    )
    (net (code "114") (name "Net-(T1-C)") (class "Default")
      (node (ref "C1") (pin "2") (pinfunction "2_2") (pintype "passive"))
      (node (ref "D1") (pin "A") (pinfunction "A_A") (pintype "passive"))
      (node (ref "MT1") (pin "2") (pinfunction "2_2") (pintype "passive"))
      (node (ref "T1") (pin "3") (pinfunction "C_3") (pintype "passive"))
    )
    (net (code "115") (name "Net-(T2-B)") (class "Default")
      (node (ref "R2") (pin "2") (pinfunction "2_2") (pintype "passive"))
      (node (ref "T2") (pin "2") (pinfunction "B_2") (pintype "passive"))
    )
    (net (code "116") (name "Net-(T2-C)") (class "Default")
      (node (ref "C2") (pin "2") (pinfunction "2_2") (pintype "passive"))
      (node (ref "D2") (pin "A") (pinfunction "A_A") (pintype "passive"))
      (node (ref "MT2") (pin "2") (pinfunction "2_2") (pintype "passive"))
      (node (ref "T2") (pin "3") (pinfunction "C_3") (pintype "passive"))
    )
    (net (code "117") (name "Net-(T3-B)") (class "Default")
      (node (ref "R3") (pin "2") (pinfunction "2_2") (pintype "passive"))
      (node (ref "T3") (pin "2") (pinfunction "B_2") (pintype "passive"))
    )
    (net (code "118") (name "Net-(T3-C)") (class "Default")
      (node (ref "C3") (pin "2") (pinfunction "2_2") (pintype "passive"))
      (node (ref "D3") (pin "A") (pinfunction "A_A") (pintype "passive"))
      (node (ref "MT3") (pin "2") (pinfunction "2_2") (pintype "passive"))
      (node (ref "T3") (pin "3") (pinfunction "C_3") (pintype "passive"))
    )
    (net (code "119") (name "Net-(T4-B)") (class "Default")
      (node (ref "R4") (pin "2") (pinfunction "2_2") (pintype "passive"))
      (node (ref "T4") (pin "2") (pinfunction "B_2") (pintype "passive"))
    )
    (net (code "120") (name "Net-(T4-C)") (class "Default")
      (node (ref "C4") (pin "2") (pinfunction "2_2") (pintype "passive"))
      (node (ref "D4") (pin "A") (pinfunction "A_A") (pintype "passive"))
      (node (ref "MT4") (pin "2") (pinfunction "2_2") (pintype "passive"))
      (node (ref "T4") (pin "3") (pinfunction "C_3") (pintype "passive"))
    )
    (net (code "121") (name "Net-(T5-B)") (class "Default")
      (node (ref "R5") (pin "2") (pinfunction "2_2") (pintype "passive"))
      (node (ref "T5") (pin "2") (pinfunction "B_2") (pintype "passive"))
    )
    (net (code "122") (name "Net-(T5-C)") (class "Default")
      (node (ref "C5") (pin "2") (pinfunction "2_2") (pintype "passive"))
      (node (ref "D5") (pin "A") (pinfunction "A_A") (pintype "passive"))
      (node (ref "MT5") (pin "2") (pinfunction "2_2") (pintype "passive"))
      (node (ref "T5") (pin "3") (pinfunction "C_3") (pintype "passive"))
    )
    (net (code "123") (name "Net-(T6-B)") (class "Default")
      (node (ref "R6") (pin "2") (pinfunction "2_2") (pintype "passive"))
      (node (ref "T6") (pin "2") (pinfunction "B_2") (pintype "passive"))
    )
    (net (code "124") (name "Net-(T6-C)") (class "Default")
      (node (ref "C6") (pin "2") (pinfunction "2_2") (pintype "passive"))
      (node (ref "D6") (pin "A") (pinfunction "A_A") (pintype "passive"))
      (node (ref "MT6") (pin "2") (pinfunction "2_2") (pintype "passive"))
      (node (ref "T6") (pin "3") (pinfunction "C_3") (pintype "passive"))
    )
    (net (code "125") (name "Net-(T7-B)") (class "Default")
      (node (ref "R7") (pin "2") (pinfunction "2_2") (pintype "passive"))
      (node (ref "T7") (pin "2") (pinfunction "B_2") (pintype "passive"))
    )
    (net (code "126") (name "Net-(T7-C)") (class "Default")
      (node (ref "C7") (pin "2") (pinfunction "2_2") (pintype "passive"))
      (node (ref "D7") (pin "A") (pinfunction "A_A") (pintype "passive"))
      (node (ref "MT7") (pin "2") (pinfunction "2_2") (pintype "passive"))
      (node (ref "T7") (pin "3") (pinfunction "C_3") (pintype "passive"))
    )
    (net (code "127") (name "Net-(T8-B)") (class "Default")
      (node (ref "R8") (pin "2") (pinfunction "2_2") (pintype "passive"))
      (node (ref "T8") (pin "2") (pinfunction "B_2") (pintype "passive"))
    )
    (net (code "128") (name "Net-(T8-C)") (class "Default")
      (node (ref "C8") (pin "2") (pinfunction "2_2") (pintype "passive"))
      (node (ref "D8") (pin "A") (pinfunction "A_A") (pintype "passive"))
      (node (ref "MT8") (pin "2") (pinfunction "2_2") (pintype "passive"))
      (node (ref "T8") (pin "3") (pinfunction "C_3") (pintype "passive"))
    )
    (net (code "129") (name "Net-(T9-B)") (class "Default")
      (node (ref "R9") (pin "2") (pinfunction "2_2") (pintype "passive"))
      (node (ref "T9") (pin "2") (pinfunction "B_2") (pintype "passive"))
    )
    (net (code "130") (name "Net-(T9-C)") (class "Default")
      (node (ref "C9") (pin "2") (pinfunction "2_2") (pintype "passive"))
      (node (ref "D9") (pin "A") (pinfunction "A_A") (pintype "passive"))
      (node (ref "MT9") (pin "2") (pinfunction "2_2") (pintype "passive"))
      (node (ref "T9") (pin "3") (pinfunction "C_3") (pintype "passive"))
    )
    (net (code "131") (name "Net-(T10-B)") (class "Default")
      (node (ref "R10") (pin "2") (pinfunction "2_2") (pintype "passive"))
      (node (ref "T10") (pin "2") (pinfunction "B_2") (pintype "passive"))
    )
    (net (code "132") (name "Net-(T10-C)") (class "Default")
      (node (ref "C10") (pin "2") (pinfunction "2_2") (pintype "passive"))
      (node (ref "D10") (pin "A") (pinfunction "A_A") (pintype "passive"))
      (node (ref "MT10") (pin "2") (pinfunction "2_2") (pintype "passive"))
      (node (ref "T10") (pin "3") (pinfunction "C_3") (pintype "passive"))
    )
    (net (code "133") (name "Net-(T11-B)") (class "Default")
      (node (ref "R11") (pin "2") (pinfunction "2_2") (pintype "passive"))
      (node (ref "T11") (pin "2") (pinfunction "B_2") (pintype "passive"))
    )
    (net (code "134") (name "Net-(T11-C)") (class "Default")
      (node (ref "C11") (pin "2") (pinfunction "2_2") (pintype "passive"))
      (node (ref "D11") (pin "A") (pinfunction "A_A") (pintype "passive"))
      (node (ref "MT11") (pin "2") (pinfunction "2_2") (pintype "passive"))
      (node (ref "T11") (pin "3") (pinfunction "C_3") (pintype "passive"))
    )
    (net (code "135") (name "Net-(T12-B)") (class "Default")
      (node (ref "R12") (pin "2") (pinfunction "2_2") (pintype "passive"))
      (node (ref "T12") (pin "2") (pinfunction "B_2") (pintype "passive"))
    )
    (net (code "136") (name "Net-(T12-C)") (class "Default")
      (node (ref "C12") (pin "2") (pinfunction "2_2") (pintype "passive"))
      (node (ref "D12") (pin "A") (pinfunction "A_A") (pintype "passive"))
      (node (ref "MT12") (pin "2") (pinfunction "2_2") (pintype "passive"))
      (node (ref "T12") (pin "3") (pinfunction "C_3") (pintype "passive"))
    )
    (net (code "137") (name "Net-(T13-B)") (class "Default")
      (node (ref "R13") (pin "2") (pinfunction "2_2") (pintype "passive"))
      (node (ref "T13") (pin "2") (pinfunction "B_2") (pintype "passive"))
    )
    (net (code "138") (name "Net-(T13-C)") (class "Default")
      (node (ref "C13") (pin "2") (pinfunction "2_2") (pintype "passive"))
      (node (ref "D13") (pin "A") (pinfunction "A_A") (pintype "passive"))
      (node (ref "MT13") (pin "2") (pinfunction "2_2") (pintype "passive"))
      (node (ref "T13") (pin "3") (pinfunction "C_3") (pintype "passive"))
    )
    (net (code "139") (name "Net-(T14-B)") (class "Default")
      (node (ref "R14") (pin "2") (pinfunction "2_2") (pintype "passive"))
      (node (ref "T14") (pin "2") (pinfunction "B_2") (pintype "passive"))
    )
    (net (code "140") (name "Net-(T14-C)") (class "Default")
      (node (ref "C14") (pin "2") (pinfunction "2_2") (pintype "passive"))
      (node (ref "D14") (pin "A") (pinfunction "A_A") (pintype "passive"))
      (node (ref "MT14") (pin "2") (pinfunction "2_2") (pintype "passive"))
      (node (ref "T14") (pin "3") (pinfunction "C_3") (pintype "passive"))
    )
    (net (code "141") (name "Net-(T15-B)") (class "Default")
      (node (ref "R15") (pin "2") (pinfunction "2_2") (pintype "passive"))
      (node (ref "T15") (pin "2") (pinfunction "B_2") (pintype "passive"))
    )
    (net (code "142") (name "Net-(T15-C)") (class "Default")
      (node (ref "C15") (pin "2") (pinfunction "2_2") (pintype "passive"))
      (node (ref "D15") (pin "A") (pinfunction "A_A") (pintype "passive"))
      (node (ref "MT15") (pin "2") (pinfunction "2_2") (pintype "passive"))
      (node (ref "T15") (pin "3") (pinfunction "C_3") (pintype "passive"))
    )
    (net (code "143") (name "Net-(T16-B)") (class "Default")
      (node (ref "R16") (pin "2") (pinfunction "2_2") (pintype "passive"))
      (node (ref "T16") (pin "2") (pinfunction "B_2") (pintype "passive"))
    )
    (net (code "144") (name "Net-(T16-C)") (class "Default")
      (node (ref "C16") (pin "2") (pinfunction "2_2") (pintype "passive"))
      (node (ref "D16") (pin "A") (pinfunction "A_A") (pintype "passive"))
      (node (ref "MT16") (pin "2") (pinfunction "2_2") (pintype "passive"))
      (node (ref "T16") (pin "3") (pinfunction "C_3") (pintype "passive"))
    )
    (net (code "145") (name "Net-(T17-B)") (class "Default")
      (node (ref "R17") (pin "2") (pinfunction "2_2") (pintype "passive"))
      (node (ref "T17") (pin "2") (pinfunction "B_2") (pintype "passive"))
    )
    (net (code "146") (name "Net-(T17-C)") (class "Default")
      (node (ref "C17") (pin "2") (pinfunction "2_2") (pintype "passive"))
      (node (ref "D17") (pin "A") (pinfunction "A_A") (pintype "passive"))
      (node (ref "MT17") (pin "2") (pinfunction "2_2") (pintype "passive"))
      (node (ref "T17") (pin "3") (pinfunction "C_3") (pintype "passive"))
    )
    (net (code "147") (name "Net-(T18-B)") (class "Default")
      (node (ref "R18") (pin "2") (pinfunction "2_2") (pintype "passive"))
      (node (ref "T18") (pin "2") (pinfunction "B_2") (pintype "passive"))
    )
    (net (code "148") (name "Net-(T18-C)") (class "Default")
      (node (ref "C18") (pin "2") (pinfunction "2_2") (pintype "passive"))
      (node (ref "D18") (pin "A") (pinfunction "A_A") (pintype "passive"))
      (node (ref "MT18") (pin "2") (pinfunction "2_2") (pintype "passive"))
      (node (ref "T18") (pin "3") (pinfunction "C_3") (pintype "passive"))
    )
    (net (code "149") (name "Net-(T19-B)") (class "Default")
      (node (ref "R19") (pin "2") (pinfunction "2_2") (pintype "passive"))
      (node (ref "T19") (pin "2") (pinfunction "B_2") (pintype "passive"))
    )
    (net (code "150") (name "Net-(T19-C)") (class "Default")
      (node (ref "C19") (pin "2") (pinfunction "2_2") (pintype "passive"))
      (node (ref "D19") (pin "A") (pinfunction "A_A") (pintype "passive"))
      (node (ref "MT19") (pin "2") (pinfunction "2_2") (pintype "passive"))
      (node (ref "T19") (pin "3") (pinfunction "C_3") (pintype "passive"))
    )
    (net (code "151") (name "Net-(T20-B)") (class "Default")
      (node (ref "R20") (pin "2") (pinfunction "2_2") (pintype "passive"))
      (node (ref "T20") (pin "2") (pinfunction "B_2") (pintype "passive"))
    )
    (net (code "152") (name "Net-(T20-C)") (class "Default")
      (node (ref "C20") (pin "2") (pinfunction "2_2") (pintype "passive"))
      (node (ref "D20") (pin "A") (pinfunction "A_A") (pintype "passive"))
      (node (ref "MT20") (pin "2") (pinfunction "2_2") (pintype "passive"))
      (node (ref "T20") (pin "3") (pinfunction "C_3") (pintype "passive"))
    )
    (net (code "153") (name "Net-(T21-B)") (class "Default")
      (node (ref "R21") (pin "2") (pinfunction "2_2") (pintype "passive"))
      (node (ref "T21") (pin "2") (pinfunction "B_2") (pintype "passive"))
    )
    (net (code "154") (name "Net-(T21-C)") (class "Default")
      (node (ref "C21") (pin "2") (pinfunction "2_2") (pintype "passive"))
      (node (ref "D21") (pin "A") (pinfunction "A_A") (pintype "passive"))
      (node (ref "MT21") (pin "2") (pinfunction "2_2") (pintype "passive"))
      (node (ref "T21") (pin "3") (pinfunction "C_3") (pintype "passive"))
    )
    (net (code "155") (name "Net-(T22-B)") (class "Default")
      (node (ref "R22") (pin "2") (pinfunction "2_2") (pintype "passive"))
      (node (ref "T22") (pin "2") (pinfunction "B_2") (pintype "passive"))
    )
    (net (code "156") (name "Net-(T22-C)") (class "Default")
      (node (ref "C22") (pin "2") (pinfunction "2_2") (pintype "passive"))
      (node (ref "D22") (pin "A") (pinfunction "A_A") (pintype "passive"))
      (node (ref "MT22") (pin "2") (pinfunction "2_2") (pintype "passive"))
      (node (ref "T22") (pin "3") (pinfunction "C_3") (pintype "passive"))
    )
    (net (code "157") (name "Net-(T23-B)") (class "Default")
      (node (ref "R23") (pin "2") (pinfunction "2_2") (pintype "passive"))
      (node (ref "T23") (pin "2") (pinfunction "B_2") (pintype "passive"))
    )
    (net (code "158") (name "Net-(T23-C)") (class "Default")
      (node (ref "C23") (pin "2") (pinfunction "2_2") (pintype "passive"))
      (node (ref "D23") (pin "A") (pinfunction "A_A") (pintype "passive"))
      (node (ref "MT23") (pin "2") (pinfunction "2_2") (pintype "passive"))
      (node (ref "T23") (pin "3") (pinfunction "C_3") (pintype "passive"))
    )
    (net (code "159") (name "Net-(T24-B)") (class "Default")
      (node (ref "R24") (pin "2") (pinfunction "2_2") (pintype "passive"))
      (node (ref "T24") (pin "2") (pinfunction "B_2") (pintype "passive"))
    )
    (net (code "160") (name "Net-(T24-C)") (class "Default")
      (node (ref "C24") (pin "2") (pinfunction "2_2") (pintype "passive"))
      (node (ref "D24") (pin "A") (pinfunction "A_A") (pintype "passive"))
      (node (ref "MT24") (pin "2") (pinfunction "2_2") (pintype "passive"))
      (node (ref "T24") (pin "3") (pinfunction "C_3") (pintype "passive"))
    )
    (net (code "161") (name "Net-(T25-B)") (class "Default")
      (node (ref "R25") (pin "2") (pinfunction "2_2") (pintype "passive"))
      (node (ref "T25") (pin "2") (pinfunction "B_2") (pintype "passive"))
    )
    (net (code "162") (name "Net-(T25-C)") (class "Default")
      (node (ref "C25") (pin "2") (pinfunction "2_2") (pintype "passive"))
      (node (ref "D25") (pin "A") (pinfunction "A_A") (pintype "passive"))
      (node (ref "MT25") (pin "2") (pinfunction "2_2") (pintype "passive"))
      (node (ref "T25") (pin "3") (pinfunction "C_3") (pintype "passive"))
    )
    (net (code "163") (name "Net-(T26-B)") (class "Default")
      (node (ref "R26") (pin "2") (pinfunction "2_2") (pintype "passive"))
      (node (ref "T26") (pin "2") (pinfunction "B_2") (pintype "passive"))
    )
    (net (code "164") (name "Net-(T26-C)") (class "Default")
      (node (ref "C26") (pin "2") (pinfunction "2_2") (pintype "passive"))
      (node (ref "D26") (pin "A") (pinfunction "A_A") (pintype "passive"))
      (node (ref "MT26") (pin "2") (pinfunction "2_2") (pintype "passive"))
      (node (ref "T26") (pin "3") (pinfunction "C_3") (pintype "passive"))
    )
    (net (code "165") (name "Net-(T27-B)") (class "Default")
      (node (ref "R27") (pin "2") (pinfunction "2_2") (pintype "passive"))
      (node (ref "T27") (pin "2") (pinfunction "B_2") (pintype "passive"))
    )
    (net (code "166") (name "Net-(T27-C)") (class "Default")
      (node (ref "C27") (pin "2") (pinfunction "2_2") (pintype "passive"))
      (node (ref "D27") (pin "A") (pinfunction "A_A") (pintype "passive"))
      (node (ref "MT27") (pin "2") (pinfunction "2_2") (pintype "passive"))
      (node (ref "T27") (pin "3") (pinfunction "C_3") (pintype "passive"))
    )
    (net (code "167") (name "Net-(T28-B)") (class "Default")
      (node (ref "R28") (pin "2") (pinfunction "2_2") (pintype "passive"))
      (node (ref "T28") (pin "2") (pinfunction "B_2") (pintype "passive"))
    )
    (net (code "168") (name "Net-(T28-C)") (class "Default")
      (node (ref "C28") (pin "2") (pinfunction "2_2") (pintype "passive"))
      (node (ref "D28") (pin "A") (pinfunction "A_A") (pintype "passive"))
      (node (ref "MT28") (pin "2") (pinfunction "2_2") (pintype "passive"))
      (node (ref "T28") (pin "3") (pinfunction "C_3") (pintype "passive"))
    )
    (net (code "169") (name "Net-(T29-B)") (class "Default")
      (node (ref "R29") (pin "2") (pinfunction "2_2") (pintype "passive"))
      (node (ref "T29") (pin "2") (pinfunction "B_2") (pintype "passive"))
    )
    (net (code "170") (name "Net-(T29-C)") (class "Default")
      (node (ref "C29") (pin "2") (pinfunction "2_2") (pintype "passive"))
      (node (ref "D29") (pin "A") (pinfunction "A_A") (pintype "passive"))
      (node (ref "MT29") (pin "2") (pinfunction "2_2") (pintype "passive"))
      (node (ref "T29") (pin "3") (pinfunction "C_3") (pintype "passive"))
    )
    (net (code "171") (name "Net-(T30-B)") (class "Default")
      (node (ref "R30") (pin "2") (pinfunction "2_2") (pintype "passive"))
      (node (ref "T30") (pin "2") (pinfunction "B_2") (pintype "passive"))
    )
    (net (code "172") (name "Net-(T30-C)") (class "Default")
      (node (ref "C30") (pin "2") (pinfunction "2_2") (pintype "passive"))
      (node (ref "D30") (pin "A") (pinfunction "A_A") (pintype "passive"))
      (node (ref "MT30") (pin "2") (pinfunction "2_2") (pintype "passive"))
      (node (ref "T30") (pin "3") (pinfunction "C_3") (pintype "passive"))
    )
    (net (code "173") (name "Net-(T31-B)") (class "Default")
      (node (ref "R31") (pin "2") (pinfunction "2_2") (pintype "passive"))
      (node (ref "T31") (pin "2") (pinfunction "B_2") (pintype "passive"))
    )
    (net (code "174") (name "Net-(T31-C)") (class "Default")
      (node (ref "C31") (pin "2") (pinfunction "2_2") (pintype "passive"))
      (node (ref "D31") (pin "A") (pinfunction "A_A") (pintype "passive"))
      (node (ref "MT31") (pin "2") (pinfunction "2_2") (pintype "passive"))
      (node (ref "T31") (pin "3") (pinfunction "C_3") (pintype "passive"))
    )
    (net (code "175") (name "Net-(T32-B)") (class "Default")
      (node (ref "R32") (pin "2") (pinfunction "2_2") (pintype "passive"))
      (node (ref "T32") (pin "2") (pinfunction "B_2") (pintype "passive"))
    )
    (net (code "176") (name "Net-(T32-C)") (class "Default")
      (node (ref "C32") (pin "2") (pinfunction "2_2") (pintype "passive"))
      (node (ref "D32") (pin "A") (pinfunction "A_A") (pintype "passive"))
      (node (ref "MT32") (pin "2") (pinfunction "2_2") (pintype "passive"))
      (node (ref "T32") (pin "3") (pinfunction "C_3") (pintype "passive"))
    )
    (net (code "177") (name "Net-(T33-B)") (class "Default")
      (node (ref "R33") (pin "2") (pinfunction "2_2") (pintype "passive"))
      (node (ref "T33") (pin "2") (pinfunction "B_2") (pintype "passive"))
    )
    (net (code "178") (name "Net-(T33-C)") (class "Default")
      (node (ref "C33") (pin "2") (pinfunction "2_2") (pintype "passive"))
      (node (ref "D33") (pin "A") (pinfunction "A_A") (pintype "passive"))
      (node (ref "MT33") (pin "2") (pinfunction "2_2") (pintype "passive"))
      (node (ref "T33") (pin "3") (pinfunction "C_3") (pintype "passive"))
    )
    (net (code "179") (name "Net-(T34-B)") (class "Default")
      (node (ref "R34") (pin "2") (pinfunction "2_2") (pintype "passive"))
      (node (ref "T34") (pin "2") (pinfunction "B_2") (pintype "passive"))
    )
    (net (code "180") (name "Net-(T34-C)") (class "Default")
      (node (ref "C34") (pin "2") (pinfunction "2_2") (pintype "passive"))
      (node (ref "D34") (pin "A") (pinfunction "A_A") (pintype "passive"))
      (node (ref "MT34") (pin "2") (pinfunction "2_2") (pintype "passive"))
      (node (ref "T34") (pin "3") (pinfunction "C_3") (pintype "passive"))
    )
    (net (code "181") (name "Net-(T35-B)") (class "Default")
      (node (ref "R35") (pin "2") (pinfunction "2_2") (pintype "passive"))
      (node (ref "T35") (pin "2") (pinfunction "B_2") (pintype "passive"))
    )
    (net (code "182") (name "Net-(T35-C)") (class "Default")
      (node (ref "C35") (pin "2") (pinfunction "2_2") (pintype "passive"))
      (node (ref "D35") (pin "A") (pinfunction "A_A") (pintype "passive"))
      (node (ref "MT35") (pin "2") (pinfunction "2_2") (pintype "passive"))
      (node (ref "T35") (pin "3") (pinfunction "C_3") (pintype "passive"))
    )
    (net (code "183") (name "Net-(T36-B)") (class "Default")
      (node (ref "R36") (pin "2") (pinfunction "2_2") (pintype "passive"))
      (node (ref "T36") (pin "2") (pinfunction "B_2") (pintype "passive"))
    )
    (net (code "184") (name "Net-(T36-C)") (class "Default")
      (node (ref "C36") (pin "2") (pinfunction "2_2") (pintype "passive"))
      (node (ref "D36") (pin "A") (pinfunction "A_A") (pintype "passive"))
      (node (ref "MT36") (pin "2") (pinfunction "2_2") (pintype "passive"))
      (node (ref "T36") (pin "3") (pinfunction "C_3") (pintype "passive"))
    )
    (net (code "185") (name "Net-(T37-B)") (class "Default")
      (node (ref "R37") (pin "2") (pinfunction "2_2") (pintype "passive"))
      (node (ref "T37") (pin "2") (pinfunction "B_2") (pintype "passive"))
    )
    (net (code "186") (name "Net-(T37-C)") (class "Default")
      (node (ref "C37") (pin "2") (pinfunction "2_2") (pintype "passive"))
      (node (ref "D37") (pin "A") (pinfunction "A_A") (pintype "passive"))
      (node (ref "MT37") (pin "2") (pinfunction "2_2") (pintype "passive"))
      (node (ref "T37") (pin "3") (pinfunction "C_3") (pintype "passive"))
    )
    (net (code "187") (name "Net-(T38-B)") (class "Default")
      (node (ref "R38") (pin "2") (pinfunction "2_2") (pintype "passive"))
      (node (ref "T38") (pin "2") (pinfunction "B_2") (pintype "passive"))
    )
    (net (code "188") (name "Net-(T38-C)") (class "Default")
      (node (ref "C38") (pin "2") (pinfunction "2_2") (pintype "passive"))
      (node (ref "D38") (pin "A") (pinfunction "A_A") (pintype "passive"))
      (node (ref "MT38") (pin "2") (pinfunction "2_2") (pintype "passive"))
      (node (ref "T38") (pin "3") (pinfunction "C_3") (pintype "passive"))
    )
    (net (code "189") (name "Net-(T39-B)") (class "Default")
      (node (ref "R39") (pin "2") (pinfunction "2_2") (pintype "passive"))
      (node (ref "T39") (pin "2") (pinfunction "B_2") (pintype "passive"))
    )
    (net (code "190") (name "Net-(T39-C)") (class "Default")
      (node (ref "C39") (pin "2") (pinfunction "2_2") (pintype "passive"))
      (node (ref "D39") (pin "A") (pinfunction "A_A") (pintype "passive"))
      (node (ref "MT39") (pin "2") (pinfunction "2_2") (pintype "passive"))
      (node (ref "T39") (pin "3") (pinfunction "C_3") (pintype "passive"))
    )
    (net (code "191") (name "Net-(T40-B)") (class "Default")
      (node (ref "R40") (pin "2") (pinfunction "2_2") (pintype "passive"))
      (node (ref "T40") (pin "2") (pinfunction "B_2") (pintype "passive"))
    )
    (net (code "192") (name "Net-(T40-C)") (class "Default")
      (node (ref "C40") (pin "2") (pinfunction "2_2") (pintype "passive"))
      (node (ref "D40") (pin "A") (pinfunction "A_A") (pintype "passive"))
      (node (ref "MT40") (pin "2") (pinfunction "2_2") (pintype "passive"))
      (node (ref "T40") (pin "3") (pinfunction "C_3") (pintype "passive"))
    )
    (net (code "193") (name "Net-(T41-B)") (class "Default")
      (node (ref "R41") (pin "2") (pinfunction "2_2") (pintype "passive"))
      (node (ref "T41") (pin "2") (pinfunction "B_2") (pintype "passive"))
    )
    (net (code "194") (name "Net-(T41-C)") (class "Default")
      (node (ref "C41") (pin "2") (pinfunction "2_2") (pintype "passive"))
      (node (ref "D41") (pin "A") (pinfunction "A_A") (pintype "passive"))
      (node (ref "MT41") (pin "2") (pinfunction "2_2") (pintype "passive"))
      (node (ref "T41") (pin "3") (pinfunction "C_3") (pintype "passive"))
    )
    (net (code "195") (name "Net-(T42-B)") (class "Default")
      (node (ref "R42") (pin "2") (pinfunction "2_2") (pintype "passive"))
      (node (ref "T42") (pin "2") (pinfunction "B_2") (pintype "passive"))
    )
    (net (code "196") (name "Net-(T42-C)") (class "Default")
      (node (ref "C42") (pin "2") (pinfunction "2_2") (pintype "passive"))
      (node (ref "D42") (pin "A") (pinfunction "A_A") (pintype "passive"))
      (node (ref "MT42") (pin "2") (pinfunction "2_2") (pintype "passive"))
      (node (ref "T42") (pin "3") (pinfunction "C_3") (pintype "passive"))
    )
    (net (code "197") (name "Net-(T43-B)") (class "Default")
      (node (ref "R43") (pin "2") (pinfunction "2_2") (pintype "passive"))
      (node (ref "T43") (pin "2") (pinfunction "B_2") (pintype "passive"))
    )
    (net (code "198") (name "Net-(T43-C)") (class "Default")
      (node (ref "C43") (pin "2") (pinfunction "2_2") (pintype "passive"))
      (node (ref "D43") (pin "A") (pinfunction "A_A") (pintype "passive"))
      (node (ref "MT43") (pin "2") (pinfunction "2_2") (pintype "passive"))
      (node (ref "T43") (pin "3") (pinfunction "C_3") (pintype "passive"))
    )
    (net (code "199") (name "Net-(T44-B)") (class "Default")
      (node (ref "R44") (pin "2") (pinfunction "2_2") (pintype "passive"))
      (node (ref "T44") (pin "2") (pinfunction "B_2") (pintype "passive"))
    )
    (net (code "200") (name "Net-(T44-C)") (class "Default")
      (node (ref "C44") (pin "2") (pinfunction "2_2") (pintype "passive"))
      (node (ref "D44") (pin "A") (pinfunction "A_A") (pintype "passive"))
      (node (ref "MT44") (pin "2") (pinfunction "2_2") (pintype "passive"))
      (node (ref "T44") (pin "3") (pinfunction "C_3") (pintype "passive"))
    )
    (net (code "201") (name "Net-(T45-B)") (class "Default")
      (node (ref "R45") (pin "2") (pinfunction "2_2") (pintype "passive"))
      (node (ref "T45") (pin "2") (pinfunction "B_2") (pintype "passive"))
    )
    (net (code "202") (name "Net-(T45-C)") (class "Default")
      (node (ref "C45") (pin "2") (pinfunction "2_2") (pintype "passive"))
      (node (ref "D45") (pin "A") (pinfunction "A_A") (pintype "passive"))
      (node (ref "MT45") (pin "2") (pinfunction "2_2") (pintype "passive"))
      (node (ref "T45") (pin "3") (pinfunction "C_3") (pintype "passive"))
    )
    (net (code "203") (name "Net-(T46-B)") (class "Default")
      (node (ref "R46") (pin "2") (pinfunction "2_2") (pintype "passive"))
      (node (ref "T46") (pin "2") (pinfunction "B_2") (pintype "passive"))
    )
    (net (code "204") (name "Net-(T46-C)") (class "Default")
      (node (ref "C46") (pin "2") (pinfunction "2_2") (pintype "passive"))
      (node (ref "D46") (pin "A") (pinfunction "A_A") (pintype "passive"))
      (node (ref "MT46") (pin "2") (pinfunction "2_2") (pintype "passive"))
      (node (ref "T46") (pin "3") (pinfunction "C_3") (pintype "passive"))
    )
    (net (code "205") (name "Net-(T47-B)") (class "Default")
      (node (ref "R47") (pin "2") (pinfunction "2_2") (pintype "passive"))
      (node (ref "T47") (pin "2") (pinfunction "B_2") (pintype "passive"))
    )
    (net (code "206") (name "Net-(T47-C)") (class "Default")
      (node (ref "C47") (pin "2") (pinfunction "2_2") (pintype "passive"))
      (node (ref "D47") (pin "A") (pinfunction "A_A") (pintype "passive"))
      (node (ref "MT47") (pin "2") (pinfunction "2_2") (pintype "passive"))
      (node (ref "T47") (pin "3") (pinfunction "C_3") (pintype "passive"))
    )
    (net (code "207") (name "Net-(T48-B)") (class "Default")
      (node (ref "R48") (pin "2") (pinfunction "2_2") (pintype "passive"))
      (node (ref "T48") (pin "2") (pinfunction "B_2") (pintype "passive"))
    )
    (net (code "208") (name "Net-(T48-C)") (class "Default")
      (node (ref "C48") (pin "2") (pinfunction "2_2") (pintype "passive"))
      (node (ref "D48") (pin "A") (pinfunction "A_A") (pintype "passive"))
      (node (ref "MT48") (pin "2") (pinfunction "2_2") (pintype "passive"))
      (node (ref "T48") (pin "3") (pinfunction "C_3") (pintype "passive"))
    )
    (net (code "209") (name "Net-(T49-B)") (class "Default")
      (node (ref "R49") (pin "2") (pinfunction "2_2") (pintype "passive"))
      (node (ref "T49") (pin "2") (pinfunction "B_2") (pintype "passive"))
    )
    (net (code "210") (name "Net-(T49-C)") (class "Default")
      (node (ref "C49") (pin "2") (pinfunction "2_2") (pintype "passive"))
      (node (ref "D49") (pin "A") (pinfunction "A_A") (pintype "passive"))
      (node (ref "MT49") (pin "2") (pinfunction "2_2") (pintype "passive"))
      (node (ref "T49") (pin "3") (pinfunction "C_3") (pintype "passive"))
    )
    (net (code "211") (name "Net-(T50-B)") (class "Default")
      (node (ref "R50") (pin "2") (pinfunction "2_2") (pintype "passive"))
      (node (ref "T50") (pin "2") (pinfunction "B_2") (pintype "passive"))
    )
    (net (code "212") (name "Net-(T50-C)") (class "Default")
      (node (ref "C50") (pin "2") (pinfunction "2_2") (pintype "passive"))
      (node (ref "D50") (pin "A") (pinfunction "A_A") (pintype "passive"))
      (node (ref "MT50") (pin "2") (pinfunction "2_2") (pintype "passive"))
      (node (ref "T50") (pin "3") (pinfunction "C_3") (pintype "passive"))
    )
    (net (code "213") (name "Net-(T51-B)") (class "Default")
      (node (ref "R51") (pin "2") (pinfunction "2_2") (pintype "passive"))
      (node (ref "T51") (pin "2") (pinfunction "B_2") (pintype "passive"))
    )
    (net (code "214") (name "Net-(T51-C)") (class "Default")
      (node (ref "C51") (pin "2") (pinfunction "2_2") (pintype "passive"))
      (node (ref "D51") (pin "A") (pinfunction "A_A") (pintype "passive"))
      (node (ref "MT51") (pin "2") (pinfunction "2_2") (pintype "passive"))
      (node (ref "T51") (pin "3") (pinfunction "C_3") (pintype "passive"))
    )
    (net (code "215") (name "Net-(T52-B)") (class "Default")
      (node (ref "R52") (pin "2") (pinfunction "2_2") (pintype "passive"))
      (node (ref "T52") (pin "2") (pinfunction "B_2") (pintype "passive"))
    )
    (net (code "216") (name "Net-(T52-C)") (class "Default")
      (node (ref "C52") (pin "2") (pinfunction "2_2") (pintype "passive"))
      (node (ref "D52") (pin "A") (pinfunction "A_A") (pintype "passive"))
      (node (ref "MT52") (pin "2") (pinfunction "2_2") (pintype "passive"))
      (node (ref "T52") (pin "3") (pinfunction "C_3") (pintype "passive"))
    )
    (net (code "217") (name "Net-(T53-B)") (class "Default")
      (node (ref "R53") (pin "2") (pinfunction "2_2") (pintype "passive"))
      (node (ref "T53") (pin "2") (pinfunction "B_2") (pintype "passive"))
    )
    (net (code "218") (name "Net-(T53-C)") (class "Default")
      (node (ref "C53") (pin "2") (pinfunction "2_2") (pintype "passive"))
      (node (ref "D53") (pin "A") (pinfunction "A_A") (pintype "passive"))
      (node (ref "MT53") (pin "2") (pinfunction "2_2") (pintype "passive"))
      (node (ref "T53") (pin "3") (pinfunction "C_3") (pintype "passive"))
    )
    (net (code "219") (name "Net-(T54-B)") (class "Default")
      (node (ref "R54") (pin "2") (pinfunction "2_2") (pintype "passive"))
      (node (ref "T54") (pin "2") (pinfunction "B_2") (pintype "passive"))
    )
    (net (code "220") (name "Net-(T54-C)") (class "Default")
      (node (ref "C54") (pin "2") (pinfunction "2_2") (pintype "passive"))
      (node (ref "D54") (pin "A") (pinfunction "A_A") (pintype "passive"))
      (node (ref "MT54") (pin "2") (pinfunction "2_2") (pintype "passive"))
      (node (ref "T54") (pin "3") (pinfunction "C_3") (pintype "passive"))
    )
    (net (code "221") (name "Net-(T55-B)") (class "Default")
      (node (ref "R55") (pin "2") (pinfunction "2_2") (pintype "passive"))
      (node (ref "T55") (pin "2") (pinfunction "B_2") (pintype "passive"))
    )
    (net (code "222") (name "Net-(T55-C)") (class "Default")
      (node (ref "C55") (pin "2") (pinfunction "2_2") (pintype "passive"))
      (node (ref "D55") (pin "A") (pinfunction "A_A") (pintype "passive"))
      (node (ref "MT55") (pin "2") (pinfunction "2_2") (pintype "passive"))
      (node (ref "T55") (pin "3") (pinfunction "C_3") (pintype "passive"))
    )
    (net (code "223") (name "Net-(T56-B)") (class "Default")
      (node (ref "R56") (pin "2") (pinfunction "2_2") (pintype "passive"))
      (node (ref "T56") (pin "2") (pinfunction "B_2") (pintype "passive"))
    )
    (net (code "224") (name "Net-(T56-C)") (class "Default")
      (node (ref "C56") (pin "2") (pinfunction "2_2") (pintype "passive"))
      (node (ref "D56") (pin "A") (pinfunction "A_A") (pintype "passive"))
      (node (ref "MT56") (pin "2") (pinfunction "2_2") (pintype "passive"))
      (node (ref "T56") (pin "3") (pinfunction "C_3") (pintype "passive"))
    )
    (net (code "225") (name "Net-(T57-B)") (class "Default")
      (node (ref "R57") (pin "2") (pinfunction "2_2") (pintype "passive"))
      (node (ref "T57") (pin "2") (pinfunction "B_2") (pintype "passive"))
    )
    (net (code "226") (name "Net-(T57-C)") (class "Default")
      (node (ref "C57") (pin "2") (pinfunction "2_2") (pintype "passive"))
      (node (ref "D57") (pin "A") (pinfunction "A_A") (pintype "passive"))
      (node (ref "MT57") (pin "2") (pinfunction "2_2") (pintype "passive"))
      (node (ref "T57") (pin "3") (pinfunction "C_3") (pintype "passive"))
    )
    (net (code "227") (name "Net-(T58-B)") (class "Default")
      (node (ref "R58") (pin "2") (pinfunction "2_2") (pintype "passive"))
      (node (ref "T58") (pin "2") (pinfunction "B_2") (pintype "passive"))
    )
    (net (code "228") (name "Net-(T58-C)") (class "Default")
      (node (ref "C58") (pin "2") (pinfunction "2_2") (pintype "passive"))
      (node (ref "D58") (pin "A") (pinfunction "A_A") (pintype "passive"))
      (node (ref "MT58") (pin "2") (pinfunction "2_2") (pintype "passive"))
      (node (ref "T58") (pin "3") (pinfunction "C_3") (pintype "passive"))
    )
    (net (code "229") (name "Net-(T59-B)") (class "Default")
      (node (ref "R59") (pin "2") (pinfunction "2_2") (pintype "passive"))
      (node (ref "T59") (pin "2") (pinfunction "B_2") (pintype "passive"))
    )
    (net (code "230") (name "Net-(T59-C)") (class "Default")
      (node (ref "C59") (pin "2") (pinfunction "2_2") (pintype "passive"))
      (node (ref "D59") (pin "A") (pinfunction "A_A") (pintype "passive"))
      (node (ref "MT59") (pin "2") (pinfunction "2_2") (pintype "passive"))
      (node (ref "T59") (pin "3") (pinfunction "C_3") (pintype "passive"))
    )
    (net (code "231") (name "Net-(T60-B)") (class "Default")
      (node (ref "R60") (pin "2") (pinfunction "2_2") (pintype "passive"))
      (node (ref "T60") (pin "2") (pinfunction "B_2") (pintype "passive"))
    )
    (net (code "232") (name "Net-(T60-C)") (class "Default")
      (node (ref "C60") (pin "2") (pinfunction "2_2") (pintype "passive"))
      (node (ref "D60") (pin "A") (pinfunction "A_A") (pintype "passive"))
      (node (ref "MT60") (pin "2") (pinfunction "2_2") (pintype "passive"))
      (node (ref "T60") (pin "3") (pinfunction "C_3") (pintype "passive"))
    )
    (net (code "233") (name "Net-(T61-B)") (class "Default")
      (node (ref "R61") (pin "2") (pinfunction "2_2") (pintype "passive"))
      (node (ref "T61") (pin "2") (pinfunction "B_2") (pintype "passive"))
    )
    (net (code "234") (name "Net-(T61-C)") (class "Default")
      (node (ref "C61") (pin "2") (pinfunction "2_2") (pintype "passive"))
      (node (ref "D61") (pin "A") (pinfunction "A_A") (pintype "passive"))
      (node (ref "MT61") (pin "2") (pinfunction "2_2") (pintype "passive"))
      (node (ref "T61") (pin "3") (pinfunction "C_3") (pintype "passive"))
    )
    (net (code "235") (name "Net-(T62-B)") (class "Default")
      (node (ref "R62") (pin "2") (pinfunction "2_2") (pintype "passive"))
      (node (ref "T62") (pin "2") (pinfunction "B_2") (pintype "passive"))
    )
    (net (code "236") (name "Net-(T62-C)") (class "Default")
      (node (ref "C62") (pin "2") (pinfunction "2_2") (pintype "passive"))
      (node (ref "D62") (pin "A") (pinfunction "A_A") (pintype "passive"))
      (node (ref "MT62") (pin "2") (pinfunction "2_2") (pintype "passive"))
      (node (ref "T62") (pin "3") (pinfunction "C_3") (pintype "passive"))
    )
    (net (code "237") (name "Net-(T63-B)") (class "Default")
      (node (ref "R63") (pin "2") (pinfunction "2_2") (pintype "passive"))
      (node (ref "T63") (pin "2") (pinfunction "B_2") (pintype "passive"))
    )
    (net (code "238") (name "Net-(T63-C)") (class "Default")
      (node (ref "C63") (pin "2") (pinfunction "2_2") (pintype "passive"))
      (node (ref "D63") (pin "A") (pinfunction "A_A") (pintype "passive"))
      (node (ref "MT63") (pin "2") (pinfunction "2_2") (pintype "passive"))
      (node (ref "T63") (pin "3") (pinfunction "C_3") (pintype "passive"))
    )
    (net (code "239") (name "Net-(T64-B)") (class "Default")
      (node (ref "R64") (pin "2") (pinfunction "2_2") (pintype "passive"))
      (node (ref "T64") (pin "2") (pinfunction "B_2") (pintype "passive"))
    )
    (net (code "240") (name "Net-(T64-C)") (class "Default")
      (node (ref "C64") (pin "2") (pinfunction "2_2") (pintype "passive"))
      (node (ref "D64") (pin "A") (pinfunction "A_A") (pintype "passive"))
      (node (ref "MT64") (pin "2") (pinfunction "2_2") (pintype "passive"))
      (node (ref "T64") (pin "3") (pinfunction "C_3") (pintype "passive"))
    )
    (net (code "241") (name "Net-(T65-B)") (class "Default")
      (node (ref "R65") (pin "2") (pinfunction "2_2") (pintype "passive"))
      (node (ref "T65") (pin "2") (pinfunction "B_2") (pintype "passive"))
    )
    (net (code "242") (name "Net-(T65-C)") (class "Default")
      (node (ref "C65") (pin "2") (pinfunction "2_2") (pintype "passive"))
      (node (ref "D65") (pin "A") (pinfunction "A_A") (pintype "passive"))
      (node (ref "MT65") (pin "2") (pinfunction "2_2") (pintype "passive"))
      (node (ref "T65") (pin "3") (pinfunction "C_3") (pintype "passive"))
    )
    (net (code "243") (name "Net-(T66-B)") (class "Default")
      (node (ref "R66") (pin "2") (pinfunction "2_2") (pintype "passive"))
      (node (ref "T66") (pin "2") (pinfunction "B_2") (pintype "passive"))
    )
    (net (code "244") (name "Net-(T66-C)") (class "Default")
      (node (ref "C66") (pin "2") (pinfunction "2_2") (pintype "passive"))
      (node (ref "D66") (pin "A") (pinfunction "A_A") (pintype "passive"))
      (node (ref "MT66") (pin "2") (pinfunction "2_2") (pintype "passive"))
      (node (ref "T66") (pin "3") (pinfunction "C_3") (pintype "passive"))
    )
    (net (code "245") (name "Net-(T67-B)") (class "Default")
      (node (ref "R67") (pin "2") (pinfunction "2_2") (pintype "passive"))
      (node (ref "T67") (pin "2") (pinfunction "B_2") (pintype "passive"))
    )
    (net (code "246") (name "Net-(T67-C)") (class "Default")
      (node (ref "C67") (pin "2") (pinfunction "2_2") (pintype "passive"))
      (node (ref "D67") (pin "A") (pinfunction "A_A") (pintype "passive"))
      (node (ref "MT67") (pin "2") (pinfunction "2_2") (pintype "passive"))
      (node (ref "T67") (pin "3") (pinfunction "C_3") (pintype "passive"))
    )
    (net (code "247") (name "Net-(T68-B)") (class "Default")
      (node (ref "R68") (pin "2") (pinfunction "2_2") (pintype "passive"))
      (node (ref "T68") (pin "2") (pinfunction "B_2") (pintype "passive"))
    )
    (net (code "248") (name "Net-(T68-C)") (class "Default")
      (node (ref "C68") (pin "2") (pinfunction "2_2") (pintype "passive"))
      (node (ref "D68") (pin "A") (pinfunction "A_A") (pintype "passive"))
      (node (ref "MT68") (pin "2") (pinfunction "2_2") (pintype "passive"))
      (node (ref "T68") (pin "3") (pinfunction "C_3") (pintype "passive"))
    )
    (net (code "249") (name "Net-(T69-B)") (class "Default")
      (node (ref "R69") (pin "2") (pinfunction "2_2") (pintype "passive"))
      (node (ref "T69") (pin "2") (pinfunction "B_2") (pintype "passive"))
    )
    (net (code "250") (name "Net-(T69-C)") (class "Default")
      (node (ref "C69") (pin "2") (pinfunction "2_2") (pintype "passive"))
      (node (ref "D69") (pin "A") (pinfunction "A_A") (pintype "passive"))
      (node (ref "MT69") (pin "2") (pinfunction "2_2") (pintype "passive"))
      (node (ref "T69") (pin "3") (pinfunction "C_3") (pintype "passive"))
    )
    (net (code "251") (name "Net-(T70-B)") (class "Default")
      (node (ref "R70") (pin "2") (pinfunction "2_2") (pintype "passive"))
      (node (ref "T70") (pin "2") (pinfunction "B_2") (pintype "passive"))
    )
    (net (code "252") (name "Net-(T70-C)") (class "Default")
      (node (ref "C70") (pin "2") (pinfunction "2_2") (pintype "passive"))
      (node (ref "D70") (pin "A") (pinfunction "A_A") (pintype "passive"))
      (node (ref "MT70") (pin "2") (pinfunction "2_2") (pintype "passive"))
      (node (ref "T70") (pin "3") (pinfunction "C_3") (pintype "passive"))
    )
    (net (code "253") (name "Net-(T71-B)") (class "Default")
      (node (ref "R71") (pin "2") (pinfunction "2_2") (pintype "passive"))
      (node (ref "T71") (pin "2") (pinfunction "B_2") (pintype "passive"))
    )
    (net (code "254") (name "Net-(T71-C)") (class "Default")
      (node (ref "C71") (pin "2") (pinfunction "2_2") (pintype "passive"))
      (node (ref "D71") (pin "A") (pinfunction "A_A") (pintype "passive"))
      (node (ref "MT71") (pin "2") (pinfunction "2_2") (pintype "passive"))
      (node (ref "T71") (pin "3") (pinfunction "C_3") (pintype "passive"))
    )
    (net (code "255") (name "Net-(T72-B)") (class "Default")
      (node (ref "R72") (pin "2") (pinfunction "2_2") (pintype "passive"))
      (node (ref "T72") (pin "2") (pinfunction "B_2") (pintype "passive"))
    )
    (net (code "256") (name "Net-(T72-C)") (class "Default")
      (node (ref "C72") (pin "2") (pinfunction "2_2") (pintype "passive"))
      (node (ref "D72") (pin "A") (pinfunction "A_A") (pintype "passive"))
      (node (ref "MT72") (pin "2") (pinfunction "2_2") (pintype "passive"))
      (node (ref "T72") (pin "3") (pinfunction "C_3") (pintype "passive"))
    )
    (net (code "257") (name "Net-(T73-B)") (class "Default")
      (node (ref "R73") (pin "2") (pinfunction "2_2") (pintype "passive"))
      (node (ref "T73") (pin "2") (pinfunction "B_2") (pintype "passive"))
    )
    (net (code "258") (name "Net-(T73-C)") (class "Default")
      (node (ref "C73") (pin "2") (pinfunction "2_2") (pintype "passive"))
      (node (ref "D73") (pin "A") (pinfunction "A_A") (pintype "passive"))
      (node (ref "MT73") (pin "2") (pinfunction "2_2") (pintype "passive"))
      (node (ref "T73") (pin "3") (pinfunction "C_3") (pintype "passive"))
    )
    (net (code "259") (name "Net-(T74-B)") (class "Default")
      (node (ref "R74") (pin "2") (pinfunction "2_2") (pintype "passive"))
      (node (ref "T74") (pin "2") (pinfunction "B_2") (pintype "passive"))
    )
    (net (code "260") (name "Net-(T74-C)") (class "Default")
      (node (ref "C74") (pin "2") (pinfunction "2_2") (pintype "passive"))
      (node (ref "D74") (pin "A") (pinfunction "A_A") (pintype "passive"))
      (node (ref "MT74") (pin "2") (pinfunction "2_2") (pintype "passive"))
      (node (ref "T74") (pin "3") (pinfunction "C_3") (pintype "passive"))
    )
    (net (code "261") (name "Net-(T75-B)") (class "Default")
      (node (ref "R75") (pin "2") (pinfunction "2_2") (pintype "passive"))
      (node (ref "T75") (pin "2") (pinfunction "B_2") (pintype "passive"))
    )
    (net (code "262") (name "Net-(T75-C)") (class "Default")
      (node (ref "C75") (pin "2") (pinfunction "2_2") (pintype "passive"))
      (node (ref "D75") (pin "A") (pinfunction "A_A") (pintype "passive"))
      (node (ref "MT75") (pin "2") (pinfunction "2_2") (pintype "passive"))
      (node (ref "T75") (pin "3") (pinfunction "C_3") (pintype "passive"))
    )
    (net (code "263") (name "Net-(T76-B)") (class "Default")
      (node (ref "R76") (pin "2") (pinfunction "2_2") (pintype "passive"))
      (node (ref "T76") (pin "2") (pinfunction "B_2") (pintype "passive"))
    )
    (net (code "264") (name "Net-(T76-C)") (class "Default")
      (node (ref "C76") (pin "2") (pinfunction "2_2") (pintype "passive"))
      (node (ref "D76") (pin "A") (pinfunction "A_A") (pintype "passive"))
      (node (ref "MT76") (pin "2") (pinfunction "2_2") (pintype "passive"))
      (node (ref "T76") (pin "3") (pinfunction "C_3") (pintype "passive"))
    )
    (net (code "265") (name "Net-(T77-B)") (class "Default")
      (node (ref "R77") (pin "2") (pinfunction "2_2") (pintype "passive"))
      (node (ref "T77") (pin "2") (pinfunction "B_2") (pintype "passive"))
    )
    (net (code "266") (name "Net-(T77-C)") (class "Default")
      (node (ref "C77") (pin "2") (pinfunction "2_2") (pintype "passive"))
      (node (ref "D77") (pin "A") (pinfunction "A_A") (pintype "passive"))
      (node (ref "MT77") (pin "2") (pinfunction "2_2") (pintype "passive"))
      (node (ref "T77") (pin "3") (pinfunction "C_3") (pintype "passive"))
    )
    (net (code "267") (name "Net-(T78-B)") (class "Default")
      (node (ref "R78") (pin "2") (pinfunction "2_2") (pintype "passive"))
      (node (ref "T78") (pin "2") (pinfunction "B_2") (pintype "passive"))
    )
    (net (code "268") (name "Net-(T78-C)") (class "Default")
      (node (ref "C78") (pin "2") (pinfunction "2_2") (pintype "passive"))
      (node (ref "D78") (pin "A") (pinfunction "A_A") (pintype "passive"))
      (node (ref "MT78") (pin "2") (pinfunction "2_2") (pintype "passive"))
      (node (ref "T78") (pin "3") (pinfunction "C_3") (pintype "passive"))
    )
    (net (code "269") (name "Net-(T79-B)") (class "Default")
      (node (ref "R79") (pin "2") (pinfunction "2_2") (pintype "passive"))
      (node (ref "T79") (pin "2") (pinfunction "B_2") (pintype "passive"))
    )
    (net (code "270") (name "Net-(T79-C)") (class "Default")
      (node (ref "C79") (pin "2") (pinfunction "2_2") (pintype "passive"))
      (node (ref "D79") (pin "A") (pinfunction "A_A") (pintype "passive"))
      (node (ref "MT79") (pin "2") (pinfunction "2_2") (pintype "passive"))
      (node (ref "T79") (pin "3") (pinfunction "C_3") (pintype "passive"))
    )
    (net (code "271") (name "Net-(T80-B)") (class "Default")
      (node (ref "R80") (pin "2") (pinfunction "2_2") (pintype "passive"))
      (node (ref "T80") (pin "2") (pinfunction "B_2") (pintype "passive"))
    )
    (net (code "272") (name "Net-(T80-C)") (class "Default")
      (node (ref "C80") (pin "2") (pinfunction "2_2") (pintype "passive"))
      (node (ref "D80") (pin "A") (pinfunction "A_A") (pintype "passive"))
      (node (ref "MT80") (pin "2") (pinfunction "2_2") (pintype "passive"))
      (node (ref "T80") (pin "3") (pinfunction "C_3") (pintype "passive"))
    )
    (net (code "273") (name "Net-(T81-B)") (class "Default")
      (node (ref "R81") (pin "2") (pinfunction "2_2") (pintype "passive"))
      (node (ref "T81") (pin "2") (pinfunction "B_2") (pintype "passive"))
    )
    (net (code "274") (name "Net-(T81-C)") (class "Default")
      (node (ref "C81") (pin "2") (pinfunction "2_2") (pintype "passive"))
      (node (ref "D81") (pin "A") (pinfunction "A_A") (pintype "passive"))
      (node (ref "MT81") (pin "2") (pinfunction "2_2") (pintype "passive"))
      (node (ref "T81") (pin "3") (pinfunction "C_3") (pintype "passive"))
    )
    (net (code "275") (name "Net-(T82-B)") (class "Default")
      (node (ref "R82") (pin "2") (pinfunction "2_2") (pintype "passive"))
      (node (ref "T82") (pin "2") (pinfunction "B_2") (pintype "passive"))
    )
    (net (code "276") (name "Net-(T82-C)") (class "Default")
      (node (ref "C82") (pin "2") (pinfunction "2_2") (pintype "passive"))
      (node (ref "D82") (pin "A") (pinfunction "A_A") (pintype "passive"))
      (node (ref "MT82") (pin "2") (pinfunction "2_2") (pintype "passive"))
      (node (ref "T82") (pin "3") (pinfunction "C_3") (pintype "passive"))
    )
    (net (code "277") (name "Net-(T83-B)") (class "Default")
      (node (ref "R83") (pin "2") (pinfunction "2_2") (pintype "passive"))
      (node (ref "T83") (pin "2") (pinfunction "B_2") (pintype "passive"))
    )
    (net (code "278") (name "Net-(T83-C)") (class "Default")
      (node (ref "C83") (pin "2") (pinfunction "2_2") (pintype "passive"))
      (node (ref "D83") (pin "A") (pinfunction "A_A") (pintype "passive"))
      (node (ref "MT83") (pin "2") (pinfunction "2_2") (pintype "passive"))
      (node (ref "T83") (pin "3") (pinfunction "C_3") (pintype "passive"))
    )
    (net (code "279") (name "Net-(T84-B)") (class "Default")
      (node (ref "R84") (pin "2") (pinfunction "2_2") (pintype "passive"))
      (node (ref "T84") (pin "2") (pinfunction "B_2") (pintype "passive"))
    )
    (net (code "280") (name "Net-(T84-C)") (class "Default")
      (node (ref "C84") (pin "2") (pinfunction "2_2") (pintype "passive"))
      (node (ref "D84") (pin "A") (pinfunction "A_A") (pintype "passive"))
      (node (ref "MT84") (pin "2") (pinfunction "2_2") (pintype "passive"))
      (node (ref "T84") (pin "3") (pinfunction "C_3") (pintype "passive"))
    )
    (net (code "281") (name "Net-(T85-B)") (class "Default")
      (node (ref "R85") (pin "2") (pinfunction "2_2") (pintype "passive"))
      (node (ref "T85") (pin "2") (pinfunction "B_2") (pintype "passive"))
    )
    (net (code "282") (name "Net-(T85-C)") (class "Default")
      (node (ref "C85") (pin "2") (pinfunction "2_2") (pintype "passive"))
      (node (ref "D85") (pin "A") (pinfunction "A_A") (pintype "passive"))
      (node (ref "MT85") (pin "2") (pinfunction "2_2") (pintype "passive"))
      (node (ref "T85") (pin "3") (pinfunction "C_3") (pintype "passive"))
    )
    (net (code "283") (name "Net-(T86-B)") (class "Default")
      (node (ref "R86") (pin "2") (pinfunction "2_2") (pintype "passive"))
      (node (ref "T86") (pin "2") (pinfunction "B_2") (pintype "passive"))
    )
    (net (code "284") (name "Net-(T86-C)") (class "Default")
      (node (ref "C86") (pin "2") (pinfunction "2_2") (pintype "passive"))
      (node (ref "D86") (pin "A") (pinfunction "A_A") (pintype "passive"))
      (node (ref "MT86") (pin "2") (pinfunction "2_2") (pintype "passive"))
      (node (ref "T86") (pin "3") (pinfunction "C_3") (pintype "passive"))
    )
    (net (code "285") (name "Net-(T87-B)") (class "Default")
      (node (ref "R87") (pin "2") (pinfunction "2_2") (pintype "passive"))
      (node (ref "T87") (pin "2") (pinfunction "B_2") (pintype "passive"))
    )
    (net (code "286") (name "Net-(T87-C)") (class "Default")
      (node (ref "C87") (pin "2") (pinfunction "2_2") (pintype "passive"))
      (node (ref "D87") (pin "A") (pinfunction "A_A") (pintype "passive"))
      (node (ref "MT87") (pin "2") (pinfunction "2_2") (pintype "passive"))
      (node (ref "T87") (pin "3") (pinfunction "C_3") (pintype "passive"))
    )
    (net (code "287") (name "Net-(T88-B)") (class "Default")
      (node (ref "R88") (pin "2") (pinfunction "2_2") (pintype "passive"))
      (node (ref "T88") (pin "2") (pinfunction "B_2") (pintype "passive"))
    )
    (net (code "288") (name "Net-(T88-C)") (class "Default")
      (node (ref "C88") (pin "2") (pinfunction "2_2") (pintype "passive"))
      (node (ref "D88") (pin "A") (pinfunction "A_A") (pintype "passive"))
      (node (ref "MT88") (pin "2") (pinfunction "2_2") (pintype "passive"))
      (node (ref "T88") (pin "3") (pinfunction "C_3") (pintype "passive"))
    )
    (net (code "289") (name "Net-(T89-B)") (class "Default")
      (node (ref "R89") (pin "2") (pinfunction "2_2") (pintype "passive"))
      (node (ref "T89") (pin "2") (pinfunction "B_2") (pintype "passive"))
    )
    (net (code "290") (name "Net-(T89-C)") (class "Default")
      (node (ref "C89") (pin "2") (pinfunction "2_2") (pintype "passive"))
      (node (ref "D89") (pin "A") (pinfunction "A_A") (pintype "passive"))
      (node (ref "MT89") (pin "2") (pinfunction "2_2") (pintype "passive"))
      (node (ref "T89") (pin "3") (pinfunction "C_3") (pintype "passive"))
    )
    (net (code "291") (name "Net-(T90-B)") (class "Default")
      (node (ref "R90") (pin "2") (pinfunction "2_2") (pintype "passive"))
      (node (ref "T90") (pin "2") (pinfunction "B_2") (pintype "passive"))
    )
    (net (code "292") (name "Net-(T90-C)") (class "Default")
      (node (ref "C90") (pin "2") (pinfunction "2_2") (pintype "passive"))
      (node (ref "D90") (pin "A") (pinfunction "A_A") (pintype "passive"))
      (node (ref "MT90") (pin "2") (pinfunction "2_2") (pintype "passive"))
      (node (ref "T90") (pin "3") (pinfunction "C_3") (pintype "passive"))
    )
    (net (code "293") (name "Net-(T91-B)") (class "Default")
      (node (ref "R91") (pin "2") (pinfunction "2_2") (pintype "passive"))
      (node (ref "T91") (pin "2") (pinfunction "B_2") (pintype "passive"))
    )
    (net (code "294") (name "Net-(T91-C)") (class "Default")
      (node (ref "C91") (pin "2") (pinfunction "2_2") (pintype "passive"))
      (node (ref "D91") (pin "A") (pinfunction "A_A") (pintype "passive"))
      (node (ref "MT91") (pin "2") (pinfunction "2_2") (pintype "passive"))
      (node (ref "T91") (pin "3") (pinfunction "C_3") (pintype "passive"))
    )
    (net (code "295") (name "Net-(T92-B)") (class "Default")
      (node (ref "R92") (pin "2") (pinfunction "2_2") (pintype "passive"))
      (node (ref "T92") (pin "2") (pinfunction "B_2") (pintype "passive"))
    )
    (net (code "296") (name "Net-(T92-C)") (class "Default")
      (node (ref "C92") (pin "2") (pinfunction "2_2") (pintype "passive"))
      (node (ref "D92") (pin "A") (pinfunction "A_A") (pintype "passive"))
      (node (ref "MT92") (pin "2") (pinfunction "2_2") (pintype "passive"))
      (node (ref "T92") (pin "3") (pinfunction "C_3") (pintype "passive"))
    )
    (net (code "297") (name "Net-(T93-B)") (class "Default")
      (node (ref "R93") (pin "2") (pinfunction "2_2") (pintype "passive"))
      (node (ref "T93") (pin "2") (pinfunction "B_2") (pintype "passive"))
    )
    (net (code "298") (name "Net-(T93-C)") (class "Default")
      (node (ref "C93") (pin "2") (pinfunction "2_2") (pintype "passive"))
      (node (ref "D93") (pin "A") (pinfunction "A_A") (pintype "passive"))
      (node (ref "MT93") (pin "2") (pinfunction "2_2") (pintype "passive"))
      (node (ref "T93") (pin "3") (pinfunction "C_3") (pintype "passive"))
    )
    (net (code "299") (name "Net-(T94-B)") (class "Default")
      (node (ref "R94") (pin "2") (pinfunction "2_2") (pintype "passive"))
      (node (ref "T94") (pin "2") (pinfunction "B_2") (pintype "passive"))
    )
    (net (code "300") (name "Net-(T94-C)") (class "Default")
      (node (ref "C94") (pin "2") (pinfunction "2_2") (pintype "passive"))
      (node (ref "D94") (pin "A") (pinfunction "A_A") (pintype "passive"))
      (node (ref "MT94") (pin "2") (pinfunction "2_2") (pintype "passive"))
      (node (ref "T94") (pin "3") (pinfunction "C_3") (pintype "passive"))
    )
    (net (code "301") (name "Net-(T95-B)") (class "Default")
      (node (ref "R95") (pin "2") (pinfunction "2_2") (pintype "passive"))
      (node (ref "T95") (pin "2") (pinfunction "B_2") (pintype "passive"))
    )
    (net (code "302") (name "Net-(T95-C)") (class "Default")
      (node (ref "C95") (pin "2") (pinfunction "2_2") (pintype "passive"))
      (node (ref "D95") (pin "A") (pinfunction "A_A") (pintype "passive"))
      (node (ref "MT95") (pin "2") (pinfunction "2_2") (pintype "passive"))
      (node (ref "T95") (pin "3") (pinfunction "C_3") (pintype "passive"))
    )
    (net (code "303") (name "Net-(T96-B)") (class "Default")
      (node (ref "R96") (pin "2") (pinfunction "2_2") (pintype "passive"))
      (node (ref "T96") (pin "2") (pinfunction "B_2") (pintype "passive"))
    )
    (net (code "304") (name "Net-(T96-C)") (class "Default")
      (node (ref "C96") (pin "2") (pinfunction "2_2") (pintype "passive"))
      (node (ref "D96") (pin "A") (pinfunction "A_A") (pintype "passive"))
      (node (ref "MT96") (pin "2") (pinfunction "2_2") (pintype "passive"))
      (node (ref "T96") (pin "3") (pinfunction "C_3") (pintype "passive"))
    )
    (net (code "305") (name "unconnected-(IC12A-QH*-Pad9)") (class "Default")
      (node (ref "IC12") (pin "9") (pinfunction "QH*_9") (pintype "tri_state"))
    )
  )
)
